# robot_PI4_F28379D.net
KiCad netlist of a schematic drawn in EAGLE
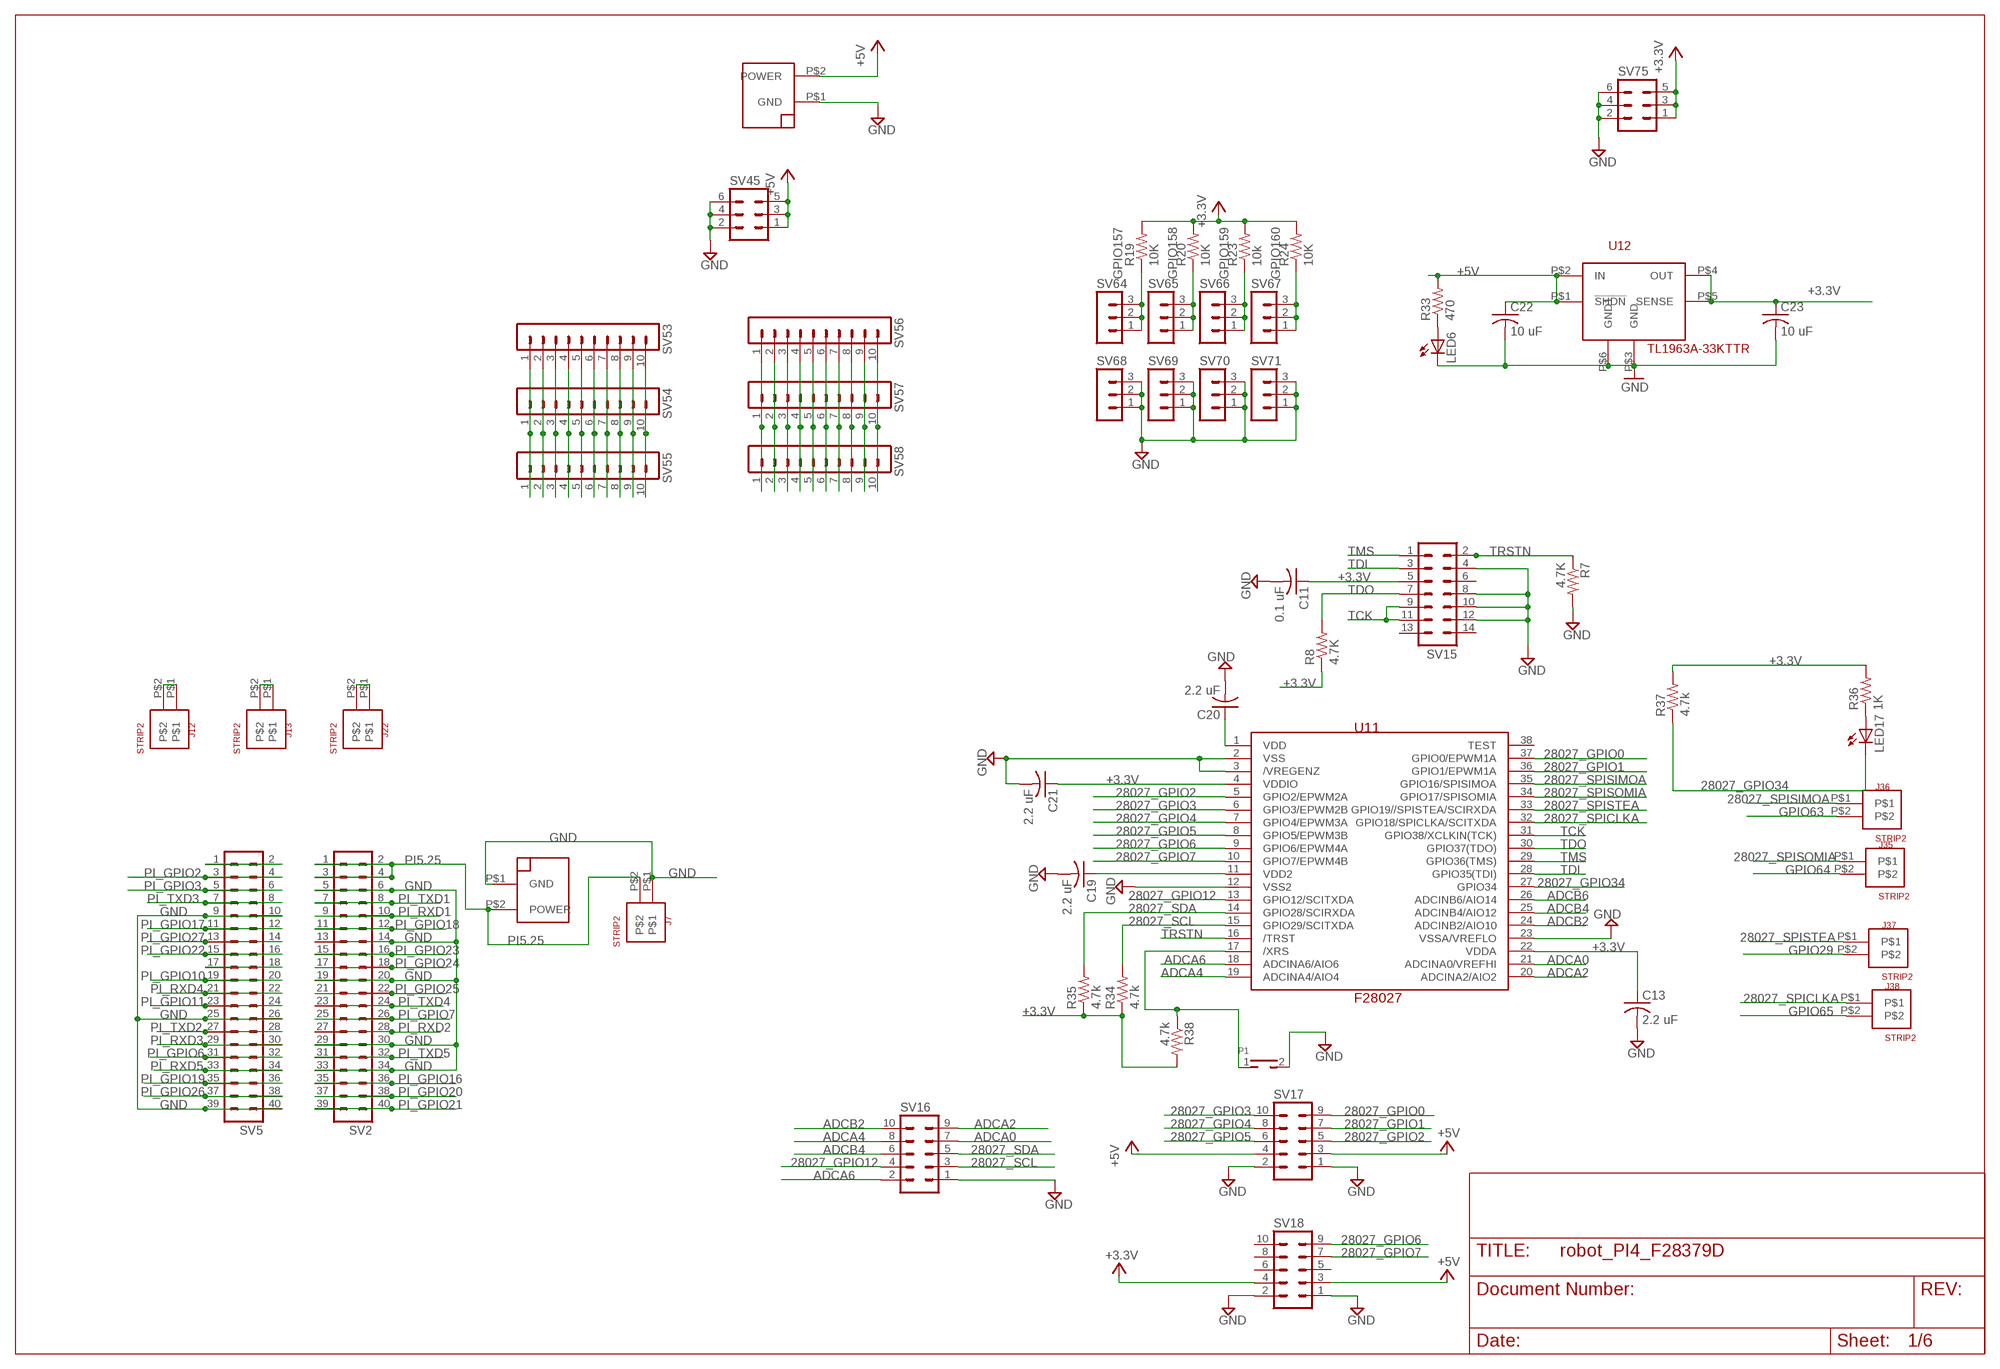
[diagram p0: schematic, sheet 1]
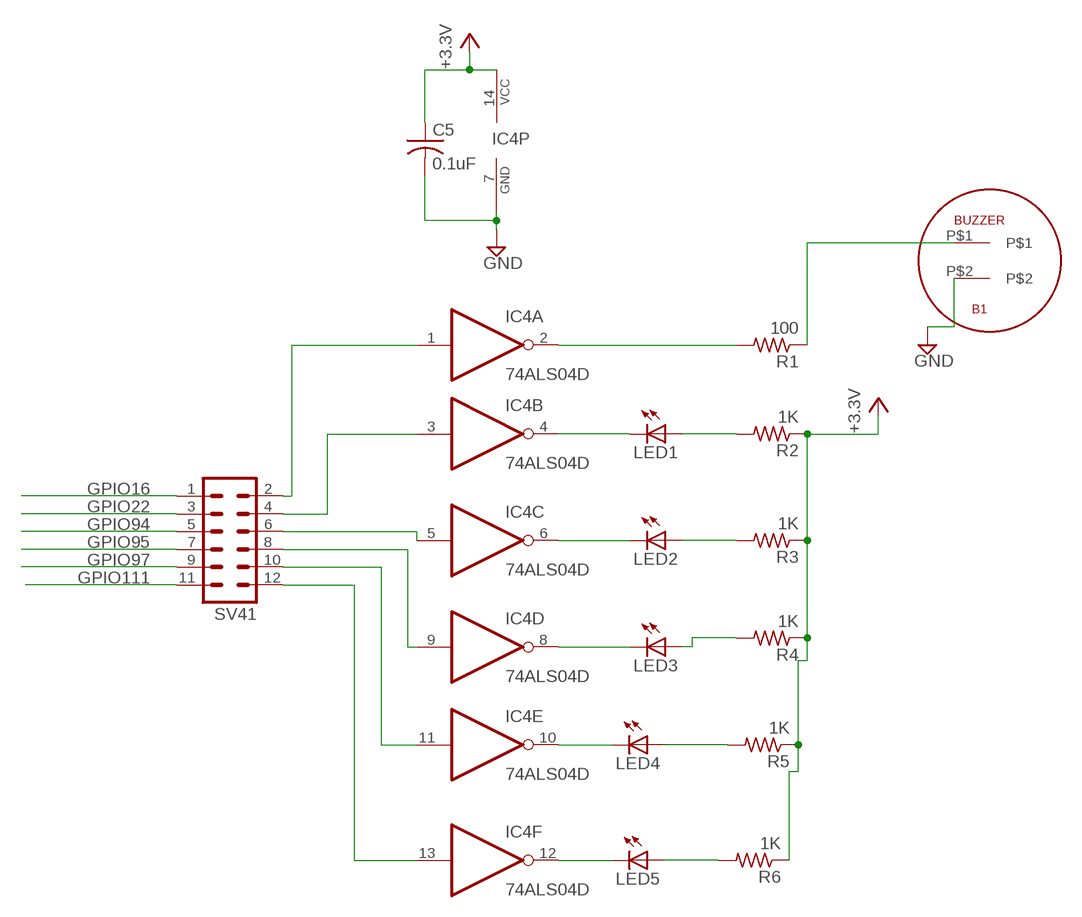
[diagram p1: schematic, sheet 2]
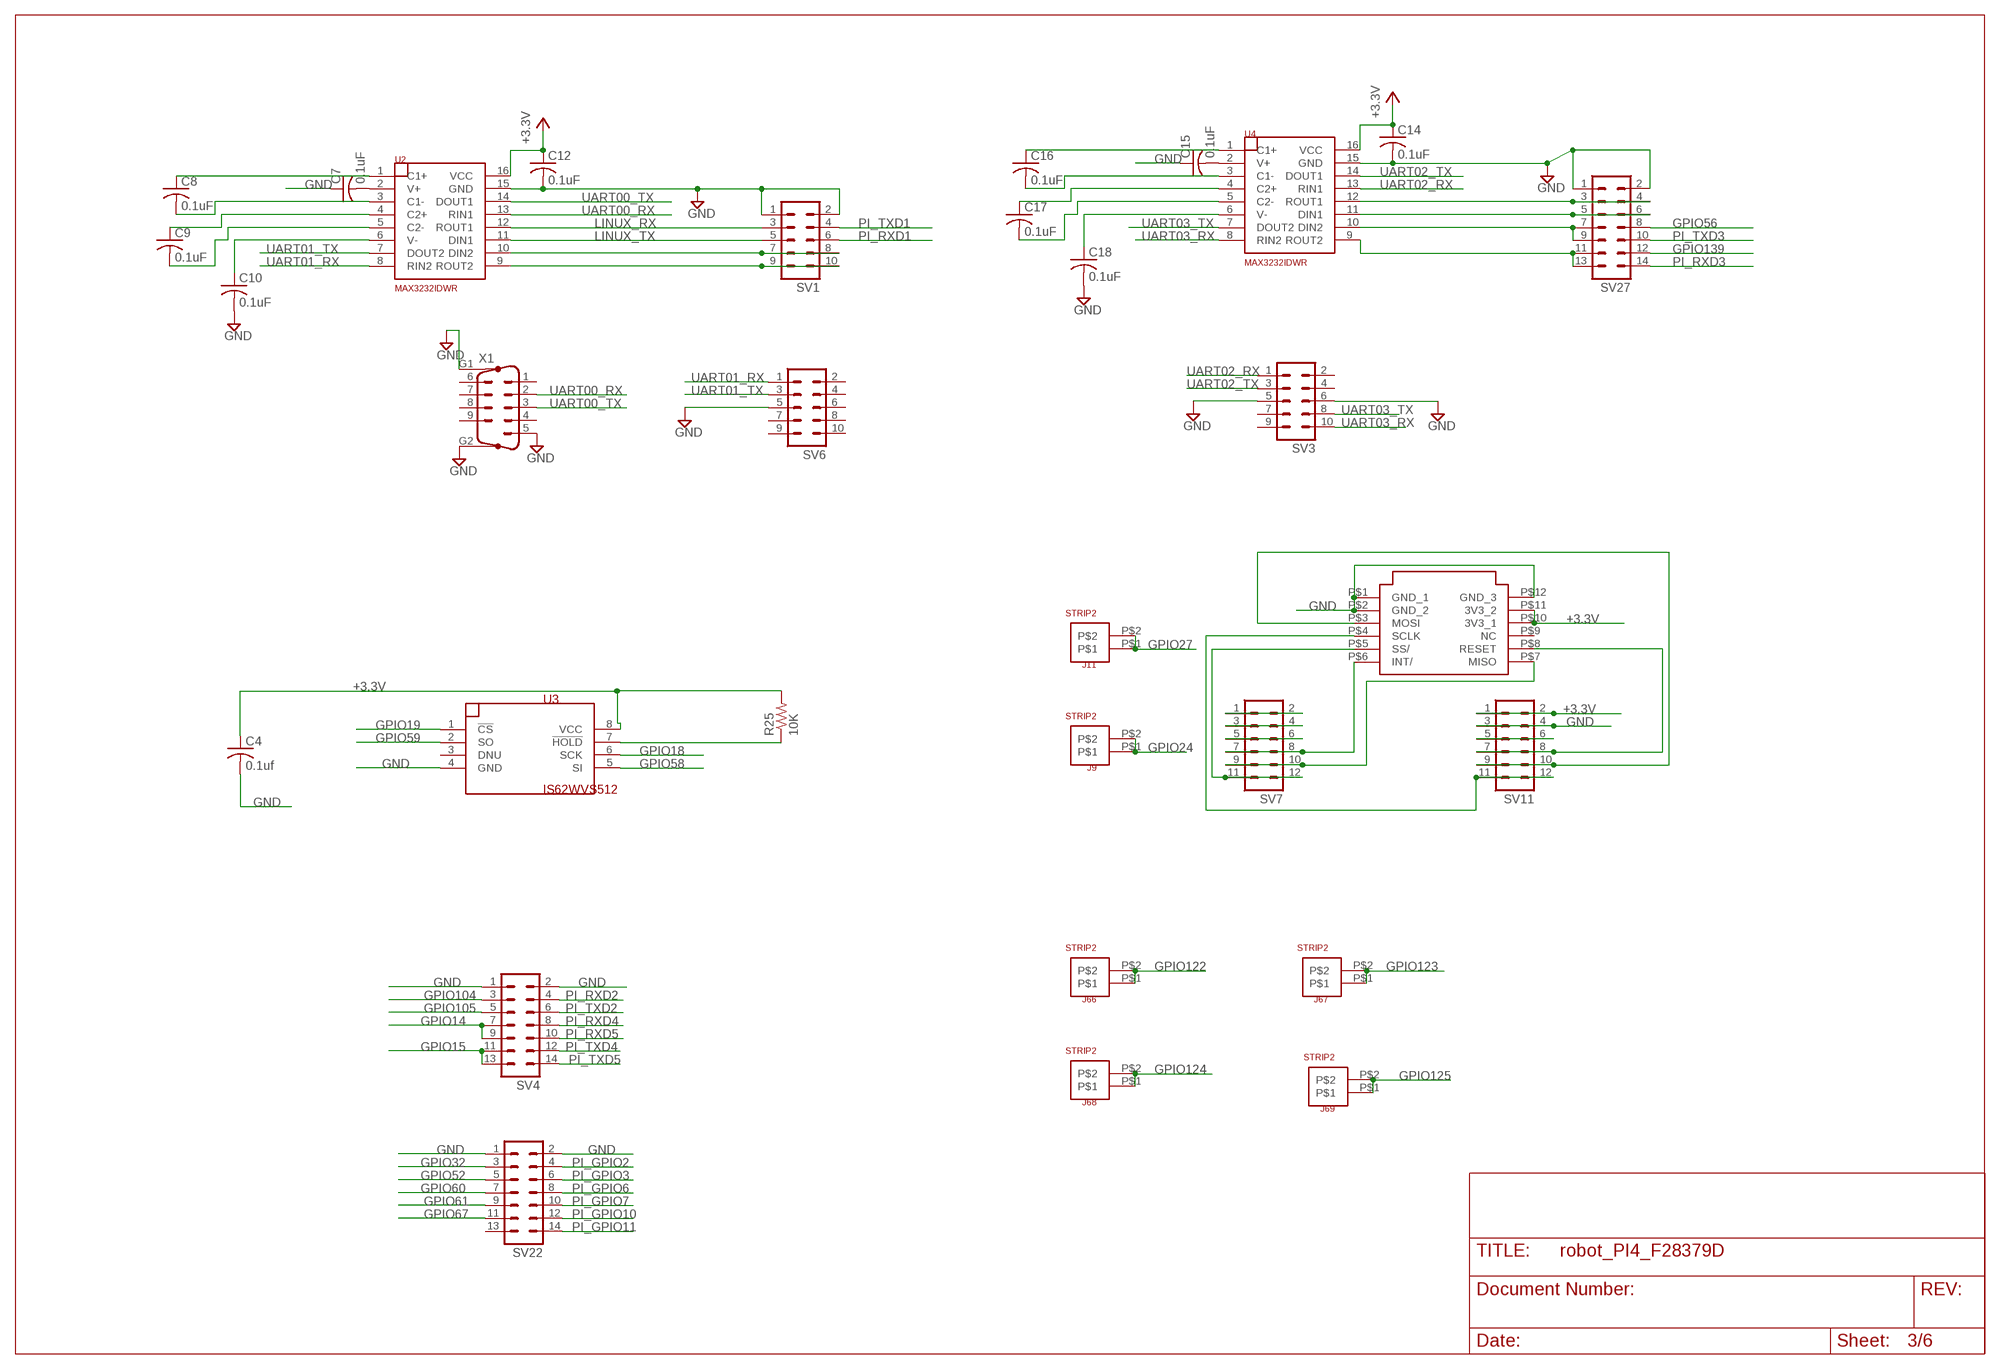
[diagram p2: schematic, sheet 3]
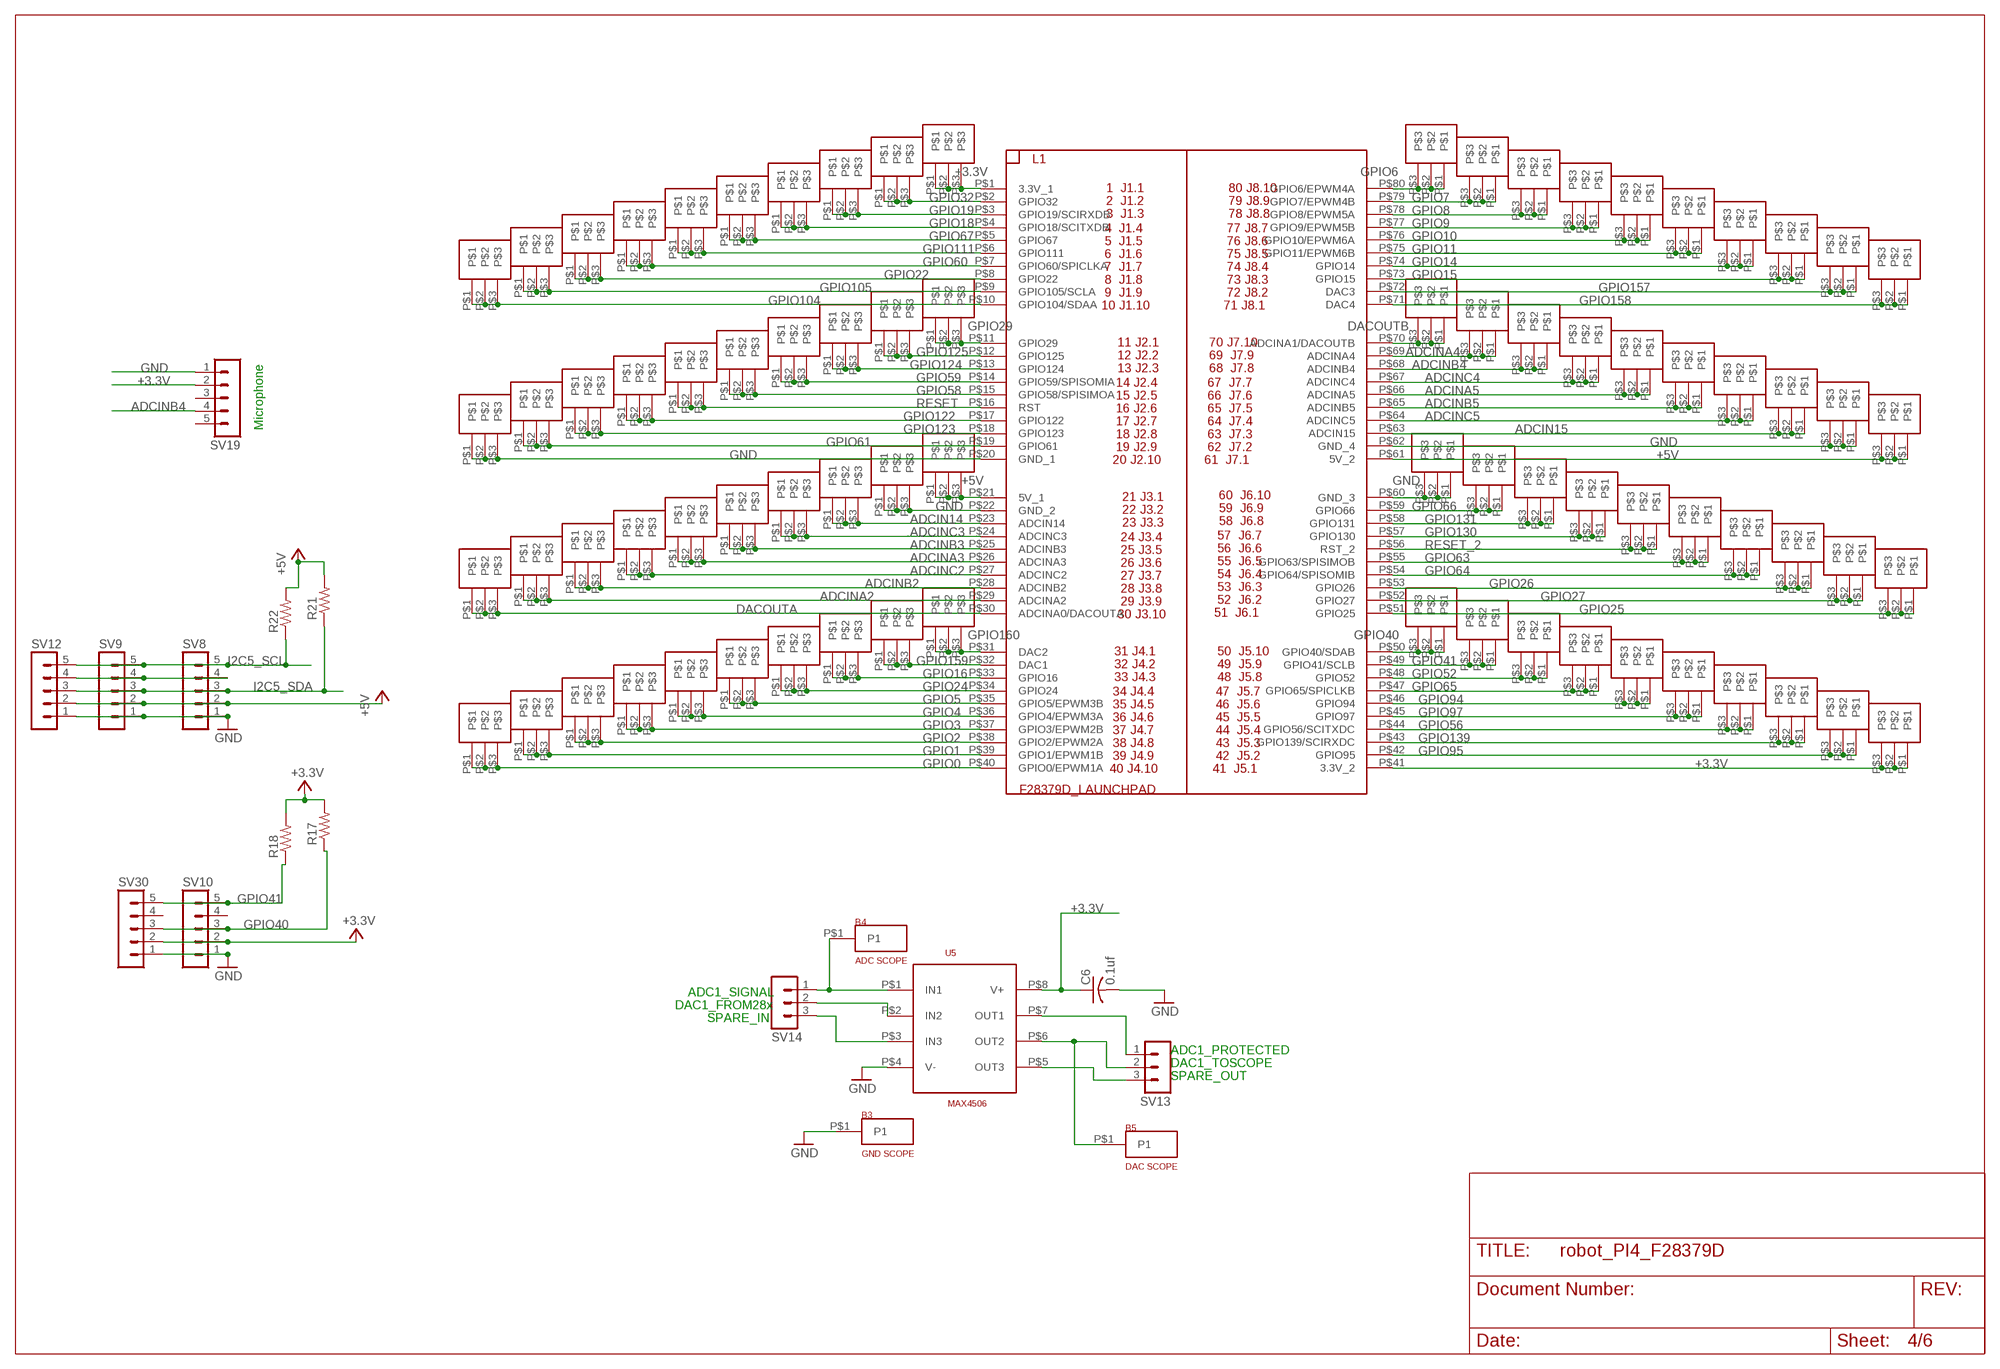
[diagram p3: schematic, sheet 4]
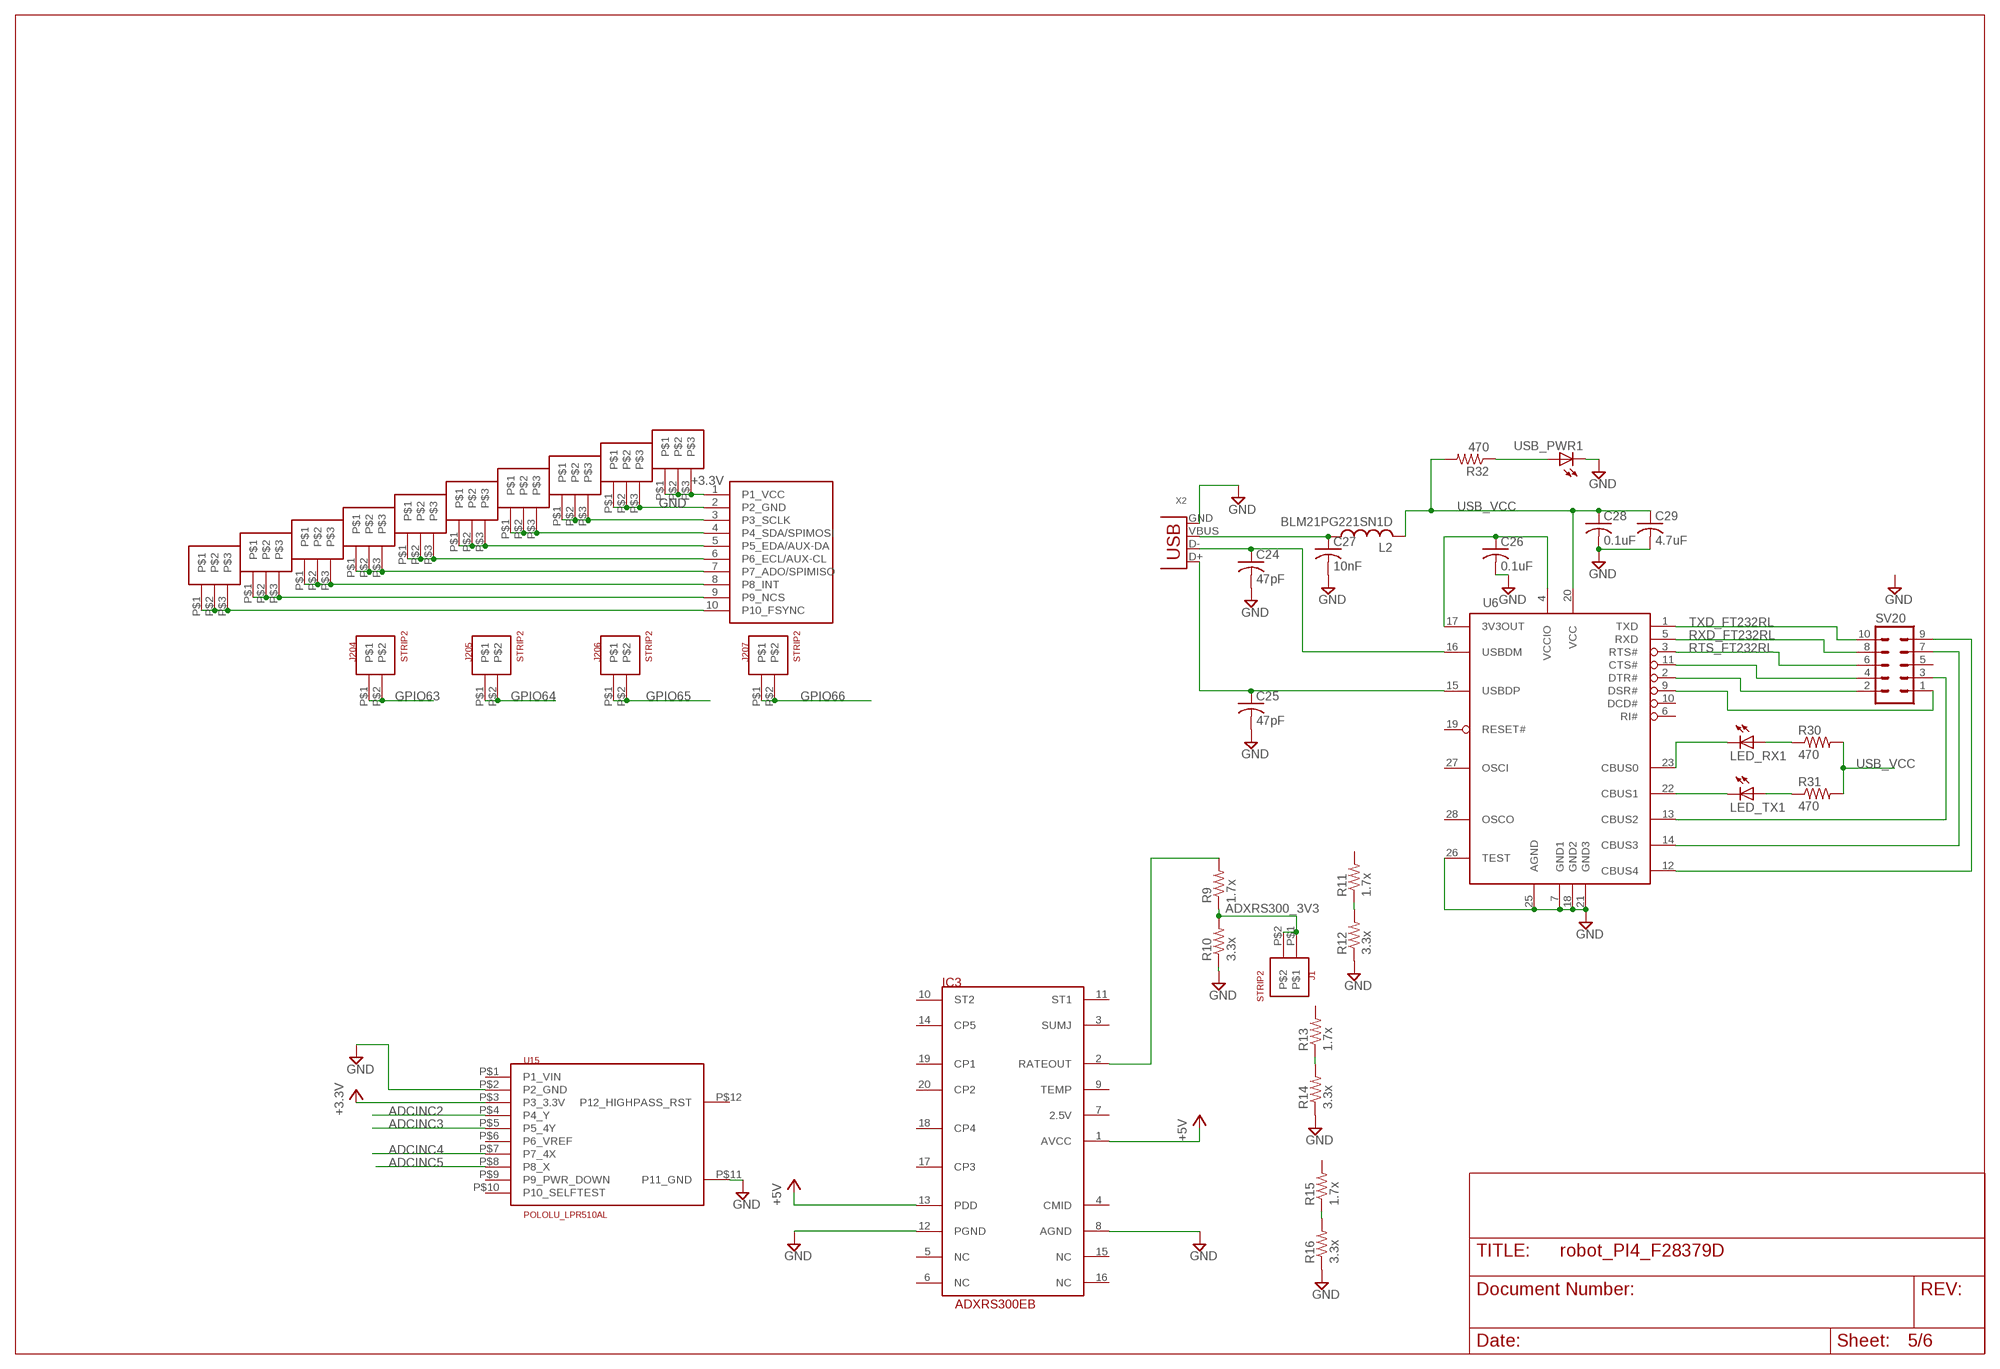
[diagram p4: schematic, sheet 5]
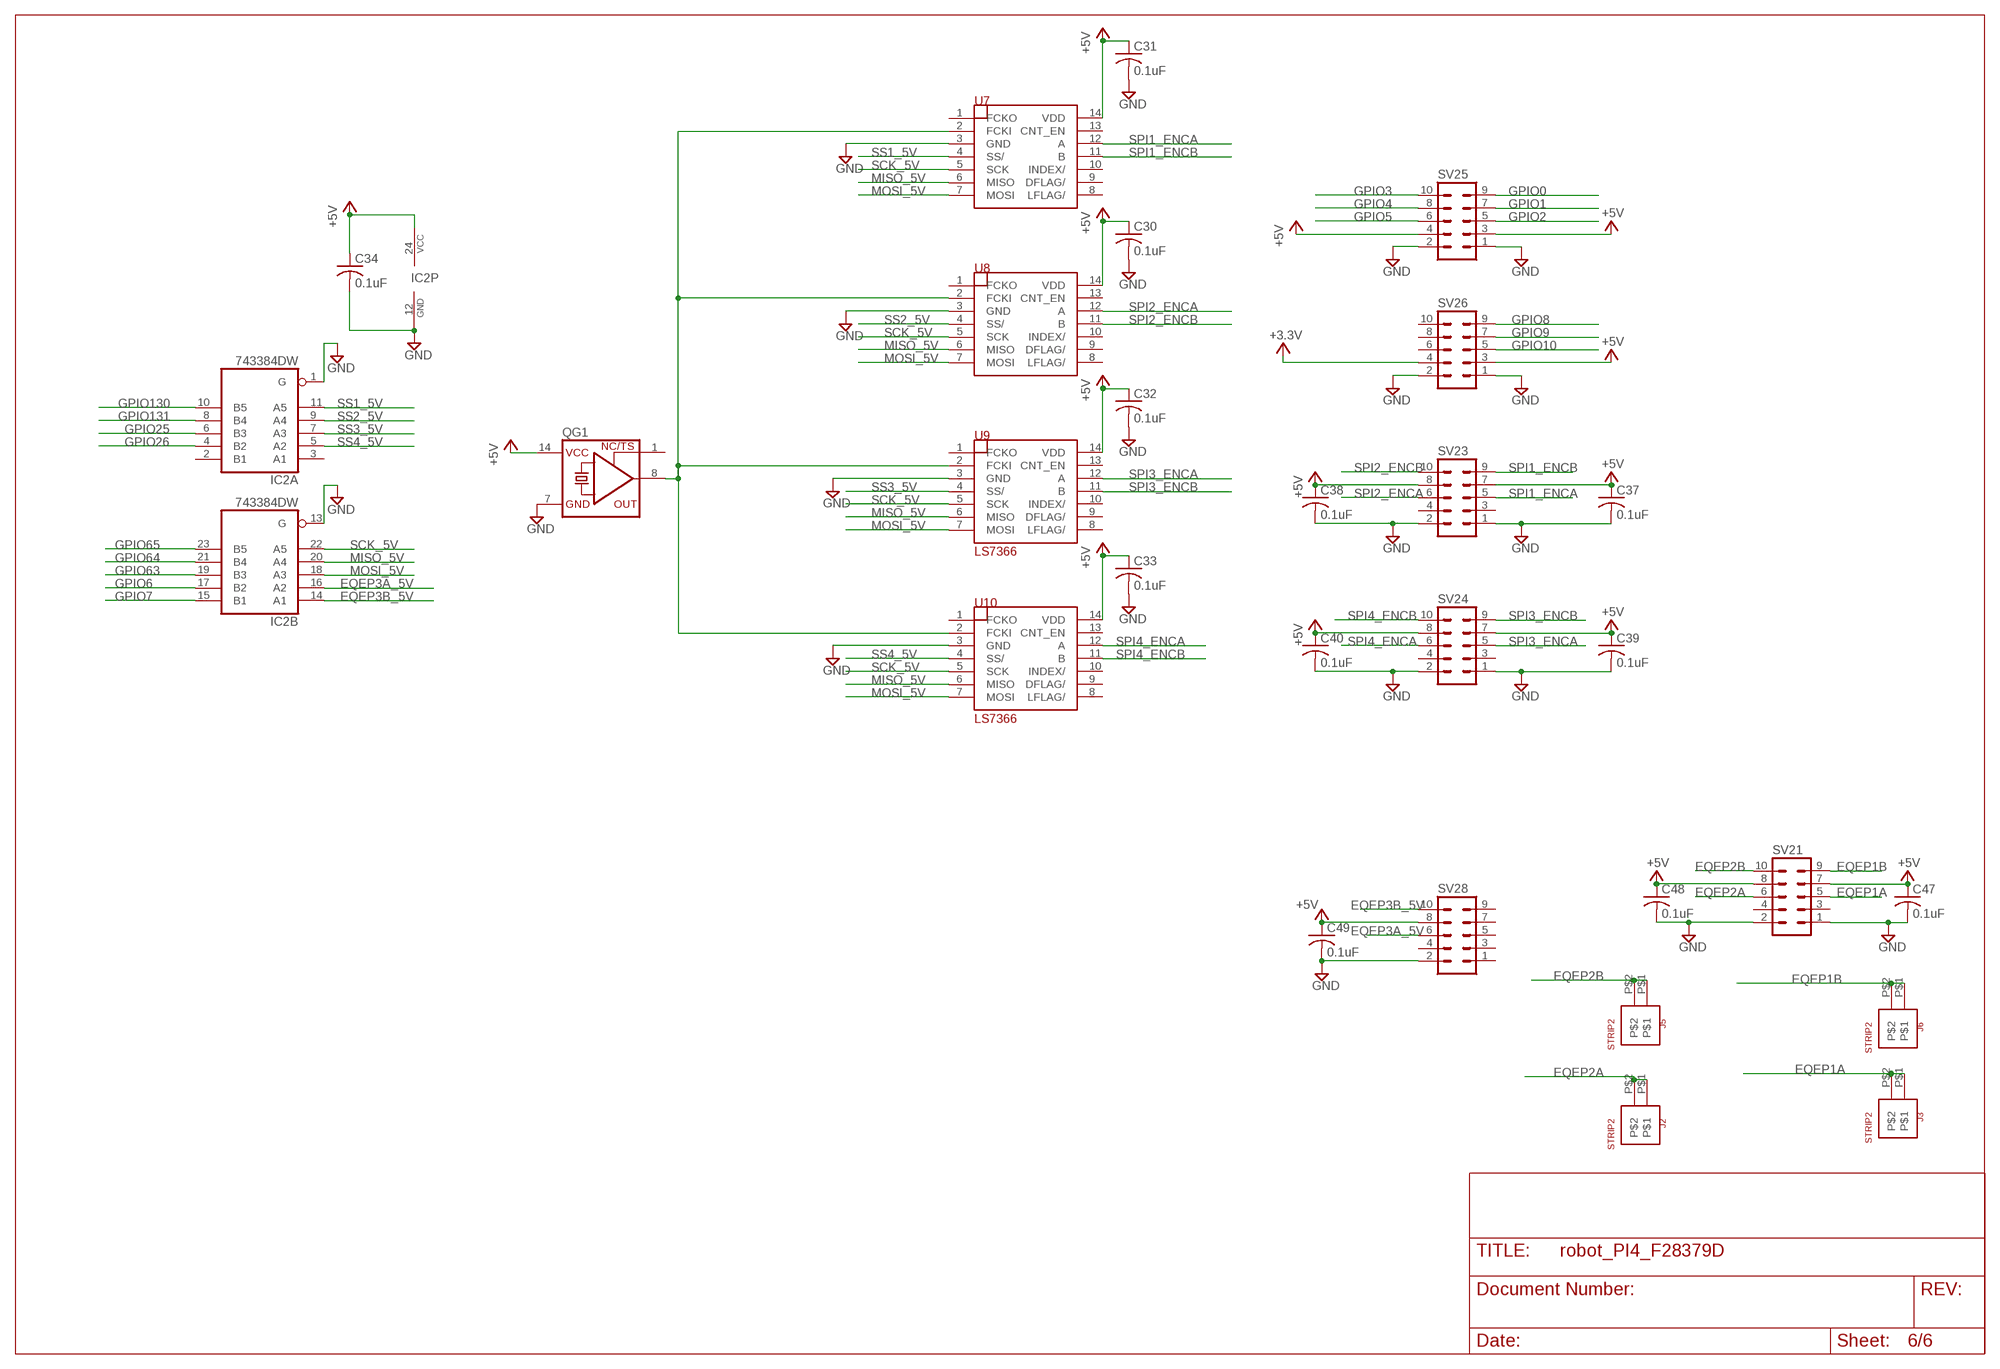
[diagram p5: schematic, sheet 6]

(export (version "E")
  (design (tool "Eeschema 10.0.6"))
  (components
    (comp (ref "C30")
      (value "0.1uF")
      (footprint "eagle-import:C1206")
      (libsource (lib "eagle-import") (part "C-USC1206"))
    )
    (comp (ref "C31")
      (value "0.1uF")
      (footprint "eagle-import:C1206")
      (libsource (lib "eagle-import") (part "C-USC1206"))
    )
    (comp (ref "C32")
      (value "0.1uF")
      (footprint "eagle-import:C1206")
      (libsource (lib "eagle-import") (part "C-USC1206"))
    )
    (comp (ref "C33")
      (value "0.1uF")
      (footprint "eagle-import:C1206")
      (libsource (lib "eagle-import") (part "C-USC1206"))
    )
    (comp (ref "C34")
      (value "0.1uF")
      (footprint "eagle-import:C1206")
      (libsource (lib "eagle-import") (part "C-USC1206"))
    )
    (comp (ref "C37")
      (value "0.1uF")
      (footprint "eagle-import:C1206")
      (libsource (lib "eagle-import") (part "C-USC1206"))
    )
    (comp (ref "C38")
      (value "0.1uF")
      (footprint "eagle-import:C1206")
      (libsource (lib "eagle-import") (part "C-USC1206"))
    )
    (comp (ref "C39")
      (value "0.1uF")
      (footprint "eagle-import:C1206")
      (libsource (lib "eagle-import") (part "C-USC1206"))
    )
    (comp (ref "C40")
      (value "0.1uF")
      (footprint "eagle-import:C1206")
      (libsource (lib "eagle-import") (part "C-USC1206"))
    )
    (comp (ref "C47")
      (value "0.1uF")
      (footprint "eagle-import:C1206")
      (libsource (lib "eagle-import") (part "C-USC1206"))
    )
    (comp (ref "C48")
      (value "0.1uF")
      (footprint "eagle-import:C1206")
      (libsource (lib "eagle-import") (part "C-USC1206"))
    )
    (comp (ref "C49")
      (value "0.1uF")
      (footprint "eagle-import:C1206")
      (libsource (lib "eagle-import") (part "C-USC1206"))
    )
    (comp (ref "IC2")
      (value "743384DW")
      (footprint "eagle-import:SO24W")
      (libsource (lib "eagle-import") (part "743384DW"))
    )
    (comp (ref "J2")
      (value "STRIP2")
      (footprint "eagle-import:STRIP2")
      (libsource (lib "eagle-import") (part "STRIP2"))
    )
    (comp (ref "J3")
      (value "STRIP2")
      (footprint "eagle-import:STRIP2")
      (libsource (lib "eagle-import") (part "STRIP2"))
    )
    (comp (ref "J5")
      (value "STRIP2")
      (footprint "eagle-import:STRIP2")
      (libsource (lib "eagle-import") (part "STRIP2"))
    )
    (comp (ref "J6")
      (value "STRIP2")
      (footprint "eagle-import:STRIP2")
      (libsource (lib "eagle-import") (part "STRIP2"))
    )
    (comp (ref "QG1")
      (value "XO-14")
      (footprint "eagle-import:DIL14S")
      (libsource (lib "eagle-import") (part "XO-14"))
    )
    (comp (ref "SV21")
      (value "MA05-2")
      (footprint "eagle-import:MA05-2")
      (libsource (lib "eagle-import") (part "MA05-2"))
    )
    (comp (ref "SV23")
      (value "MA05-2")
      (footprint "eagle-import:MA05-2")
      (libsource (lib "eagle-import") (part "MA05-2"))
    )
    (comp (ref "SV24")
      (value "MA05-2")
      (footprint "eagle-import:MA05-2")
      (libsource (lib "eagle-import") (part "MA05-2"))
    )
    (comp (ref "SV25")
      (value "MA05-2")
      (footprint "eagle-import:MA05-2")
      (libsource (lib "eagle-import") (part "MA05-2"))
    )
    (comp (ref "SV26")
      (value "MA05-2")
      (footprint "eagle-import:MA05-2")
      (libsource (lib "eagle-import") (part "MA05-2"))
    )
    (comp (ref "SV28")
      (value "MA05-2")
      (footprint "eagle-import:MA05-2")
      (libsource (lib "eagle-import") (part "MA05-2"))
    )
    (comp (ref "U7")
      (value "LS7366R")
      (footprint "eagle-import:SO14")
      (libsource (lib "eagle-import") (part "LS7366R"))
    )
    (comp (ref "U8")
      (value "LS7366R")
      (footprint "eagle-import:SO14")
      (libsource (lib "eagle-import") (part "LS7366R"))
    )
    (comp (ref "U9")
      (value "LS7366")
      (footprint "eagle-import:SO14")
      (libsource (lib "eagle-import") (part "LS7366R"))
    )
    (comp (ref "U10")
      (value "LS7366")
      (footprint "eagle-import:SO14")
      (libsource (lib "eagle-import") (part "LS7366R"))
    )
    (comp (ref "C24")
      (value "47pF")
      (footprint "eagle-import:C1206")
      (libsource (lib "eagle-import") (part "C-USC1206"))
    )
    (comp (ref "C25")
      (value "47pF")
      (footprint "eagle-import:C1206")
      (libsource (lib "eagle-import") (part "C-USC1206"))
    )
    (comp (ref "C26")
      (value "0.1uF")
      (footprint "eagle-import:C1206")
      (libsource (lib "eagle-import") (part "C-USC1206"))
    )
    (comp (ref "C27")
      (value "10nF")
      (footprint "eagle-import:C1206")
      (libsource (lib "eagle-import") (part "C-USC1206"))
    )
    (comp (ref "C28")
      (value "0.1uF")
      (footprint "eagle-import:C1206")
      (libsource (lib "eagle-import") (part "C-USC1206"))
    )
    (comp (ref "C29")
      (value "4.7uF")
      (footprint "eagle-import:C1206")
      (libsource (lib "eagle-import") (part "C-USC1206"))
    )
    (comp (ref "IC3")
      (value "ADXRS300EB")
      (footprint "eagle-import:DIL20")
      (libsource (lib "eagle-import") (part "ADXRS300EB"))
    )
    (comp (ref "J1")
      (value "STRIP2")
      (footprint "eagle-import:STRIP2")
      (libsource (lib "eagle-import") (part "STRIP2"))
    )
    (comp (ref "J123")
      (value "STRIP3")
      (footprint "eagle-import:STRIP3")
      (libsource (lib "eagle-import") (part "STRIP3"))
    )
    (comp (ref "J124")
      (value "STRIP3")
      (footprint "eagle-import:STRIP3")
      (libsource (lib "eagle-import") (part "STRIP3"))
    )
    (comp (ref "J125")
      (value "STRIP3")
      (footprint "eagle-import:STRIP3")
      (libsource (lib "eagle-import") (part "STRIP3"))
    )
    (comp (ref "J126")
      (value "STRIP3")
      (footprint "eagle-import:STRIP3")
      (libsource (lib "eagle-import") (part "STRIP3"))
    )
    (comp (ref "J127")
      (value "STRIP3")
      (footprint "eagle-import:STRIP3")
      (libsource (lib "eagle-import") (part "STRIP3"))
    )
    (comp (ref "J128")
      (value "STRIP3")
      (footprint "eagle-import:STRIP3")
      (libsource (lib "eagle-import") (part "STRIP3"))
    )
    (comp (ref "J129")
      (value "STRIP3")
      (footprint "eagle-import:STRIP3")
      (libsource (lib "eagle-import") (part "STRIP3"))
    )
    (comp (ref "J130")
      (value "STRIP3")
      (footprint "eagle-import:STRIP3")
      (libsource (lib "eagle-import") (part "STRIP3"))
    )
    (comp (ref "J131")
      (value "STRIP3")
      (footprint "eagle-import:STRIP3")
      (libsource (lib "eagle-import") (part "STRIP3"))
    )
    (comp (ref "J132")
      (value "STRIP3")
      (footprint "eagle-import:STRIP3")
      (libsource (lib "eagle-import") (part "STRIP3"))
    )
    (comp (ref "J204")
      (value "STRIP2")
      (footprint "eagle-import:STRIP2")
      (libsource (lib "eagle-import") (part "STRIP2"))
    )
    (comp (ref "J205")
      (value "STRIP2")
      (footprint "eagle-import:STRIP2")
      (libsource (lib "eagle-import") (part "STRIP2"))
    )
    (comp (ref "J206")
      (value "STRIP2")
      (footprint "eagle-import:STRIP2")
      (libsource (lib "eagle-import") (part "STRIP2"))
    )
    (comp (ref "J207")
      (value "STRIP2")
      (footprint "eagle-import:STRIP2")
      (libsource (lib "eagle-import") (part "STRIP2"))
    )
    (comp (ref "L2")
      (value "BLM21PG221SN1D")
      (footprint "eagle-import:L0805")
      (libsource (lib "eagle-import") (part "L-USL0805"))
    )
    (comp (ref "LED_RX1")
      (value "LED3MM")
      (footprint "eagle-import:LED3MM")
      (libsource (lib "eagle-import") (part "LED3MM"))
    )
    (comp (ref "LED_TX1")
      (value "LED3MM")
      (footprint "eagle-import:LED3MM")
      (libsource (lib "eagle-import") (part "LED3MM"))
    )
    (comp (ref "R9")
      (value "1.7x")
      (footprint "eagle-import:M1206")
      (libsource (lib "eagle-import") (part "R-US_M1206"))
    )
    (comp (ref "R10")
      (value "3.3x")
      (footprint "eagle-import:M1206")
      (libsource (lib "eagle-import") (part "R-US_M1206"))
    )
    (comp (ref "R11")
      (value "1.7x")
      (footprint "eagle-import:M1206")
      (libsource (lib "eagle-import") (part "R-US_M1206"))
    )
    (comp (ref "R12")
      (value "3.3x")
      (footprint "eagle-import:M1206")
      (libsource (lib "eagle-import") (part "R-US_M1206"))
    )
    (comp (ref "R13")
      (value "1.7x")
      (footprint "eagle-import:M1206")
      (libsource (lib "eagle-import") (part "R-US_M1206"))
    )
    (comp (ref "R14")
      (value "3.3x")
      (footprint "eagle-import:M1206")
      (libsource (lib "eagle-import") (part "R-US_M1206"))
    )
    (comp (ref "R15")
      (value "1.7x")
      (footprint "eagle-import:M1206")
      (libsource (lib "eagle-import") (part "R-US_M1206"))
    )
    (comp (ref "R16")
      (value "3.3x")
      (footprint "eagle-import:M1206")
      (libsource (lib "eagle-import") (part "R-US_M1206"))
    )
    (comp (ref "R30")
      (value "470")
      (footprint "eagle-import:M1206")
      (libsource (lib "eagle-import") (part "R-US_M1206"))
    )
    (comp (ref "R31")
      (value "470")
      (footprint "eagle-import:M1206")
      (libsource (lib "eagle-import") (part "R-US_M1206"))
    )
    (comp (ref "R32")
      (value "470")
      (footprint "eagle-import:M1206")
      (libsource (lib "eagle-import") (part "R-US_M1206"))
    )
    (comp (ref "SV20")
      (value "MA05-2")
      (footprint "eagle-import:MA05-2")
      (libsource (lib "eagle-import") (part "MA05-2"))
    )
    (comp (ref "U$1")
      (value "MPU-9250-BB")
      (footprint "eagle-import:MPU-9250-BB")
      (libsource (lib "eagle-import") (part "MPU-9250-BB"))
    )
    (comp (ref "U6")
      (value "FT232RL")
      (footprint "eagle-import:SSOP28DB")
      (libsource (lib "eagle-import") (part "FT232RL"))
    )
    (comp (ref "U15")
      (value "POLOLU_LPR510AL")
      (footprint "eagle-import:POLOLU_LPR510AL")
      (libsource (lib "eagle-import") (part "POLOLU_LPR510AL"))
    )
    (comp (ref "USB_PWR1")
      (value "LED3MM")
      (footprint "eagle-import:LED3MM")
      (libsource (lib "eagle-import") (part "LED3MM"))
    )
    (comp (ref "X2")
      (value "USB-B-H")
      (footprint "eagle-import:USB-B-H")
      (libsource (lib "eagle-import") (part "USB-B-H"))
    )
    (comp (ref "B1")
      (value "BUZZER")
      (footprint "eagle-import:BUZZER")
      (libsource (lib "eagle-import") (part "BUZZER"))
    )
    (comp (ref "C5")
      (value "0.1uF")
      (footprint "eagle-import:C0805")
      (libsource (lib "eagle-import") (part "C-USC0805"))
    )
    (comp (ref "IC4")
      (value "74ALS04D")
      (footprint "eagle-import:SO14")
      (libsource (lib "eagle-import") (part "7404DALS"))
    )
    (comp (ref "LED1")
      (value "LEDCHIPLED_1206")
      (footprint "eagle-import:CHIPLED_1206")
      (libsource (lib "eagle-import") (part "LEDCHIPLED_1206"))
    )
    (comp (ref "LED2")
      (value "LEDCHIPLED_1206")
      (footprint "eagle-import:CHIPLED_1206")
      (libsource (lib "eagle-import") (part "LEDCHIPLED_1206"))
    )
    (comp (ref "LED3")
      (value "LEDCHIPLED_1206")
      (footprint "eagle-import:CHIPLED_1206")
      (libsource (lib "eagle-import") (part "LEDCHIPLED_1206"))
    )
    (comp (ref "LED4")
      (value "LEDCHIPLED_1206")
      (footprint "eagle-import:CHIPLED_1206")
      (libsource (lib "eagle-import") (part "LEDCHIPLED_1206"))
    )
    (comp (ref "LED5")
      (value "LEDCHIPLED_1206")
      (footprint "eagle-import:CHIPLED_1206")
      (libsource (lib "eagle-import") (part "LEDCHIPLED_1206"))
    )
    (comp (ref "R1")
      (value "100")
      (footprint "eagle-import:R1206")
      (libsource (lib "eagle-import") (part "R-US_R1206"))
    )
    (comp (ref "R2")
      (value "1K")
      (footprint "eagle-import:R1206")
      (libsource (lib "eagle-import") (part "R-US_R1206"))
    )
    (comp (ref "R3")
      (value "1K")
      (footprint "eagle-import:R1206")
      (libsource (lib "eagle-import") (part "R-US_R1206"))
    )
    (comp (ref "R4")
      (value "1K")
      (footprint "eagle-import:R1206")
      (libsource (lib "eagle-import") (part "R-US_R1206"))
    )
    (comp (ref "R5")
      (value "1K")
      (footprint "eagle-import:R1206")
      (libsource (lib "eagle-import") (part "R-US_R1206"))
    )
    (comp (ref "R6")
      (value "1K")
      (footprint "eagle-import:R1206")
      (libsource (lib "eagle-import") (part "R-US_R1206"))
    )
    (comp (ref "SV41")
      (value "MA06-2")
      (footprint "eagle-import:MA06-2")
      (libsource (lib "eagle-import") (part "MA06-2"))
    )
    (comp (ref "C11")
      (value "0.1 uF")
      (footprint "eagle-import:C1206")
      (libsource (lib "eagle-import") (part "C-USC1206"))
    )
    (comp (ref "C13")
      (value "2.2 uF")
      (footprint "eagle-import:C1206")
      (libsource (lib "eagle-import") (part "C-USC1206"))
    )
    (comp (ref "C19")
      (value "2.2 uF")
      (footprint "eagle-import:C1206")
      (libsource (lib "eagle-import") (part "C-USC1206"))
    )
    (comp (ref "C20")
      (value "2.2 uF")
      (footprint "eagle-import:C1206")
      (libsource (lib "eagle-import") (part "C-USC1206"))
    )
    (comp (ref "C21")
      (value "2.2 uF")
      (footprint "eagle-import:C1206")
      (libsource (lib "eagle-import") (part "C-USC1206"))
    )
    (comp (ref "C22")
      (value "10 uF")
      (footprint "eagle-import:C1206")
      (libsource (lib "eagle-import") (part "C-USC1206"))
    )
    (comp (ref "C23")
      (value "10 uF")
      (footprint "eagle-import:C1206")
      (libsource (lib "eagle-import") (part "C-USC1206"))
    )
    (comp (ref "J7")
      (value "STRIP2")
      (footprint "eagle-import:STRIP2")
      (libsource (lib "eagle-import") (part "STRIP2"))
    )
    (comp (ref "J12")
      (value "STRIP2")
      (footprint "eagle-import:STRIP2")
      (libsource (lib "eagle-import") (part "STRIP2"))
    )
    (comp (ref "J13")
      (value "STRIP2")
      (footprint "eagle-import:STRIP2")
      (libsource (lib "eagle-import") (part "STRIP2"))
    )
    (comp (ref "J22")
      (value "STRIP2")
      (footprint "eagle-import:STRIP2")
      (libsource (lib "eagle-import") (part "STRIP2"))
    )
    (comp (ref "J35")
      (value "STRIP2")
      (footprint "eagle-import:STRIP2")
      (libsource (lib "eagle-import") (part "STRIP2"))
    )
    (comp (ref "J36")
      (value "STRIP2")
      (footprint "eagle-import:STRIP2")
      (libsource (lib "eagle-import") (part "STRIP2"))
    )
    (comp (ref "J37")
      (value "STRIP2")
      (footprint "eagle-import:STRIP2")
      (libsource (lib "eagle-import") (part "STRIP2"))
    )
    (comp (ref "J38")
      (value "STRIP2")
      (footprint "eagle-import:STRIP2")
      (libsource (lib "eagle-import") (part "STRIP2"))
    )
    (comp (ref "LED6")
      (value "LEDCHIPLED_1206")
      (footprint "eagle-import:CHIPLED_1206")
      (libsource (lib "eagle-import") (part "LEDCHIPLED_1206"))
    )
    (comp (ref "LED17")
      (value "LEDCHIPLED_1206")
      (footprint "eagle-import:CHIPLED_1206")
      (libsource (lib "eagle-import") (part "LEDCHIPLED_1206"))
    )
    (comp (ref "P1")
      (value "TH_PUSHBOTTON")
      (footprint "eagle-import:TH_PUSHBUTTON")
      (libsource (lib "eagle-import") (part "TH_PUSHBOTTON"))
    )
    (comp (ref "P2")
      (value "MOLEX_POWER")
      (footprint "eagle-import:MOLEX_POWER")
      (libsource (lib "eagle-import") (part "MOLEX_POWER"))
    )
    (comp (ref "P3")
      (value "MOLEX_POWER")
      (footprint "eagle-import:MOLEX_POWER")
      (libsource (lib "eagle-import") (part "MOLEX_POWER"))
    )
    (comp (ref "R7")
      (value "4.7K")
      (footprint "eagle-import:M1206")
      (libsource (lib "eagle-import") (part "R-US_M1206"))
    )
    (comp (ref "R8")
      (value "4.7K")
      (footprint "eagle-import:M1206")
      (libsource (lib "eagle-import") (part "R-US_M1206"))
    )
    (comp (ref "R19")
      (value "10K")
      (footprint "eagle-import:M1206")
      (libsource (lib "eagle-import") (part "R-US_M1206"))
    )
    (comp (ref "R20")
      (value "10K")
      (footprint "eagle-import:M1206")
      (libsource (lib "eagle-import") (part "R-US_M1206"))
    )
    (comp (ref "R23")
      (value "10k")
      (footprint "eagle-import:M1206")
      (libsource (lib "eagle-import") (part "R-US_M1206"))
    )
    (comp (ref "R24")
      (value "10K")
      (footprint "eagle-import:M1206")
      (libsource (lib "eagle-import") (part "R-US_M1206"))
    )
    (comp (ref "R33")
      (value "470")
      (footprint "eagle-import:M1206")
      (libsource (lib "eagle-import") (part "R-US_M1206"))
    )
    (comp (ref "R34")
      (value "4.7k")
      (footprint "eagle-import:M1206")
      (libsource (lib "eagle-import") (part "R-US_M1206"))
    )
    (comp (ref "R35")
      (value "4.7k")
      (footprint "eagle-import:M1206")
      (libsource (lib "eagle-import") (part "R-US_M1206"))
    )
    (comp (ref "R36")
      (value "1K")
      (footprint "eagle-import:M1206")
      (libsource (lib "eagle-import") (part "R-US_M1206"))
    )
    (comp (ref "R37")
      (value "4.7k")
      (footprint "eagle-import:M1206")
      (libsource (lib "eagle-import") (part "R-US_M1206"))
    )
    (comp (ref "R38")
      (value "4.7k")
      (footprint "eagle-import:M1206")
      (libsource (lib "eagle-import") (part "R-US_M1206"))
    )
    (comp (ref "SV2")
      (value "MA20-2")
      (footprint "eagle-import:MA20-2")
      (libsource (lib "eagle-import") (part "MA20-2"))
    )
    (comp (ref "SV5")
      (value "MA20-2")
      (footprint "eagle-import:MA20-2")
      (libsource (lib "eagle-import") (part "MA20-2"))
    )
    (comp (ref "SV15")
      (value "MA07-2")
      (footprint "eagle-import:MA07-2")
      (libsource (lib "eagle-import") (part "MA07-2"))
    )
    (comp (ref "SV16")
      (value "MA05-2")
      (footprint "eagle-import:MA05-2")
      (libsource (lib "eagle-import") (part "MA05-2"))
    )
    (comp (ref "SV17")
      (value "MA05-2")
      (footprint "eagle-import:MA05-2")
      (libsource (lib "eagle-import") (part "MA05-2"))
    )
    (comp (ref "SV18")
      (value "MA05-2")
      (footprint "eagle-import:MA05-2")
      (libsource (lib "eagle-import") (part "MA05-2"))
    )
    (comp (ref "SV45")
      (value "MA03-2")
      (footprint "eagle-import:MA03-2")
      (libsource (lib "eagle-import") (part "MA03-2"))
    )
    (comp (ref "SV53")
      (value "MA10-1")
      (footprint "eagle-import:MA10-1")
      (libsource (lib "eagle-import") (part "MA10-1"))
    )
    (comp (ref "SV54")
      (value "MA10-1")
      (footprint "eagle-import:MA10-1")
      (libsource (lib "eagle-import") (part "MA10-1"))
    )
    (comp (ref "SV55")
      (value "MA10-1")
      (footprint "eagle-import:MA10-1")
      (libsource (lib "eagle-import") (part "MA10-1"))
    )
    (comp (ref "SV56")
      (value "MA10-1")
      (footprint "eagle-import:MA10-1")
      (libsource (lib "eagle-import") (part "MA10-1"))
    )
    (comp (ref "SV57")
      (value "MA10-1")
      (footprint "eagle-import:MA10-1")
      (libsource (lib "eagle-import") (part "MA10-1"))
    )
    (comp (ref "SV58")
      (value "MA10-1")
      (footprint "eagle-import:MA10-1")
      (libsource (lib "eagle-import") (part "MA10-1"))
    )
    (comp (ref "SV64")
      (value "MA03-1")
      (footprint "eagle-import:MA03-1")
      (libsource (lib "eagle-import") (part "MA03-1"))
    )
    (comp (ref "SV65")
      (value "MA03-1")
      (footprint "eagle-import:MA03-1")
      (libsource (lib "eagle-import") (part "MA03-1"))
    )
    (comp (ref "SV66")
      (value "MA03-1")
      (footprint "eagle-import:MA03-1")
      (libsource (lib "eagle-import") (part "MA03-1"))
    )
    (comp (ref "SV67")
      (value "MA03-1")
      (footprint "eagle-import:MA03-1")
      (libsource (lib "eagle-import") (part "MA03-1"))
    )
    (comp (ref "SV68")
      (value "MA03-1")
      (footprint "eagle-import:MA03-1")
      (libsource (lib "eagle-import") (part "MA03-1"))
    )
    (comp (ref "SV69")
      (value "MA03-1")
      (footprint "eagle-import:MA03-1")
      (libsource (lib "eagle-import") (part "MA03-1"))
    )
    (comp (ref "SV70")
      (value "MA03-1")
      (footprint "eagle-import:MA03-1")
      (libsource (lib "eagle-import") (part "MA03-1"))
    )
    (comp (ref "SV71")
      (value "MA03-1")
      (footprint "eagle-import:MA03-1")
      (libsource (lib "eagle-import") (part "MA03-1"))
    )
    (comp (ref "SV75")
      (value "MA03-2")
      (footprint "eagle-import:MA03-2")
      (libsource (lib "eagle-import") (part "MA03-2"))
    )
    (comp (ref "U11")
      (value "F28027")
      (footprint "eagle-import:DA38")
      (libsource (lib "eagle-import") (part "TMS320F28027DAS"))
    )
    (comp (ref "U12")
      (value "TL1963A-33KTTR")
      (footprint "eagle-import:TL1963AKTTR")
      (libsource (lib "eagle-import") (part "TL1963A-33KTTR"))
    )
    (comp (ref "C4")
      (value "0.1uf")
      (footprint "eagle-import:C1206")
      (libsource (lib "eagle-import") (part "C-USC1206"))
    )
    (comp (ref "C7")
      (value "0.1uF")
      (footprint "eagle-import:C0805K")
      (libsource (lib "eagle-import") (part "C-USC0805K"))
    )
    (comp (ref "C8")
      (value "0.1uF")
      (footprint "eagle-import:C0805K")
      (libsource (lib "eagle-import") (part "C-USC0805K"))
    )
    (comp (ref "C9")
      (value "0.1uF")
      (footprint "eagle-import:C0805K")
      (libsource (lib "eagle-import") (part "C-USC0805K"))
    )
    (comp (ref "C10")
      (value "0.1uF")
      (footprint "eagle-import:C0805K")
      (libsource (lib "eagle-import") (part "C-USC0805K"))
    )
    (comp (ref "C12")
      (value "0.1uF")
      (footprint "eagle-import:C0805K")
      (libsource (lib "eagle-import") (part "C-USC0805K"))
    )
    (comp (ref "C14")
      (value "0.1uF")
      (footprint "eagle-import:C0805K")
      (libsource (lib "eagle-import") (part "C-USC0805K"))
    )
    (comp (ref "C15")
      (value "0.1uF")
      (footprint "eagle-import:C0805K")
      (libsource (lib "eagle-import") (part "C-USC0805K"))
    )
    (comp (ref "C16")
      (value "0.1uF")
      (footprint "eagle-import:C0805K")
      (libsource (lib "eagle-import") (part "C-USC0805K"))
    )
    (comp (ref "C17")
      (value "0.1uF")
      (footprint "eagle-import:C0805K")
      (libsource (lib "eagle-import") (part "C-USC0805K"))
    )
    (comp (ref "C18")
      (value "0.1uF")
      (footprint "eagle-import:C0805K")
      (libsource (lib "eagle-import") (part "C-USC0805K"))
    )
    (comp (ref "ETH1")
      (value "USR_ES1_W5500")
      (footprint "eagle-import:USR_ES1_W5500")
      (libsource (lib "eagle-import") (part "USR_ES1_W5500"))
    )
    (comp (ref "J9")
      (value "STRIP2")
      (footprint "eagle-import:STRIP2")
      (libsource (lib "eagle-import") (part "STRIP2"))
    )
    (comp (ref "J11")
      (value "STRIP2")
      (footprint "eagle-import:STRIP2")
      (libsource (lib "eagle-import") (part "STRIP2"))
    )
    (comp (ref "J66")
      (value "STRIP2")
      (footprint "eagle-import:STRIP2")
      (libsource (lib "eagle-import") (part "STRIP2"))
    )
    (comp (ref "J67")
      (value "STRIP2")
      (footprint "eagle-import:STRIP2")
      (libsource (lib "eagle-import") (part "STRIP2"))
    )
    (comp (ref "J68")
      (value "STRIP2")
      (footprint "eagle-import:STRIP2")
      (libsource (lib "eagle-import") (part "STRIP2"))
    )
    (comp (ref "J69")
      (value "STRIP2")
      (footprint "eagle-import:STRIP2")
      (libsource (lib "eagle-import") (part "STRIP2"))
    )
    (comp (ref "R25")
      (value "10K")
      (footprint "eagle-import:M1206")
      (libsource (lib "eagle-import") (part "R-US_M1206"))
    )
    (comp (ref "SV1")
      (value "MA05-2")
      (footprint "eagle-import:MA05-2")
      (libsource (lib "eagle-import") (part "MA05-2"))
    )
    (comp (ref "SV3")
      (value "MA05-2")
      (footprint "eagle-import:MA05-2")
      (libsource (lib "eagle-import") (part "MA05-2"))
    )
    (comp (ref "SV4")
      (value "MA07-2")
      (footprint "eagle-import:MA07-2")
      (libsource (lib "eagle-import") (part "MA07-2"))
    )
    (comp (ref "SV6")
      (value "MA05-2")
      (footprint "eagle-import:MA05-2")
      (libsource (lib "eagle-import") (part "MA05-2"))
    )
    (comp (ref "SV7")
      (value "MA06-2")
      (footprint "eagle-import:MA06-2")
      (libsource (lib "eagle-import") (part "MA06-2"))
    )
    (comp (ref "SV11")
      (value "MA06-2")
      (footprint "eagle-import:MA06-2")
      (libsource (lib "eagle-import") (part "MA06-2"))
    )
    (comp (ref "SV22")
      (value "MA07-2")
      (footprint "eagle-import:MA07-2")
      (libsource (lib "eagle-import") (part "MA07-2"))
    )
    (comp (ref "SV27")
      (value "MA07-2")
      (footprint "eagle-import:MA07-2")
      (libsource (lib "eagle-import") (part "MA07-2"))
    )
    (comp (ref "U2")
      (value "MAX3232IDWR")
      (footprint "eagle-import:SO16W")
      (libsource (lib "eagle-import") (part "MAX3232IDWR"))
    )
    (comp (ref "U3")
      (value "IS62WVS512")
      (footprint "eagle-import:SO08")
      (libsource (lib "eagle-import") (part "IS62WVS512"))
    )
    (comp (ref "U4")
      (value "MAX3232IDWR")
      (footprint "eagle-import:SO16W")
      (libsource (lib "eagle-import") (part "MAX3232IDWR"))
    )
    (comp (ref "X1")
      (value "M09HP")
      (footprint "eagle-import:M09HP")
      (libsource (lib "eagle-import") (part "M09HP"))
    )
    (comp (ref "B3")
      (value "GND SCOPE")
      (footprint "eagle-import:BANANA_MALE")
      (libsource (lib "eagle-import") (part "BANANA_MALE"))
    )
    (comp (ref "B4")
      (value "ADC SCOPE")
      (footprint "eagle-import:BANANA_MALE")
      (libsource (lib "eagle-import") (part "BANANA_MALE"))
    )
    (comp (ref "B5")
      (value "DAC SCOPE")
      (footprint "eagle-import:BANANA_MALE")
      (libsource (lib "eagle-import") (part "BANANA_MALE"))
    )
    (comp (ref "C6")
      (value "0.1uf")
      (footprint "eagle-import:C1206")
      (libsource (lib "eagle-import") (part "C-USC1206"))
    )
    (comp (ref "J10")
      (value "STRIP3")
      (footprint "eagle-import:STRIP3")
      (libsource (lib "eagle-import") (part "STRIP3"))
    )
    (comp (ref "J14")
      (value "STRIP3")
      (footprint "eagle-import:STRIP3")
      (libsource (lib "eagle-import") (part "STRIP3"))
    )
    (comp (ref "J15")
      (value "STRIP3")
      (footprint "eagle-import:STRIP3")
      (libsource (lib "eagle-import") (part "STRIP3"))
    )
    (comp (ref "J16")
      (value "STRIP3")
      (footprint "eagle-import:STRIP3")
      (libsource (lib "eagle-import") (part "STRIP3"))
    )
    (comp (ref "J17")
      (value "STRIP3")
      (footprint "eagle-import:STRIP3")
      (libsource (lib "eagle-import") (part "STRIP3"))
    )
    (comp (ref "J18")
      (value "STRIP3")
      (footprint "eagle-import:STRIP3")
      (libsource (lib "eagle-import") (part "STRIP3"))
    )
    (comp (ref "J19")
      (value "STRIP3")
      (footprint "eagle-import:STRIP3")
      (libsource (lib "eagle-import") (part "STRIP3"))
    )
    (comp (ref "J20")
      (value "STRIP3")
      (footprint "eagle-import:STRIP3")
      (libsource (lib "eagle-import") (part "STRIP3"))
    )
    (comp (ref "J21")
      (value "STRIP3")
      (footprint "eagle-import:STRIP3")
      (libsource (lib "eagle-import") (part "STRIP3"))
    )
    (comp (ref "J28")
      (value "STRIP3")
      (footprint "eagle-import:STRIP3")
      (libsource (lib "eagle-import") (part "STRIP3"))
    )
    (comp (ref "J29")
      (value "STRIP3")
      (footprint "eagle-import:STRIP3")
      (libsource (lib "eagle-import") (part "STRIP3"))
    )
    (comp (ref "J30")
      (value "STRIP3")
      (footprint "eagle-import:STRIP3")
      (libsource (lib "eagle-import") (part "STRIP3"))
    )
    (comp (ref "J31")
      (value "STRIP3")
      (footprint "eagle-import:STRIP3")
      (libsource (lib "eagle-import") (part "STRIP3"))
    )
    (comp (ref "J32")
      (value "STRIP3")
      (footprint "eagle-import:STRIP3")
      (libsource (lib "eagle-import") (part "STRIP3"))
    )
    (comp (ref "J33")
      (value "STRIP3")
      (footprint "eagle-import:STRIP3")
      (libsource (lib "eagle-import") (part "STRIP3"))
    )
    (comp (ref "J98")
      (value "STRIP3")
      (footprint "eagle-import:STRIP3")
      (libsource (lib "eagle-import") (part "STRIP3"))
    )
    (comp (ref "J99")
      (value "STRIP3")
      (footprint "eagle-import:STRIP3")
      (libsource (lib "eagle-import") (part "STRIP3"))
    )
    (comp (ref "J100")
      (value "STRIP3")
      (footprint "eagle-import:STRIP3")
      (libsource (lib "eagle-import") (part "STRIP3"))
    )
    (comp (ref "J101")
      (value "STRIP3")
      (footprint "eagle-import:STRIP3")
      (libsource (lib "eagle-import") (part "STRIP3"))
    )
    (comp (ref "J102")
      (value "STRIP3")
      (footprint "eagle-import:STRIP3")
      (libsource (lib "eagle-import") (part "STRIP3"))
    )
    (comp (ref "J103")
      (value "STRIP3")
      (footprint "eagle-import:STRIP3")
      (libsource (lib "eagle-import") (part "STRIP3"))
    )
    (comp (ref "J104")
      (value "STRIP3")
      (footprint "eagle-import:STRIP3")
      (libsource (lib "eagle-import") (part "STRIP3"))
    )
    (comp (ref "J105")
      (value "STRIP3")
      (footprint "eagle-import:STRIP3")
      (libsource (lib "eagle-import") (part "STRIP3"))
    )
    (comp (ref "J106")
      (value "STRIP3")
      (footprint "eagle-import:STRIP3")
      (libsource (lib "eagle-import") (part "STRIP3"))
    )
    (comp (ref "J107")
      (value "STRIP3")
      (footprint "eagle-import:STRIP3")
      (libsource (lib "eagle-import") (part "STRIP3"))
    )
    (comp (ref "J108")
      (value "STRIP3")
      (footprint "eagle-import:STRIP3")
      (libsource (lib "eagle-import") (part "STRIP3"))
    )
    (comp (ref "J109")
      (value "STRIP3")
      (footprint "eagle-import:STRIP3")
      (libsource (lib "eagle-import") (part "STRIP3"))
    )
    (comp (ref "J110")
      (value "STRIP3")
      (footprint "eagle-import:STRIP3")
      (libsource (lib "eagle-import") (part "STRIP3"))
    )
    (comp (ref "J111")
      (value "STRIP3")
      (footprint "eagle-import:STRIP3")
      (libsource (lib "eagle-import") (part "STRIP3"))
    )
    (comp (ref "J112")
      (value "STRIP3")
      (footprint "eagle-import:STRIP3")
      (libsource (lib "eagle-import") (part "STRIP3"))
    )
    (comp (ref "J113")
      (value "STRIP3")
      (footprint "eagle-import:STRIP3")
      (libsource (lib "eagle-import") (part "STRIP3"))
    )
    (comp (ref "J114")
      (value "STRIP3")
      (footprint "eagle-import:STRIP3")
      (libsource (lib "eagle-import") (part "STRIP3"))
    )
    (comp (ref "J115")
      (value "STRIP3")
      (footprint "eagle-import:STRIP3")
      (libsource (lib "eagle-import") (part "STRIP3"))
    )
    (comp (ref "J116")
      (value "STRIP3")
      (footprint "eagle-import:STRIP3")
      (libsource (lib "eagle-import") (part "STRIP3"))
    )
    (comp (ref "J117")
      (value "STRIP3")
      (footprint "eagle-import:STRIP3")
      (libsource (lib "eagle-import") (part "STRIP3"))
    )
    (comp (ref "J118")
      (value "STRIP3")
      (footprint "eagle-import:STRIP3")
      (libsource (lib "eagle-import") (part "STRIP3"))
    )
    (comp (ref "J119")
      (value "STRIP3")
      (footprint "eagle-import:STRIP3")
      (libsource (lib "eagle-import") (part "STRIP3"))
    )
    (comp (ref "J120")
      (value "STRIP3")
      (footprint "eagle-import:STRIP3")
      (libsource (lib "eagle-import") (part "STRIP3"))
    )
    (comp (ref "J121")
      (value "STRIP3")
      (footprint "eagle-import:STRIP3")
      (libsource (lib "eagle-import") (part "STRIP3"))
    )
    (comp (ref "J122")
      (value "STRIP3")
      (footprint "eagle-import:STRIP3")
      (libsource (lib "eagle-import") (part "STRIP3"))
    )
    (comp (ref "J133")
      (value "STRIP3")
      (footprint "eagle-import:STRIP3")
      (libsource (lib "eagle-import") (part "STRIP3"))
    )
    (comp (ref "J134")
      (value "STRIP3")
      (footprint "eagle-import:STRIP3")
      (libsource (lib "eagle-import") (part "STRIP3"))
    )
    (comp (ref "J135")
      (value "STRIP3")
      (footprint "eagle-import:STRIP3")
      (libsource (lib "eagle-import") (part "STRIP3"))
    )
    (comp (ref "J136")
      (value "STRIP3")
      (footprint "eagle-import:STRIP3")
      (libsource (lib "eagle-import") (part "STRIP3"))
    )
    (comp (ref "J137")
      (value "STRIP3")
      (footprint "eagle-import:STRIP3")
      (libsource (lib "eagle-import") (part "STRIP3"))
    )
    (comp (ref "J138")
      (value "STRIP3")
      (footprint "eagle-import:STRIP3")
      (libsource (lib "eagle-import") (part "STRIP3"))
    )
    (comp (ref "J139")
      (value "STRIP3")
      (footprint "eagle-import:STRIP3")
      (libsource (lib "eagle-import") (part "STRIP3"))
    )
    (comp (ref "J140")
      (value "STRIP3")
      (footprint "eagle-import:STRIP3")
      (libsource (lib "eagle-import") (part "STRIP3"))
    )
    (comp (ref "J141")
      (value "STRIP3")
      (footprint "eagle-import:STRIP3")
      (libsource (lib "eagle-import") (part "STRIP3"))
    )
    (comp (ref "J142")
      (value "STRIP3")
      (footprint "eagle-import:STRIP3")
      (libsource (lib "eagle-import") (part "STRIP3"))
    )
    (comp (ref "J143")
      (value "STRIP3")
      (footprint "eagle-import:STRIP3")
      (libsource (lib "eagle-import") (part "STRIP3"))
    )
    (comp (ref "J144")
      (value "STRIP3")
      (footprint "eagle-import:STRIP3")
      (libsource (lib "eagle-import") (part "STRIP3"))
    )
    (comp (ref "J145")
      (value "STRIP3")
      (footprint "eagle-import:STRIP3")
      (libsource (lib "eagle-import") (part "STRIP3"))
    )
    (comp (ref "J146")
      (value "STRIP3")
      (footprint "eagle-import:STRIP3")
      (libsource (lib "eagle-import") (part "STRIP3"))
    )
    (comp (ref "J147")
      (value "STRIP3")
      (footprint "eagle-import:STRIP3")
      (libsource (lib "eagle-import") (part "STRIP3"))
    )
    (comp (ref "J148")
      (value "STRIP3")
      (footprint "eagle-import:STRIP3")
      (libsource (lib "eagle-import") (part "STRIP3"))
    )
    (comp (ref "J149")
      (value "STRIP3")
      (footprint "eagle-import:STRIP3")
      (libsource (lib "eagle-import") (part "STRIP3"))
    )
    (comp (ref "J150")
      (value "STRIP3")
      (footprint "eagle-import:STRIP3")
      (libsource (lib "eagle-import") (part "STRIP3"))
    )
    (comp (ref "J151")
      (value "STRIP3")
      (footprint "eagle-import:STRIP3")
      (libsource (lib "eagle-import") (part "STRIP3"))
    )
    (comp (ref "J152")
      (value "STRIP3")
      (footprint "eagle-import:STRIP3")
      (libsource (lib "eagle-import") (part "STRIP3"))
    )
    (comp (ref "J153")
      (value "STRIP3")
      (footprint "eagle-import:STRIP3")
      (libsource (lib "eagle-import") (part "STRIP3"))
    )
    (comp (ref "J154")
      (value "STRIP3")
      (footprint "eagle-import:STRIP3")
      (libsource (lib "eagle-import") (part "STRIP3"))
    )
    (comp (ref "J155")
      (value "STRIP3")
      (footprint "eagle-import:STRIP3")
      (libsource (lib "eagle-import") (part "STRIP3"))
    )
    (comp (ref "J156")
      (value "STRIP3")
      (footprint "eagle-import:STRIP3")
      (libsource (lib "eagle-import") (part "STRIP3"))
    )
    (comp (ref "J157")
      (value "STRIP3")
      (footprint "eagle-import:STRIP3")
      (libsource (lib "eagle-import") (part "STRIP3"))
    )
    (comp (ref "J158")
      (value "STRIP3")
      (footprint "eagle-import:STRIP3")
      (libsource (lib "eagle-import") (part "STRIP3"))
    )
    (comp (ref "J159")
      (value "STRIP3")
      (footprint "eagle-import:STRIP3")
      (libsource (lib "eagle-import") (part "STRIP3"))
    )
    (comp (ref "J160")
      (value "STRIP3")
      (footprint "eagle-import:STRIP3")
      (libsource (lib "eagle-import") (part "STRIP3"))
    )
    (comp (ref "J161")
      (value "STRIP3")
      (footprint "eagle-import:STRIP3")
      (libsource (lib "eagle-import") (part "STRIP3"))
    )
    (comp (ref "J162")
      (value "STRIP3")
      (footprint "eagle-import:STRIP3")
      (libsource (lib "eagle-import") (part "STRIP3"))
    )
    (comp (ref "J163")
      (value "STRIP3")
      (footprint "eagle-import:STRIP3")
      (libsource (lib "eagle-import") (part "STRIP3"))
    )
    (comp (ref "J164")
      (value "STRIP3")
      (footprint "eagle-import:STRIP3")
      (libsource (lib "eagle-import") (part "STRIP3"))
    )
    (comp (ref "J165")
      (value "STRIP3")
      (footprint "eagle-import:STRIP3")
      (libsource (lib "eagle-import") (part "STRIP3"))
    )
    (comp (ref "J166")
      (value "STRIP3")
      (footprint "eagle-import:STRIP3")
      (libsource (lib "eagle-import") (part "STRIP3"))
    )
    (comp (ref "J167")
      (value "STRIP3")
      (footprint "eagle-import:STRIP3")
      (libsource (lib "eagle-import") (part "STRIP3"))
    )
    (comp (ref "J168")
      (value "STRIP3")
      (footprint "eagle-import:STRIP3")
      (libsource (lib "eagle-import") (part "STRIP3"))
    )
    (comp (ref "J169")
      (value "STRIP3")
      (footprint "eagle-import:STRIP3")
      (libsource (lib "eagle-import") (part "STRIP3"))
    )
    (comp (ref "J170")
      (value "STRIP3")
      (footprint "eagle-import:STRIP3")
      (libsource (lib "eagle-import") (part "STRIP3"))
    )
    (comp (ref "J176")
      (value "STRIP3")
      (footprint "eagle-import:STRIP3")
      (libsource (lib "eagle-import") (part "STRIP3"))
    )
    (comp (ref "J177")
      (value "STRIP3")
      (footprint "eagle-import:STRIP3")
      (libsource (lib "eagle-import") (part "STRIP3"))
    )
    (comp (ref "L1")
      (value "F28379D_LAUNCHPAD")
      (footprint "eagle-import:F28379D_LAUNCHPAD")
      (libsource (lib "eagle-import") (part "F28379D_LAUNCHPAD"))
    )
    (comp (ref "R17")
      (value "R-US_R1206")
      (footprint "eagle-import:R1206")
      (libsource (lib "eagle-import") (part "R-US_R1206"))
    )
    (comp (ref "R18")
      (value "R-US_R1206")
      (footprint "eagle-import:R1206")
      (libsource (lib "eagle-import") (part "R-US_R1206"))
    )
    (comp (ref "R21")
      (value "R-US_R1206")
      (footprint "eagle-import:R1206")
      (libsource (lib "eagle-import") (part "R-US_R1206"))
    )
    (comp (ref "R22")
      (value "R-US_R1206")
      (footprint "eagle-import:R1206")
      (libsource (lib "eagle-import") (part "R-US_R1206"))
    )
    (comp (ref "SV8")
      (value "MA05-1")
      (footprint "eagle-import:MA05-1")
      (libsource (lib "eagle-import") (part "MA05-1"))
    )
    (comp (ref "SV9")
      (value "MA05-1")
      (footprint "eagle-import:MA05-1")
      (libsource (lib "eagle-import") (part "MA05-1"))
    )
    (comp (ref "SV10")
      (value "MA05-1")
      (footprint "eagle-import:MA05-1")
      (libsource (lib "eagle-import") (part "MA05-1"))
    )
    (comp (ref "SV12")
      (value "MA05-1")
      (footprint "eagle-import:MA05-1")
      (libsource (lib "eagle-import") (part "MA05-1"))
    )
    (comp (ref "SV13")
      (value "MA03-1")
      (footprint "eagle-import:MA03-1")
      (libsource (lib "eagle-import") (part "MA03-1"))
    )
    (comp (ref "SV14")
      (value "MA03-1")
      (footprint "eagle-import:MA03-1")
      (libsource (lib "eagle-import") (part "MA03-1"))
    )
    (comp (ref "SV19")
      (value "MA05-1")
      (footprint "eagle-import:MA05-1")
      (libsource (lib "eagle-import") (part "MA05-1"))
    )
    (comp (ref "SV30")
      (value "MA05-1")
      (footprint "eagle-import:MA05-1")
      (libsource (lib "eagle-import") (part "MA05-1"))
    )
    (comp (ref "U5")
      (value "MAX4506")
      (footprint "eagle-import:SOIC-8")
      (libsource (lib "eagle-import") (part "MAX4506-SOIC8"))
    )
  )
  (nets
    (net (code "1") (name "+3.3V") (class "Default")
      (node (ref "C11") (pin "1") (pinfunction "1_1") (pintype "passive"))
      (node (ref "C12") (pin "1") (pinfunction "1_1") (pintype "passive"))
      (node (ref "C13") (pin "1") (pinfunction "1_1") (pintype "passive"))
      (node (ref "C14") (pin "1") (pinfunction "1_1") (pintype "passive"))
      (node (ref "C21") (pin "1") (pinfunction "1_1") (pintype "passive"))
      (node (ref "C23") (pin "1") (pinfunction "1_1") (pintype "passive"))
      (node (ref "C4") (pin "1") (pinfunction "1_1") (pintype "passive"))
      (node (ref "C5") (pin "1") (pinfunction "1_1") (pintype "passive"))
      (node (ref "C6") (pin "1") (pinfunction "1_1") (pintype "passive"))
      (node (ref "ETH1") (pin "P$10") (pinfunction "3V3_1_P$10") (pintype "bidirectional"))
      (node (ref "ETH1") (pin "P$11") (pinfunction "3V3_2_P$11") (pintype "bidirectional"))
      (node (ref "IC4") (pin "14") (pinfunction "VCC_14") (pintype "power_in"))
      (node (ref "J10") (pin "P$1") (pinfunction "P$1_P$1") (pintype "bidirectional"))
      (node (ref "J10") (pin "P$2") (pinfunction "P$2_P$2") (pintype "bidirectional"))
      (node (ref "J10") (pin "P$3") (pinfunction "P$3_P$3") (pintype "bidirectional"))
      (node (ref "J123") (pin "P$1") (pinfunction "P$1_P$1") (pintype "bidirectional"))
      (node (ref "J123") (pin "P$2") (pinfunction "P$2_P$2") (pintype "bidirectional"))
      (node (ref "J123") (pin "P$3") (pinfunction "P$3_P$3") (pintype "bidirectional"))
      (node (ref "J177") (pin "P$1") (pinfunction "P$1_P$1") (pintype "bidirectional"))
      (node (ref "J177") (pin "P$2") (pinfunction "P$2_P$2") (pintype "bidirectional"))
      (node (ref "J177") (pin "P$3") (pinfunction "P$3_P$3") (pintype "bidirectional"))
      (node (ref "L1") (pin "P$1") (pinfunction "3.3V_1_P$1") (pintype "bidirectional"))
      (node (ref "L1") (pin "P$41") (pinfunction "3.3V_2_P$41") (pintype "bidirectional"))
      (node (ref "R17") (pin "2") (pinfunction "2_2") (pintype "passive"))
      (node (ref "R18") (pin "2") (pinfunction "2_2") (pintype "passive"))
      (node (ref "R19") (pin "2") (pinfunction "2_2") (pintype "passive"))
      (node (ref "R2") (pin "1") (pinfunction "1_1") (pintype "passive"))
      (node (ref "R20") (pin "2") (pinfunction "2_2") (pintype "passive"))
      (node (ref "R23") (pin "2") (pinfunction "2_2") (pintype "passive"))
      (node (ref "R24") (pin "2") (pinfunction "2_2") (pintype "passive"))
      (node (ref "R25") (pin "2") (pinfunction "2_2") (pintype "passive"))
      (node (ref "R3") (pin "1") (pinfunction "1_1") (pintype "passive"))
      (node (ref "R34") (pin "1") (pinfunction "1_1") (pintype "passive"))
      (node (ref "R35") (pin "1") (pinfunction "1_1") (pintype "passive"))
      (node (ref "R36") (pin "2") (pinfunction "2_2") (pintype "passive"))
      (node (ref "R37") (pin "2") (pinfunction "2_2") (pintype "passive"))
      (node (ref "R38") (pin "2") (pinfunction "2_2") (pintype "passive"))
      (node (ref "R4") (pin "1") (pinfunction "1_1") (pintype "passive"))
      (node (ref "R5") (pin "1") (pinfunction "1_1") (pintype "passive"))
      (node (ref "R6") (pin "1") (pinfunction "1_1") (pintype "passive"))
      (node (ref "R8") (pin "1") (pinfunction "1_1") (pintype "passive"))
      (node (ref "SV10") (pin "2") (pinfunction "2_2") (pintype "passive"))
      (node (ref "SV11") (pin "1") (pinfunction "1_1") (pintype "passive"))
      (node (ref "SV11") (pin "2") (pinfunction "2_2") (pintype "passive"))
      (node (ref "SV15") (pin "5") (pinfunction "5_5") (pintype "passive"))
      (node (ref "SV18") (pin "4") (pinfunction "4_4") (pintype "passive"))
      (node (ref "SV19") (pin "2") (pinfunction "2_2") (pintype "passive"))
      (node (ref "SV26") (pin "4") (pinfunction "4_4") (pintype "passive"))
      (node (ref "SV30") (pin "2") (pinfunction "2_2") (pintype "passive"))
      (node (ref "SV75") (pin "1") (pinfunction "1_1") (pintype "passive"))
      (node (ref "SV75") (pin "3") (pinfunction "3_3") (pintype "passive"))
      (node (ref "SV75") (pin "5") (pinfunction "5_5") (pintype "passive"))
      (node (ref "U$1") (pin "1") (pinfunction "P1_VCC_1") (pintype "bidirectional"))
      (node (ref "U11") (pin "22") (pinfunction "VDDA_22") (pintype "bidirectional"))
      (node (ref "U11") (pin "4") (pinfunction "VDDIO_4") (pintype "bidirectional"))
      (node (ref "U12") (pin "P$4") (pinfunction "OUT_P$4") (pintype "bidirectional"))
      (node (ref "U12") (pin "P$5") (pinfunction "SENSE_P$5") (pintype "bidirectional"))
      (node (ref "U15") (pin "P$3") (pinfunction "P3_3.3V_P$3") (pintype "bidirectional"))
      (node (ref "U2") (pin "16") (pinfunction "VCC_16") (pintype "bidirectional"))
      (node (ref "U3") (pin "8") (pinfunction "VCC_8") (pintype "bidirectional"))
      (node (ref "U4") (pin "16") (pinfunction "VCC_16") (pintype "bidirectional"))
      (node (ref "U5") (pin "P$8") (pinfunction "V+_P$8") (pintype "bidirectional"))
    )
    (net (code "2") (name "+5V") (class "Default")
      (node (ref "C22") (pin "1") (pinfunction "1_1") (pintype "passive"))
      (node (ref "C30") (pin "1") (pinfunction "1_1") (pintype "passive"))
      (node (ref "C31") (pin "1") (pinfunction "1_1") (pintype "passive"))
      (node (ref "C32") (pin "1") (pinfunction "1_1") (pintype "passive"))
      (node (ref "C33") (pin "1") (pinfunction "1_1") (pintype "passive"))
      (node (ref "C34") (pin "1") (pinfunction "1_1") (pintype "passive"))
      (node (ref "C37") (pin "1") (pinfunction "1_1") (pintype "passive"))
      (node (ref "C38") (pin "1") (pinfunction "1_1") (pintype "passive"))
      (node (ref "C39") (pin "1") (pinfunction "1_1") (pintype "passive"))
      (node (ref "C40") (pin "1") (pinfunction "1_1") (pintype "passive"))
      (node (ref "C47") (pin "1") (pinfunction "1_1") (pintype "passive"))
      (node (ref "C48") (pin "1") (pinfunction "1_1") (pintype "passive"))
      (node (ref "C49") (pin "1") (pinfunction "1_1") (pintype "passive"))
      (node (ref "IC2") (pin "24") (pinfunction "VCC_24") (pintype "power_in"))
      (node (ref "IC3") (pin "1") (pinfunction "AVCC_1") (pintype "bidirectional"))
      (node (ref "IC3") (pin "13") (pinfunction "PDD_13") (pintype "bidirectional"))
      (node (ref "J103") (pin "P$1") (pinfunction "P$1_P$1") (pintype "bidirectional"))
      (node (ref "J103") (pin "P$2") (pinfunction "P$2_P$2") (pintype "bidirectional"))
      (node (ref "J103") (pin "P$3") (pinfunction "P$3_P$3") (pintype "bidirectional"))
      (node (ref "J152") (pin "P$1") (pinfunction "P$1_P$1") (pintype "bidirectional"))
      (node (ref "J152") (pin "P$2") (pinfunction "P$2_P$2") (pintype "bidirectional"))
      (node (ref "J152") (pin "P$3") (pinfunction "P$3_P$3") (pintype "bidirectional"))
      (node (ref "L1") (pin "P$21") (pinfunction "5V_1_P$21") (pintype "bidirectional"))
      (node (ref "L1") (pin "P$61") (pinfunction "5V_2_P$61") (pintype "bidirectional"))
      (node (ref "P3") (pin "P$2") (pinfunction "POWER_P$2") (pintype "bidirectional"))
      (node (ref "QG1") (pin "14") (pinfunction "VCC_14") (pintype "power_in"))
      (node (ref "R21") (pin "2") (pinfunction "2_2") (pintype "passive"))
      (node (ref "R22") (pin "2") (pinfunction "2_2") (pintype "passive"))
      (node (ref "R33") (pin "2") (pinfunction "2_2") (pintype "passive"))
      (node (ref "SV12") (pin "2") (pinfunction "2_2") (pintype "passive"))
      (node (ref "SV17") (pin "3") (pinfunction "3_3") (pintype "passive"))
      (node (ref "SV17") (pin "4") (pinfunction "4_4") (pintype "passive"))
      (node (ref "SV18") (pin "3") (pinfunction "3_3") (pintype "passive"))
      (node (ref "SV21") (pin "7") (pinfunction "7_7") (pintype "passive"))
      (node (ref "SV21") (pin "8") (pinfunction "8_8") (pintype "passive"))
      (node (ref "SV23") (pin "7") (pinfunction "7_7") (pintype "passive"))
      (node (ref "SV23") (pin "8") (pinfunction "8_8") (pintype "passive"))
      (node (ref "SV24") (pin "7") (pinfunction "7_7") (pintype "passive"))
      (node (ref "SV24") (pin "8") (pinfunction "8_8") (pintype "passive"))
      (node (ref "SV25") (pin "3") (pinfunction "3_3") (pintype "passive"))
      (node (ref "SV25") (pin "4") (pinfunction "4_4") (pintype "passive"))
      (node (ref "SV26") (pin "3") (pinfunction "3_3") (pintype "passive"))
      (node (ref "SV28") (pin "8") (pinfunction "8_8") (pintype "passive"))
      (node (ref "SV45") (pin "1") (pinfunction "1_1") (pintype "passive"))
      (node (ref "SV45") (pin "3") (pinfunction "3_3") (pintype "passive"))
      (node (ref "SV45") (pin "5") (pinfunction "5_5") (pintype "passive"))
      (node (ref "SV8") (pin "2") (pinfunction "2_2") (pintype "passive"))
      (node (ref "SV9") (pin "2") (pinfunction "2_2") (pintype "passive"))
      (node (ref "U10") (pin "14") (pinfunction "VDD_14") (pintype "bidirectional"))
      (node (ref "U12") (pin "P$1") (pinfunction "~{SHDN}_P$1") (pintype "bidirectional"))
      (node (ref "U12") (pin "P$2") (pinfunction "IN_P$2") (pintype "bidirectional"))
      (node (ref "U7") (pin "14") (pinfunction "VDD_14") (pintype "bidirectional"))
      (node (ref "U8") (pin "14") (pinfunction "VDD_14") (pintype "bidirectional"))
      (node (ref "U9") (pin "14") (pinfunction "VDD_14") (pintype "bidirectional"))
    )
    (net (code "3") (name "28027_GPIO0") (class "Default")
      (node (ref "SV17") (pin "9") (pinfunction "9_9") (pintype "passive"))
      (node (ref "U11") (pin "37") (pinfunction "GPIO0/EPWM1A_37") (pintype "bidirectional"))
    )
    (net (code "4") (name "28027_GPIO1") (class "Default")
      (node (ref "SV17") (pin "7") (pinfunction "7_7") (pintype "passive"))
      (node (ref "U11") (pin "36") (pinfunction "GPIO1/EPWM1A_36") (pintype "bidirectional"))
    )
    (net (code "5") (name "28027_GPIO2") (class "Default")
      (node (ref "SV17") (pin "5") (pinfunction "5_5") (pintype "passive"))
      (node (ref "U11") (pin "5") (pinfunction "GPIO2/EPWM2A_5") (pintype "bidirectional"))
    )
    (net (code "6") (name "28027_GPIO3") (class "Default")
      (node (ref "SV17") (pin "10") (pinfunction "10_10") (pintype "passive"))
      (node (ref "U11") (pin "6") (pinfunction "GPIO3/EPWM2B_6") (pintype "bidirectional"))
    )
    (net (code "7") (name "28027_GPIO4") (class "Default")
      (node (ref "SV17") (pin "8") (pinfunction "8_8") (pintype "passive"))
      (node (ref "U11") (pin "7") (pinfunction "GPIO4/EPWM3A_7") (pintype "bidirectional"))
    )
    (net (code "8") (name "28027_GPIO5") (class "Default")
      (node (ref "SV17") (pin "6") (pinfunction "6_6") (pintype "passive"))
      (node (ref "U11") (pin "8") (pinfunction "GPIO5/EPWM3B_8") (pintype "bidirectional"))
    )
    (net (code "9") (name "28027_GPIO6") (class "Default")
      (node (ref "SV18") (pin "9") (pinfunction "9_9") (pintype "passive"))
      (node (ref "U11") (pin "9") (pinfunction "GPIO6/EPWM4A_9") (pintype "bidirectional"))
    )
    (net (code "10") (name "28027_GPIO7") (class "Default")
      (node (ref "SV18") (pin "7") (pinfunction "7_7") (pintype "passive"))
      (node (ref "U11") (pin "10") (pinfunction "GPIO7/EPWM4B_10") (pintype "bidirectional"))
    )
    (net (code "11") (name "28027_GPIO12") (class "Default")
      (node (ref "SV16") (pin "4") (pinfunction "4_4") (pintype "passive"))
      (node (ref "U11") (pin "13") (pinfunction "GPIO12/SCITXDA_13") (pintype "bidirectional"))
    )
    (net (code "12") (name "28027_GPIO34") (class "Default")
      (node (ref "LED17") (pin "C") (pinfunction "C_C") (pintype "passive"))
      (node (ref "R37") (pin "1") (pinfunction "1_1") (pintype "passive"))
      (node (ref "U11") (pin "27") (pinfunction "GPIO34_27") (pintype "bidirectional"))
    )
    (net (code "13") (name "28027_SCL") (class "Default")
      (node (ref "R34") (pin "2") (pinfunction "2_2") (pintype "passive"))
      (node (ref "SV16") (pin "3") (pinfunction "3_3") (pintype "passive"))
      (node (ref "U11") (pin "15") (pinfunction "GPIO29/SCITXDA_15") (pintype "bidirectional"))
    )
    (net (code "14") (name "28027_SDA") (class "Default")
      (node (ref "R35") (pin "2") (pinfunction "2_2") (pintype "passive"))
      (node (ref "SV16") (pin "5") (pinfunction "5_5") (pintype "passive"))
      (node (ref "U11") (pin "14") (pinfunction "GPIO28/SCIRXDA_14") (pintype "bidirectional"))
    )
    (net (code "15") (name "28027_SPICLKA") (class "Default")
      (node (ref "J38") (pin "P$1") (pinfunction "P$1_P$1") (pintype "bidirectional"))
      (node (ref "U11") (pin "32") (pinfunction "GPIO18/SPICLKA/SCITXDA_32") (pintype "bidirectional"))
    )
    (net (code "16") (name "28027_SPISIMOA") (class "Default")
      (node (ref "J36") (pin "P$1") (pinfunction "P$1_P$1") (pintype "bidirectional"))
      (node (ref "U11") (pin "35") (pinfunction "GPIO16/SPISIMOA_35") (pintype "bidirectional"))
    )
    (net (code "17") (name "28027_SPISOMIA") (class "Default")
      (node (ref "J35") (pin "P$1") (pinfunction "P$1_P$1") (pintype "bidirectional"))
      (node (ref "U11") (pin "34") (pinfunction "GPIO17/SPISOMIA_34") (pintype "bidirectional"))
    )
    (net (code "18") (name "28027_SPISTEA") (class "Default")
      (node (ref "J37") (pin "P$1") (pinfunction "P$1_P$1") (pintype "bidirectional"))
      (node (ref "U11") (pin "33") (pinfunction "GPIO19//SPISTEA/SCIRXDA_33") (pintype "bidirectional"))
    )
    (net (code "19") (name "ADCA0") (class "Default")
      (node (ref "SV16") (pin "7") (pinfunction "7_7") (pintype "passive"))
      (node (ref "U11") (pin "21") (pinfunction "ADCINA0/VREFHI_21") (pintype "bidirectional"))
    )
    (net (code "20") (name "ADCA2") (class "Default")
      (node (ref "SV16") (pin "9") (pinfunction "9_9") (pintype "passive"))
      (node (ref "U11") (pin "20") (pinfunction "ADCINA2/AIO2_20") (pintype "bidirectional"))
    )
    (net (code "21") (name "ADCA4") (class "Default")
      (node (ref "SV16") (pin "8") (pinfunction "8_8") (pintype "passive"))
      (node (ref "U11") (pin "19") (pinfunction "ADCINA4/AIO4_19") (pintype "bidirectional"))
    )
    (net (code "22") (name "ADCA6") (class "Default")
      (node (ref "SV16") (pin "2") (pinfunction "2_2") (pintype "passive"))
      (node (ref "U11") (pin "18") (pinfunction "ADCINA6/AIO6_18") (pintype "bidirectional"))
    )
    (net (code "23") (name "ADCB2") (class "Default")
      (node (ref "SV16") (pin "10") (pinfunction "10_10") (pintype "passive"))
      (node (ref "U11") (pin "24") (pinfunction "ADCINB2/AIO10_24") (pintype "bidirectional"))
    )
    (net (code "24") (name "ADCB4") (class "Default")
      (node (ref "SV16") (pin "6") (pinfunction "6_6") (pintype "passive"))
      (node (ref "U11") (pin "25") (pinfunction "ADCINB4/AIO12_25") (pintype "bidirectional"))
    )
    (net (code "25") (name "ADCB6") (class "Default")
      (node (ref "U11") (pin "26") (pinfunction "ADCINB6/AIO14_26") (pintype "bidirectional"))
    )
    (net (code "26") (name "ADCIN14") (class "Default")
      (node (ref "J105") (pin "P$1") (pinfunction "P$1_P$1") (pintype "bidirectional"))
      (node (ref "J105") (pin "P$2") (pinfunction "P$2_P$2") (pintype "bidirectional"))
      (node (ref "J105") (pin "P$3") (pinfunction "P$3_P$3") (pintype "bidirectional"))
      (node (ref "L1") (pin "P$23") (pinfunction "ADCIN14_P$23") (pintype "bidirectional"))
    )
    (net (code "27") (name "ADCIN15") (class "Default")
      (node (ref "J150") (pin "P$1") (pinfunction "P$1_P$1") (pintype "bidirectional"))
      (node (ref "J150") (pin "P$2") (pinfunction "P$2_P$2") (pintype "bidirectional"))
      (node (ref "J150") (pin "P$3") (pinfunction "P$3_P$3") (pintype "bidirectional"))
      (node (ref "L1") (pin "P$63") (pinfunction "ADCIN15_P$63") (pintype "bidirectional"))
    )
    (net (code "28") (name "ADCINA2") (class "Default")
      (node (ref "J111") (pin "P$1") (pinfunction "P$1_P$1") (pintype "bidirectional"))
      (node (ref "J111") (pin "P$2") (pinfunction "P$2_P$2") (pintype "bidirectional"))
      (node (ref "J111") (pin "P$3") (pinfunction "P$3_P$3") (pintype "bidirectional"))
      (node (ref "L1") (pin "P$29") (pinfunction "ADCINA2_P$29") (pintype "bidirectional"))
    )
    (net (code "29") (name "ADCINA3") (class "Default")
      (node (ref "J108") (pin "P$1") (pinfunction "P$1_P$1") (pintype "bidirectional"))
      (node (ref "J108") (pin "P$2") (pinfunction "P$2_P$2") (pintype "bidirectional"))
      (node (ref "J108") (pin "P$3") (pinfunction "P$3_P$3") (pintype "bidirectional"))
      (node (ref "L1") (pin "P$26") (pinfunction "ADCINA3_P$26") (pintype "bidirectional"))
    )
    (net (code "30") (name "ADCINA4") (class "Default")
      (node (ref "J144") (pin "P$1") (pinfunction "P$1_P$1") (pintype "bidirectional"))
      (node (ref "J144") (pin "P$2") (pinfunction "P$2_P$2") (pintype "bidirectional"))
      (node (ref "J144") (pin "P$3") (pinfunction "P$3_P$3") (pintype "bidirectional"))
      (node (ref "L1") (pin "P$69") (pinfunction "ADCINA4_P$69") (pintype "bidirectional"))
    )
    (net (code "31") (name "ADCINA5") (class "Default")
      (node (ref "J147") (pin "P$1") (pinfunction "P$1_P$1") (pintype "bidirectional"))
      (node (ref "J147") (pin "P$2") (pinfunction "P$2_P$2") (pintype "bidirectional"))
      (node (ref "J147") (pin "P$3") (pinfunction "P$3_P$3") (pintype "bidirectional"))
      (node (ref "L1") (pin "P$66") (pinfunction "ADCINA5_P$66") (pintype "bidirectional"))
    )
    (net (code "32") (name "ADCINB2") (class "Default")
      (node (ref "J110") (pin "P$1") (pinfunction "P$1_P$1") (pintype "bidirectional"))
      (node (ref "J110") (pin "P$2") (pinfunction "P$2_P$2") (pintype "bidirectional"))
      (node (ref "J110") (pin "P$3") (pinfunction "P$3_P$3") (pintype "bidirectional"))
      (node (ref "L1") (pin "P$28") (pinfunction "ADCINB2_P$28") (pintype "bidirectional"))
    )
    (net (code "33") (name "ADCINB3") (class "Default")
      (node (ref "J107") (pin "P$1") (pinfunction "P$1_P$1") (pintype "bidirectional"))
      (node (ref "J107") (pin "P$2") (pinfunction "P$2_P$2") (pintype "bidirectional"))
      (node (ref "J107") (pin "P$3") (pinfunction "P$3_P$3") (pintype "bidirectional"))
      (node (ref "L1") (pin "P$25") (pinfunction "ADCINB3_P$25") (pintype "bidirectional"))
    )
    (net (code "34") (name "ADCINB4") (class "Default")
      (node (ref "J145") (pin "P$1") (pinfunction "P$1_P$1") (pintype "bidirectional"))
      (node (ref "J145") (pin "P$2") (pinfunction "P$2_P$2") (pintype "bidirectional"))
      (node (ref "J145") (pin "P$3") (pinfunction "P$3_P$3") (pintype "bidirectional"))
      (node (ref "L1") (pin "P$68") (pinfunction "ADCINB4_P$68") (pintype "bidirectional"))
      (node (ref "SV19") (pin "4") (pinfunction "4_4") (pintype "passive"))
    )
    (net (code "35") (name "ADCINB5") (class "Default")
      (node (ref "J148") (pin "P$1") (pinfunction "P$1_P$1") (pintype "bidirectional"))
      (node (ref "J148") (pin "P$2") (pinfunction "P$2_P$2") (pintype "bidirectional"))
      (node (ref "J148") (pin "P$3") (pinfunction "P$3_P$3") (pintype "bidirectional"))
      (node (ref "L1") (pin "P$65") (pinfunction "ADCINB5_P$65") (pintype "bidirectional"))
    )
    (net (code "36") (name "ADCINC2") (class "Default")
      (node (ref "J109") (pin "P$1") (pinfunction "P$1_P$1") (pintype "bidirectional"))
      (node (ref "J109") (pin "P$2") (pinfunction "P$2_P$2") (pintype "bidirectional"))
      (node (ref "J109") (pin "P$3") (pinfunction "P$3_P$3") (pintype "bidirectional"))
      (node (ref "L1") (pin "P$27") (pinfunction "ADCINC2_P$27") (pintype "bidirectional"))
      (node (ref "U15") (pin "P$4") (pinfunction "P4_Y_P$4") (pintype "bidirectional"))
    )
    (net (code "37") (name "ADCINC3") (class "Default")
      (node (ref "J106") (pin "P$1") (pinfunction "P$1_P$1") (pintype "bidirectional"))
      (node (ref "J106") (pin "P$2") (pinfunction "P$2_P$2") (pintype "bidirectional"))
      (node (ref "J106") (pin "P$3") (pinfunction "P$3_P$3") (pintype "bidirectional"))
      (node (ref "L1") (pin "P$24") (pinfunction "ADCINC3_P$24") (pintype "bidirectional"))
      (node (ref "U15") (pin "P$5") (pinfunction "P5_4Y_P$5") (pintype "bidirectional"))
    )
    (net (code "38") (name "ADCINC4") (class "Default")
      (node (ref "J146") (pin "P$1") (pinfunction "P$1_P$1") (pintype "bidirectional"))
      (node (ref "J146") (pin "P$2") (pinfunction "P$2_P$2") (pintype "bidirectional"))
      (node (ref "J146") (pin "P$3") (pinfunction "P$3_P$3") (pintype "bidirectional"))
      (node (ref "L1") (pin "P$67") (pinfunction "ADCINC4_P$67") (pintype "bidirectional"))
      (node (ref "U15") (pin "P$7") (pinfunction "P7_4X_P$7") (pintype "bidirectional"))
    )
    (net (code "39") (name "ADCINC5") (class "Default")
      (node (ref "J149") (pin "P$1") (pinfunction "P$1_P$1") (pintype "bidirectional"))
      (node (ref "J149") (pin "P$2") (pinfunction "P$2_P$2") (pintype "bidirectional"))
      (node (ref "J149") (pin "P$3") (pinfunction "P$3_P$3") (pintype "bidirectional"))
      (node (ref "L1") (pin "P$64") (pinfunction "ADCINC5_P$64") (pintype "bidirectional"))
      (node (ref "U15") (pin "P$8") (pinfunction "P8_X_P$8") (pintype "bidirectional"))
    )
    (net (code "40") (name "ADXRS300_3V3") (class "Default")
      (node (ref "J1") (pin "P$1") (pinfunction "P$1_P$1") (pintype "bidirectional"))
      (node (ref "J1") (pin "P$2") (pinfunction "P$2_P$2") (pintype "bidirectional"))
      (node (ref "R10") (pin "2") (pinfunction "2_2") (pintype "passive"))
      (node (ref "R9") (pin "1") (pinfunction "1_1") (pintype "passive"))
    )
    (net (code "41") (name "DACOUTA") (class "Default")
      (node (ref "J112") (pin "P$1") (pinfunction "P$1_P$1") (pintype "bidirectional"))
      (node (ref "J112") (pin "P$2") (pinfunction "P$2_P$2") (pintype "bidirectional"))
      (node (ref "J112") (pin "P$3") (pinfunction "P$3_P$3") (pintype "bidirectional"))
      (node (ref "L1") (pin "P$30") (pinfunction "ADCINA0/DACOUTA_P$30") (pintype "bidirectional"))
    )
    (net (code "42") (name "DACOUTB") (class "Default")
      (node (ref "J143") (pin "P$1") (pinfunction "P$1_P$1") (pintype "bidirectional"))
      (node (ref "J143") (pin "P$2") (pinfunction "P$2_P$2") (pintype "bidirectional"))
      (node (ref "J143") (pin "P$3") (pinfunction "P$3_P$3") (pintype "bidirectional"))
      (node (ref "L1") (pin "P$70") (pinfunction "ADCINA1/DACOUTB_P$70") (pintype "bidirectional"))
    )
    (net (code "43") (name "EQEP1A") (class "Default")
      (node (ref "J3") (pin "P$1") (pinfunction "P$1_P$1") (pintype "bidirectional"))
      (node (ref "J3") (pin "P$2") (pinfunction "P$2_P$2") (pintype "bidirectional"))
      (node (ref "SV21") (pin "5") (pinfunction "5_5") (pintype "passive"))
    )
    (net (code "44") (name "EQEP1B") (class "Default")
      (node (ref "J6") (pin "P$1") (pinfunction "P$1_P$1") (pintype "bidirectional"))
      (node (ref "J6") (pin "P$2") (pinfunction "P$2_P$2") (pintype "bidirectional"))
      (node (ref "SV21") (pin "9") (pinfunction "9_9") (pintype "passive"))
    )
    (net (code "45") (name "EQEP2A") (class "Default")
      (node (ref "J2") (pin "P$1") (pinfunction "P$1_P$1") (pintype "bidirectional"))
      (node (ref "J2") (pin "P$2") (pinfunction "P$2_P$2") (pintype "bidirectional"))
      (node (ref "SV21") (pin "6") (pinfunction "6_6") (pintype "passive"))
    )
    (net (code "46") (name "EQEP2B") (class "Default")
      (node (ref "J5") (pin "P$1") (pinfunction "P$1_P$1") (pintype "bidirectional"))
      (node (ref "J5") (pin "P$2") (pinfunction "P$2_P$2") (pintype "bidirectional"))
      (node (ref "SV21") (pin "10") (pinfunction "10_10") (pintype "passive"))
    )
    (net (code "47") (name "EQEP3A_5V") (class "Default")
      (node (ref "IC2") (pin "16") (pinfunction "A2_16") (pintype "bidirectional"))
      (node (ref "SV28") (pin "6") (pinfunction "6_6") (pintype "passive"))
    )
    (net (code "48") (name "EQEP3B_5V") (class "Default")
      (node (ref "IC2") (pin "14") (pinfunction "A1_14") (pintype "bidirectional"))
      (node (ref "SV28") (pin "10") (pinfunction "10_10") (pintype "passive"))
    )
    (net (code "49") (name "GND") (class "Default")
      (node (ref "B1") (pin "P$2") (pinfunction "P$2_P$2") (pintype "bidirectional"))
      (node (ref "B3") (pin "P$1") (pinfunction "P1_P$1") (pintype "bidirectional"))
      (node (ref "C10") (pin "2") (pinfunction "2_2") (pintype "passive"))
      (node (ref "C11") (pin "2") (pinfunction "2_2") (pintype "passive"))
      (node (ref "C12") (pin "2") (pinfunction "2_2") (pintype "passive"))
      (node (ref "C13") (pin "2") (pinfunction "2_2") (pintype "passive"))
      (node (ref "C14") (pin "2") (pinfunction "2_2") (pintype "passive"))
      (node (ref "C15") (pin "1") (pinfunction "1_1") (pintype "passive"))
      (node (ref "C18") (pin "2") (pinfunction "2_2") (pintype "passive"))
      (node (ref "C19") (pin "2") (pinfunction "2_2") (pintype "passive"))
      (node (ref "C20") (pin "2") (pinfunction "2_2") (pintype "passive"))
      (node (ref "C21") (pin "2") (pinfunction "2_2") (pintype "passive"))
      (node (ref "C22") (pin "2") (pinfunction "2_2") (pintype "passive"))
      (node (ref "C23") (pin "2") (pinfunction "2_2") (pintype "passive"))
      (node (ref "C24") (pin "2") (pinfunction "2_2") (pintype "passive"))
      (node (ref "C25") (pin "2") (pinfunction "2_2") (pintype "passive"))
      (node (ref "C26") (pin "2") (pinfunction "2_2") (pintype "passive"))
      (node (ref "C27") (pin "2") (pinfunction "2_2") (pintype "passive"))
      (node (ref "C28") (pin "2") (pinfunction "2_2") (pintype "passive"))
      (node (ref "C29") (pin "2") (pinfunction "2_2") (pintype "passive"))
      (node (ref "C30") (pin "2") (pinfunction "2_2") (pintype "passive"))
      (node (ref "C31") (pin "2") (pinfunction "2_2") (pintype "passive"))
      (node (ref "C32") (pin "2") (pinfunction "2_2") (pintype "passive"))
      (node (ref "C33") (pin "2") (pinfunction "2_2") (pintype "passive"))
      (node (ref "C34") (pin "2") (pinfunction "2_2") (pintype "passive"))
      (node (ref "C37") (pin "2") (pinfunction "2_2") (pintype "passive"))
      (node (ref "C38") (pin "2") (pinfunction "2_2") (pintype "passive"))
      (node (ref "C39") (pin "2") (pinfunction "2_2") (pintype "passive"))
      (node (ref "C4") (pin "2") (pinfunction "2_2") (pintype "passive"))
      (node (ref "C40") (pin "2") (pinfunction "2_2") (pintype "passive"))
      (node (ref "C47") (pin "2") (pinfunction "2_2") (pintype "passive"))
      (node (ref "C48") (pin "2") (pinfunction "2_2") (pintype "passive"))
      (node (ref "C49") (pin "2") (pinfunction "2_2") (pintype "passive"))
      (node (ref "C5") (pin "2") (pinfunction "2_2") (pintype "passive"))
      (node (ref "C6") (pin "2") (pinfunction "2_2") (pintype "passive"))
      (node (ref "C7") (pin "1") (pinfunction "1_1") (pintype "passive"))
      (node (ref "ETH1") (pin "P$1") (pinfunction "GND_1_P$1") (pintype "bidirectional"))
      (node (ref "ETH1") (pin "P$12") (pinfunction "GND_3_P$12") (pintype "bidirectional"))
      (node (ref "ETH1") (pin "P$2") (pinfunction "GND_2_P$2") (pintype "bidirectional"))
      (node (ref "IC2") (pin "1") (pinfunction "G_1") (pintype "input"))
      (node (ref "IC2") (pin "12") (pinfunction "GND_12") (pintype "power_in"))
      (node (ref "IC2") (pin "13") (pinfunction "G_13") (pintype "input"))
      (node (ref "IC3") (pin "12") (pinfunction "PGND_12") (pintype "bidirectional"))
      (node (ref "IC3") (pin "8") (pinfunction "AGND_8") (pintype "bidirectional"))
      (node (ref "IC4") (pin "7") (pinfunction "GND_7") (pintype "power_in"))
      (node (ref "J102") (pin "P$1") (pinfunction "P$1_P$1") (pintype "bidirectional"))
      (node (ref "J102") (pin "P$2") (pinfunction "P$2_P$2") (pintype "bidirectional"))
      (node (ref "J102") (pin "P$3") (pinfunction "P$3_P$3") (pintype "bidirectional"))
      (node (ref "J104") (pin "P$1") (pinfunction "P$1_P$1") (pintype "bidirectional"))
      (node (ref "J104") (pin "P$2") (pinfunction "P$2_P$2") (pintype "bidirectional"))
      (node (ref "J104") (pin "P$3") (pinfunction "P$3_P$3") (pintype "bidirectional"))
      (node (ref "J124") (pin "P$1") (pinfunction "P$1_P$1") (pintype "bidirectional"))
      (node (ref "J124") (pin "P$2") (pinfunction "P$2_P$2") (pintype "bidirectional"))
      (node (ref "J124") (pin "P$3") (pinfunction "P$3_P$3") (pintype "bidirectional"))
      (node (ref "J151") (pin "P$1") (pinfunction "P$1_P$1") (pintype "bidirectional"))
      (node (ref "J151") (pin "P$2") (pinfunction "P$2_P$2") (pintype "bidirectional"))
      (node (ref "J151") (pin "P$3") (pinfunction "P$3_P$3") (pintype "bidirectional"))
      (node (ref "J153") (pin "P$1") (pinfunction "P$1_P$1") (pintype "bidirectional"))
      (node (ref "J153") (pin "P$2") (pinfunction "P$2_P$2") (pintype "bidirectional"))
      (node (ref "J153") (pin "P$3") (pinfunction "P$3_P$3") (pintype "bidirectional"))
      (node (ref "J7") (pin "P$1") (pinfunction "P$1_P$1") (pintype "bidirectional"))
      (node (ref "L1") (pin "P$20") (pinfunction "GND_1_P$20") (pintype "bidirectional"))
      (node (ref "L1") (pin "P$22") (pinfunction "GND_2_P$22") (pintype "bidirectional"))
      (node (ref "L1") (pin "P$60") (pinfunction "GND_3_P$60") (pintype "bidirectional"))
      (node (ref "L1") (pin "P$62") (pinfunction "GND_4_P$62") (pintype "bidirectional"))
      (node (ref "LED6") (pin "C") (pinfunction "C_C") (pintype "passive"))
      (node (ref "P1") (pin "2") (pinfunction "2_2") (pintype "bidirectional"))
      (node (ref "P2") (pin "P$1") (pinfunction "GND_P$1") (pintype "bidirectional"))
      (node (ref "P3") (pin "P$1") (pinfunction "GND_P$1") (pintype "bidirectional"))
      (node (ref "QG1") (pin "7") (pinfunction "GND_7") (pintype "power_in"))
      (node (ref "R10") (pin "1") (pinfunction "1_1") (pintype "passive"))
      (node (ref "R12") (pin "1") (pinfunction "1_1") (pintype "passive"))
      (node (ref "R14") (pin "1") (pinfunction "1_1") (pintype "passive"))
      (node (ref "R16") (pin "1") (pinfunction "1_1") (pintype "passive"))
      (node (ref "R7") (pin "2") (pinfunction "2_2") (pintype "passive"))
      (node (ref "SV1") (pin "1") (pinfunction "1_1") (pintype "passive"))
      (node (ref "SV1") (pin "2") (pinfunction "2_2") (pintype "passive"))
      (node (ref "SV10") (pin "1") (pinfunction "1_1") (pintype "passive"))
      (node (ref "SV11") (pin "3") (pinfunction "3_3") (pintype "passive"))
      (node (ref "SV11") (pin "4") (pinfunction "4_4") (pintype "passive"))
      (node (ref "SV12") (pin "1") (pinfunction "1_1") (pintype "passive"))
      (node (ref "SV15") (pin "10") (pinfunction "10_10") (pintype "passive"))
      (node (ref "SV15") (pin "12") (pinfunction "12_12") (pintype "passive"))
      (node (ref "SV15") (pin "4") (pinfunction "4_4") (pintype "passive"))
      (node (ref "SV15") (pin "8") (pinfunction "8_8") (pintype "passive"))
      (node (ref "SV16") (pin "1") (pinfunction "1_1") (pintype "passive"))
      (node (ref "SV17") (pin "1") (pinfunction "1_1") (pintype "passive"))
      (node (ref "SV17") (pin "2") (pinfunction "2_2") (pintype "passive"))
      (node (ref "SV18") (pin "1") (pinfunction "1_1") (pintype "passive"))
      (node (ref "SV18") (pin "2") (pinfunction "2_2") (pintype "passive"))
      (node (ref "SV19") (pin "1") (pinfunction "1_1") (pintype "passive"))
      (node (ref "SV2") (pin "13") (pinfunction "13_13") (pintype "passive"))
      (node (ref "SV2") (pin "14") (pinfunction "14_14") (pintype "passive"))
      (node (ref "SV2") (pin "19") (pinfunction "19_19") (pintype "passive"))
      (node (ref "SV2") (pin "20") (pinfunction "20_20") (pintype "passive"))
      (node (ref "SV2") (pin "29") (pinfunction "29_29") (pintype "passive"))
      (node (ref "SV2") (pin "30") (pinfunction "30_30") (pintype "passive"))
      (node (ref "SV2") (pin "33") (pinfunction "33_33") (pintype "passive"))
      (node (ref "SV2") (pin "34") (pinfunction "34_34") (pintype "passive"))
      (node (ref "SV2") (pin "5") (pinfunction "5_5") (pintype "passive"))
      (node (ref "SV2") (pin "6") (pinfunction "6_6") (pintype "passive"))
      (node (ref "SV21") (pin "1") (pinfunction "1_1") (pintype "passive"))
      (node (ref "SV21") (pin "2") (pinfunction "2_2") (pintype "passive"))
      (node (ref "SV22") (pin "1") (pinfunction "1_1") (pintype "passive"))
      (node (ref "SV22") (pin "2") (pinfunction "2_2") (pintype "passive"))
      (node (ref "SV23") (pin "1") (pinfunction "1_1") (pintype "passive"))
      (node (ref "SV23") (pin "2") (pinfunction "2_2") (pintype "passive"))
      (node (ref "SV24") (pin "1") (pinfunction "1_1") (pintype "passive"))
      (node (ref "SV24") (pin "2") (pinfunction "2_2") (pintype "passive"))
      (node (ref "SV25") (pin "1") (pinfunction "1_1") (pintype "passive"))
      (node (ref "SV25") (pin "2") (pinfunction "2_2") (pintype "passive"))
      (node (ref "SV26") (pin "1") (pinfunction "1_1") (pintype "passive"))
      (node (ref "SV26") (pin "2") (pinfunction "2_2") (pintype "passive"))
      (node (ref "SV27") (pin "1") (pinfunction "1_1") (pintype "passive"))
      (node (ref "SV27") (pin "2") (pinfunction "2_2") (pintype "passive"))
      (node (ref "SV28") (pin "2") (pinfunction "2_2") (pintype "passive"))
      (node (ref "SV3") (pin "5") (pinfunction "5_5") (pintype "passive"))
      (node (ref "SV3") (pin "6") (pinfunction "6_6") (pintype "passive"))
      (node (ref "SV30") (pin "1") (pinfunction "1_1") (pintype "passive"))
      (node (ref "SV4") (pin "1") (pinfunction "1_1") (pintype "passive"))
      (node (ref "SV4") (pin "2") (pinfunction "2_2") (pintype "passive"))
      (node (ref "SV45") (pin "2") (pinfunction "2_2") (pintype "passive"))
      (node (ref "SV45") (pin "4") (pinfunction "4_4") (pintype "passive"))
      (node (ref "SV45") (pin "6") (pinfunction "6_6") (pintype "passive"))
      (node (ref "SV5") (pin "10") (pinfunction "10_10") (pintype "passive"))
      (node (ref "SV5") (pin "25") (pinfunction "25_25") (pintype "passive"))
      (node (ref "SV5") (pin "26") (pinfunction "26_26") (pintype "passive"))
      (node (ref "SV5") (pin "39") (pinfunction "39_39") (pintype "passive"))
      (node (ref "SV5") (pin "40") (pinfunction "40_40") (pintype "passive"))
      (node (ref "SV5") (pin "9") (pinfunction "9_9") (pintype "passive"))
      (node (ref "SV6") (pin "5") (pinfunction "5_5") (pintype "passive"))
      (node (ref "SV68") (pin "1") (pinfunction "1_1") (pintype "passive"))
      (node (ref "SV68") (pin "2") (pinfunction "2_2") (pintype "passive"))
      (node (ref "SV68") (pin "3") (pinfunction "3_3") (pintype "passive"))
      (node (ref "SV69") (pin "1") (pinfunction "1_1") (pintype "passive"))
      (node (ref "SV69") (pin "2") (pinfunction "2_2") (pintype "passive"))
      (node (ref "SV69") (pin "3") (pinfunction "3_3") (pintype "passive"))
      (node (ref "SV70") (pin "1") (pinfunction "1_1") (pintype "passive"))
      (node (ref "SV70") (pin "2") (pinfunction "2_2") (pintype "passive"))
      (node (ref "SV70") (pin "3") (pinfunction "3_3") (pintype "passive"))
      (node (ref "SV71") (pin "1") (pinfunction "1_1") (pintype "passive"))
      (node (ref "SV71") (pin "2") (pinfunction "2_2") (pintype "passive"))
      (node (ref "SV71") (pin "3") (pinfunction "3_3") (pintype "passive"))
      (node (ref "SV75") (pin "2") (pinfunction "2_2") (pintype "passive"))
      (node (ref "SV75") (pin "4") (pinfunction "4_4") (pintype "passive"))
      (node (ref "SV75") (pin "6") (pinfunction "6_6") (pintype "passive"))
      (node (ref "SV8") (pin "1") (pinfunction "1_1") (pintype "passive"))
      (node (ref "SV9") (pin "1") (pinfunction "1_1") (pintype "passive"))
      (node (ref "U$1") (pin "2") (pinfunction "P2_GND_2") (pintype "bidirectional"))
      (node (ref "U10") (pin "3") (pinfunction "GND_3") (pintype "bidirectional"))
      (node (ref "U11") (pin "12") (pinfunction "VSS2_12") (pintype "bidirectional"))
      (node (ref "U11") (pin "2") (pinfunction "VSS_2") (pintype "bidirectional"))
      (node (ref "U11") (pin "23") (pinfunction "VSSA/VREFLO_23") (pintype "bidirectional"))
      (node (ref "U11") (pin "3") (pinfunction "/VREGENZ_3") (pintype "bidirectional"))
      (node (ref "U12") (pin "P$3") (pinfunction "GND_P$3") (pintype "bidirectional"))
      (node (ref "U12") (pin "P$6") (pinfunction "GND1_P$6") (pintype "bidirectional"))
      (node (ref "U15") (pin "P$11") (pinfunction "P11_GND_P$11") (pintype "bidirectional"))
      (node (ref "U15") (pin "P$2") (pinfunction "P2_GND_P$2") (pintype "bidirectional"))
      (node (ref "U2") (pin "15") (pinfunction "GND_15") (pintype "bidirectional"))
      (node (ref "U3") (pin "4") (pinfunction "GND_4") (pintype "bidirectional"))
      (node (ref "U4") (pin "15") (pinfunction "GND_15") (pintype "bidirectional"))
      (node (ref "U5") (pin "P$4") (pinfunction "V-_P$4") (pintype "bidirectional"))
      (node (ref "U6") (pin "18") (pinfunction "GND2_18") (pintype "power_in"))
      (node (ref "U6") (pin "21") (pinfunction "GND3_21") (pintype "power_in"))
      (node (ref "U6") (pin "25") (pinfunction "AGND_25") (pintype "power_in"))
      (node (ref "U6") (pin "26") (pinfunction "TEST_26") (pintype "input"))
      (node (ref "U6") (pin "7") (pinfunction "GND1_7") (pintype "power_in"))
      (node (ref "U7") (pin "3") (pinfunction "GND_3") (pintype "bidirectional"))
      (node (ref "U8") (pin "3") (pinfunction "GND_3") (pintype "bidirectional"))
      (node (ref "U9") (pin "3") (pinfunction "GND_3") (pintype "bidirectional"))
      (node (ref "USB_PWR1") (pin "K") (pinfunction "C_K") (pintype "passive"))
      (node (ref "X1") (pin "5") (pinfunction "5_5") (pintype "passive"))
      (node (ref "X1") (pin "G1") (pinfunction "G1_G1") (pintype "passive"))
      (node (ref "X1") (pin "G2") (pinfunction "G2_G2") (pintype "passive"))
      (node (ref "X2") (pin "GND") (pinfunction "GND_GND") (pintype "bidirectional"))
    )
    (net (code "50") (name "GPIO0") (class "Default")
      (node (ref "J122") (pin "P$1") (pinfunction "P$1_P$1") (pintype "bidirectional"))
      (node (ref "J122") (pin "P$2") (pinfunction "P$2_P$2") (pintype "bidirectional"))
      (node (ref "J122") (pin "P$3") (pinfunction "P$3_P$3") (pintype "bidirectional"))
      (node (ref "L1") (pin "P$40") (pinfunction "GPIO0/EPWM1A_P$40") (pintype "bidirectional"))
      (node (ref "SV25") (pin "9") (pinfunction "9_9") (pintype "passive"))
    )
    (net (code "51") (name "GPIO1") (class "Default")
      (node (ref "J121") (pin "P$1") (pinfunction "P$1_P$1") (pintype "bidirectional"))
      (node (ref "J121") (pin "P$2") (pinfunction "P$2_P$2") (pintype "bidirectional"))
      (node (ref "J121") (pin "P$3") (pinfunction "P$3_P$3") (pintype "bidirectional"))
      (node (ref "L1") (pin "P$39") (pinfunction "GPIO1/EPWM1B_P$39") (pintype "bidirectional"))
      (node (ref "SV25") (pin "7") (pinfunction "7_7") (pintype "passive"))
    )
    (net (code "52") (name "GPIO2") (class "Default")
      (node (ref "J120") (pin "P$1") (pinfunction "P$1_P$1") (pintype "bidirectional"))
      (node (ref "J120") (pin "P$2") (pinfunction "P$2_P$2") (pintype "bidirectional"))
      (node (ref "J120") (pin "P$3") (pinfunction "P$3_P$3") (pintype "bidirectional"))
      (node (ref "L1") (pin "P$38") (pinfunction "GPIO2/EPWM2A_P$38") (pintype "bidirectional"))
      (node (ref "SV25") (pin "5") (pinfunction "5_5") (pintype "passive"))
    )
    (net (code "53") (name "GPIO3") (class "Default")
      (node (ref "J119") (pin "P$1") (pinfunction "P$1_P$1") (pintype "bidirectional"))
      (node (ref "J119") (pin "P$2") (pinfunction "P$2_P$2") (pintype "bidirectional"))
      (node (ref "J119") (pin "P$3") (pinfunction "P$3_P$3") (pintype "bidirectional"))
      (node (ref "L1") (pin "P$37") (pinfunction "GPIO3/EPWM2B_P$37") (pintype "bidirectional"))
      (node (ref "SV25") (pin "10") (pinfunction "10_10") (pintype "passive"))
    )
    (net (code "54") (name "GPIO4") (class "Default")
      (node (ref "J118") (pin "P$1") (pinfunction "P$1_P$1") (pintype "bidirectional"))
      (node (ref "J118") (pin "P$2") (pinfunction "P$2_P$2") (pintype "bidirectional"))
      (node (ref "J118") (pin "P$3") (pinfunction "P$3_P$3") (pintype "bidirectional"))
      (node (ref "L1") (pin "P$36") (pinfunction "GPIO4/EPWM3A_P$36") (pintype "bidirectional"))
      (node (ref "SV25") (pin "8") (pinfunction "8_8") (pintype "passive"))
    )
    (net (code "55") (name "GPIO5") (class "Default")
      (node (ref "J117") (pin "P$1") (pinfunction "P$1_P$1") (pintype "bidirectional"))
      (node (ref "J117") (pin "P$2") (pinfunction "P$2_P$2") (pintype "bidirectional"))
      (node (ref "J117") (pin "P$3") (pinfunction "P$3_P$3") (pintype "bidirectional"))
      (node (ref "L1") (pin "P$35") (pinfunction "GPIO5/EPWM3B_P$35") (pintype "bidirectional"))
      (node (ref "SV25") (pin "6") (pinfunction "6_6") (pintype "passive"))
    )
    (net (code "56") (name "GPIO6") (class "Default")
      (node (ref "IC2") (pin "17") (pinfunction "B2_17") (pintype "bidirectional"))
      (node (ref "J133") (pin "P$1") (pinfunction "P$1_P$1") (pintype "bidirectional"))
      (node (ref "J133") (pin "P$2") (pinfunction "P$2_P$2") (pintype "bidirectional"))
      (node (ref "J133") (pin "P$3") (pinfunction "P$3_P$3") (pintype "bidirectional"))
      (node (ref "L1") (pin "P$80") (pinfunction "GPIO6/EPWM4A_P$80") (pintype "bidirectional"))
    )
    (net (code "57") (name "GPIO7") (class "Default")
      (node (ref "IC2") (pin "15") (pinfunction "B1_15") (pintype "bidirectional"))
      (node (ref "J134") (pin "P$1") (pinfunction "P$1_P$1") (pintype "bidirectional"))
      (node (ref "J134") (pin "P$2") (pinfunction "P$2_P$2") (pintype "bidirectional"))
      (node (ref "J134") (pin "P$3") (pinfunction "P$3_P$3") (pintype "bidirectional"))
      (node (ref "L1") (pin "P$79") (pinfunction "GPIO7/EPWM4B_P$79") (pintype "bidirectional"))
    )
    (net (code "58") (name "GPIO8") (class "Default")
      (node (ref "J135") (pin "P$1") (pinfunction "P$1_P$1") (pintype "bidirectional"))
      (node (ref "J135") (pin "P$2") (pinfunction "P$2_P$2") (pintype "bidirectional"))
      (node (ref "J135") (pin "P$3") (pinfunction "P$3_P$3") (pintype "bidirectional"))
      (node (ref "L1") (pin "P$78") (pinfunction "GPIO8/EPWM5A_P$78") (pintype "bidirectional"))
      (node (ref "SV26") (pin "9") (pinfunction "9_9") (pintype "passive"))
    )
    (net (code "59") (name "GPIO9") (class "Default")
      (node (ref "J136") (pin "P$1") (pinfunction "P$1_P$1") (pintype "bidirectional"))
      (node (ref "J136") (pin "P$2") (pinfunction "P$2_P$2") (pintype "bidirectional"))
      (node (ref "J136") (pin "P$3") (pinfunction "P$3_P$3") (pintype "bidirectional"))
      (node (ref "L1") (pin "P$77") (pinfunction "GPIO9/EPWM5B_P$77") (pintype "bidirectional"))
      (node (ref "SV26") (pin "7") (pinfunction "7_7") (pintype "passive"))
    )
    (net (code "60") (name "GPIO10") (class "Default")
      (node (ref "J137") (pin "P$1") (pinfunction "P$1_P$1") (pintype "bidirectional"))
      (node (ref "J137") (pin "P$2") (pinfunction "P$2_P$2") (pintype "bidirectional"))
      (node (ref "J137") (pin "P$3") (pinfunction "P$3_P$3") (pintype "bidirectional"))
      (node (ref "L1") (pin "P$76") (pinfunction "GPIO10/EPWM6A_P$76") (pintype "bidirectional"))
      (node (ref "SV26") (pin "5") (pinfunction "5_5") (pintype "passive"))
    )
    (net (code "61") (name "GPIO11") (class "Default")
      (node (ref "J138") (pin "P$1") (pinfunction "P$1_P$1") (pintype "bidirectional"))
      (node (ref "J138") (pin "P$2") (pinfunction "P$2_P$2") (pintype "bidirectional"))
      (node (ref "J138") (pin "P$3") (pinfunction "P$3_P$3") (pintype "bidirectional"))
      (node (ref "L1") (pin "P$75") (pinfunction "GPIO11/EPWM6B_P$75") (pintype "bidirectional"))
    )
    (net (code "62") (name "GPIO14") (class "Default")
      (node (ref "J139") (pin "P$1") (pinfunction "P$1_P$1") (pintype "bidirectional"))
      (node (ref "J139") (pin "P$2") (pinfunction "P$2_P$2") (pintype "bidirectional"))
      (node (ref "J139") (pin "P$3") (pinfunction "P$3_P$3") (pintype "bidirectional"))
      (node (ref "L1") (pin "P$74") (pinfunction "GPIO14_P$74") (pintype "bidirectional"))
      (node (ref "SV4") (pin "7") (pinfunction "7_7") (pintype "passive"))
      (node (ref "SV4") (pin "9") (pinfunction "9_9") (pintype "passive"))
    )
    (net (code "63") (name "GPIO15") (class "Default")
      (node (ref "J140") (pin "P$1") (pinfunction "P$1_P$1") (pintype "bidirectional"))
      (node (ref "J140") (pin "P$2") (pinfunction "P$2_P$2") (pintype "bidirectional"))
      (node (ref "J140") (pin "P$3") (pinfunction "P$3_P$3") (pintype "bidirectional"))
      (node (ref "L1") (pin "P$73") (pinfunction "GPIO15_P$73") (pintype "bidirectional"))
      (node (ref "SV4") (pin "11") (pinfunction "11_11") (pintype "passive"))
      (node (ref "SV4") (pin "13") (pinfunction "13_13") (pintype "passive"))
    )
    (net (code "64") (name "GPIO16") (class "Default")
      (node (ref "J115") (pin "P$1") (pinfunction "P$1_P$1") (pintype "bidirectional"))
      (node (ref "J115") (pin "P$2") (pinfunction "P$2_P$2") (pintype "bidirectional"))
      (node (ref "J115") (pin "P$3") (pinfunction "P$3_P$3") (pintype "bidirectional"))
      (node (ref "L1") (pin "P$33") (pinfunction "GPIO16_P$33") (pintype "bidirectional"))
      (node (ref "SV41") (pin "1") (pinfunction "1_1") (pintype "passive"))
    )
    (net (code "65") (name "GPIO18") (class "Default")
      (node (ref "J16") (pin "P$1") (pinfunction "P$1_P$1") (pintype "bidirectional"))
      (node (ref "J16") (pin "P$2") (pinfunction "P$2_P$2") (pintype "bidirectional"))
      (node (ref "J16") (pin "P$3") (pinfunction "P$3_P$3") (pintype "bidirectional"))
      (node (ref "L1") (pin "P$4") (pinfunction "GPIO18/SCITXDB_P$4") (pintype "bidirectional"))
      (node (ref "U3") (pin "6") (pinfunction "SCK_6") (pintype "bidirectional"))
    )
    (net (code "66") (name "GPIO19") (class "Default")
      (node (ref "J15") (pin "P$1") (pinfunction "P$1_P$1") (pintype "bidirectional"))
      (node (ref "J15") (pin "P$2") (pinfunction "P$2_P$2") (pintype "bidirectional"))
      (node (ref "J15") (pin "P$3") (pinfunction "P$3_P$3") (pintype "bidirectional"))
      (node (ref "L1") (pin "P$3") (pinfunction "GPIO19/SCIRXDB_P$3") (pintype "bidirectional"))
      (node (ref "U3") (pin "1") (pinfunction "~{CS}_1") (pintype "bidirectional"))
    )
    (net (code "67") (name "GPIO22") (class "Default")
      (node (ref "J20") (pin "P$1") (pinfunction "P$1_P$1") (pintype "bidirectional"))
      (node (ref "J20") (pin "P$2") (pinfunction "P$2_P$2") (pintype "bidirectional"))
      (node (ref "J20") (pin "P$3") (pinfunction "P$3_P$3") (pintype "bidirectional"))
      (node (ref "L1") (pin "P$8") (pinfunction "GPIO22_P$8") (pintype "bidirectional"))
      (node (ref "SV41") (pin "3") (pinfunction "3_3") (pintype "passive"))
    )
    (net (code "68") (name "GPIO24") (class "Default")
      (node (ref "J116") (pin "P$1") (pinfunction "P$1_P$1") (pintype "bidirectional"))
      (node (ref "J116") (pin "P$2") (pinfunction "P$2_P$2") (pintype "bidirectional"))
      (node (ref "J116") (pin "P$3") (pinfunction "P$3_P$3") (pintype "bidirectional"))
      (node (ref "J9") (pin "P$1") (pinfunction "P$1_P$1") (pintype "bidirectional"))
      (node (ref "J9") (pin "P$2") (pinfunction "P$2_P$2") (pintype "bidirectional"))
      (node (ref "L1") (pin "P$34") (pinfunction "GPIO24_P$34") (pintype "bidirectional"))
    )
    (net (code "69") (name "GPIO25") (class "Default")
      (node (ref "IC2") (pin "6") (pinfunction "B3_6") (pintype "bidirectional"))
      (node (ref "J162") (pin "P$1") (pinfunction "P$1_P$1") (pintype "bidirectional"))
      (node (ref "J162") (pin "P$2") (pinfunction "P$2_P$2") (pintype "bidirectional"))
      (node (ref "J162") (pin "P$3") (pinfunction "P$3_P$3") (pintype "bidirectional"))
      (node (ref "L1") (pin "P$51") (pinfunction "GPIO25_P$51") (pintype "bidirectional"))
    )
    (net (code "70") (name "GPIO26") (class "Default")
      (node (ref "IC2") (pin "4") (pinfunction "B2_4") (pintype "bidirectional"))
      (node (ref "J160") (pin "P$1") (pinfunction "P$1_P$1") (pintype "bidirectional"))
      (node (ref "J160") (pin "P$2") (pinfunction "P$2_P$2") (pintype "bidirectional"))
      (node (ref "J160") (pin "P$3") (pinfunction "P$3_P$3") (pintype "bidirectional"))
      (node (ref "L1") (pin "P$53") (pinfunction "GPIO26_P$53") (pintype "bidirectional"))
    )
    (net (code "71") (name "GPIO27") (class "Default")
      (node (ref "J11") (pin "P$1") (pinfunction "P$1_P$1") (pintype "bidirectional"))
      (node (ref "J11") (pin "P$2") (pinfunction "P$2_P$2") (pintype "bidirectional"))
      (node (ref "J161") (pin "P$1") (pinfunction "P$1_P$1") (pintype "bidirectional"))
      (node (ref "J161") (pin "P$2") (pinfunction "P$2_P$2") (pintype "bidirectional"))
      (node (ref "J161") (pin "P$3") (pinfunction "P$3_P$3") (pintype "bidirectional"))
      (node (ref "L1") (pin "P$52") (pinfunction "GPIO27_P$52") (pintype "bidirectional"))
    )
    (net (code "72") (name "GPIO29") (class "Default")
      (node (ref "J29") (pin "P$1") (pinfunction "P$1_P$1") (pintype "bidirectional"))
      (node (ref "J29") (pin "P$2") (pinfunction "P$2_P$2") (pintype "bidirectional"))
      (node (ref "J29") (pin "P$3") (pinfunction "P$3_P$3") (pintype "bidirectional"))
      (node (ref "J37") (pin "P$2") (pinfunction "P$2_P$2") (pintype "bidirectional"))
      (node (ref "L1") (pin "P$11") (pinfunction "GPIO29_P$11") (pintype "bidirectional"))
    )
    (net (code "73") (name "GPIO32") (class "Default")
      (node (ref "J14") (pin "P$1") (pinfunction "P$1_P$1") (pintype "bidirectional"))
      (node (ref "J14") (pin "P$2") (pinfunction "P$2_P$2") (pintype "bidirectional"))
      (node (ref "J14") (pin "P$3") (pinfunction "P$3_P$3") (pintype "bidirectional"))
      (node (ref "L1") (pin "P$2") (pinfunction "GPIO32_P$2") (pintype "bidirectional"))
      (node (ref "SV22") (pin "3") (pinfunction "3_3") (pintype "passive"))
    )
    (net (code "74") (name "GPIO40") (class "Default")
      (node (ref "J163") (pin "P$1") (pinfunction "P$1_P$1") (pintype "bidirectional"))
      (node (ref "J163") (pin "P$2") (pinfunction "P$2_P$2") (pintype "bidirectional"))
      (node (ref "J163") (pin "P$3") (pinfunction "P$3_P$3") (pintype "bidirectional"))
      (node (ref "L1") (pin "P$50") (pinfunction "GPIO40/SDAB_P$50") (pintype "bidirectional"))
      (node (ref "R17") (pin "1") (pinfunction "1_1") (pintype "passive"))
      (node (ref "SV10") (pin "3") (pinfunction "3_3") (pintype "passive"))
      (node (ref "SV30") (pin "3") (pinfunction "3_3") (pintype "passive"))
    )
    (net (code "75") (name "GPIO41") (class "Default")
      (node (ref "J164") (pin "P$1") (pinfunction "P$1_P$1") (pintype "bidirectional"))
      (node (ref "J164") (pin "P$2") (pinfunction "P$2_P$2") (pintype "bidirectional"))
      (node (ref "J164") (pin "P$3") (pinfunction "P$3_P$3") (pintype "bidirectional"))
      (node (ref "L1") (pin "P$49") (pinfunction "GPIO41/SCLB_P$49") (pintype "bidirectional"))
      (node (ref "R18") (pin "1") (pinfunction "1_1") (pintype "passive"))
      (node (ref "SV10") (pin "5") (pinfunction "5_5") (pintype "passive"))
      (node (ref "SV30") (pin "5") (pinfunction "5_5") (pintype "passive"))
    )
    (net (code "76") (name "GPIO52") (class "Default")
      (node (ref "J165") (pin "P$1") (pinfunction "P$1_P$1") (pintype "bidirectional"))
      (node (ref "J165") (pin "P$2") (pinfunction "P$2_P$2") (pintype "bidirectional"))
      (node (ref "J165") (pin "P$3") (pinfunction "P$3_P$3") (pintype "bidirectional"))
      (node (ref "L1") (pin "P$48") (pinfunction "GPIO52_P$48") (pintype "bidirectional"))
      (node (ref "SV22") (pin "5") (pinfunction "5_5") (pintype "passive"))
    )
    (net (code "77") (name "GPIO56") (class "Default")
      (node (ref "J169") (pin "P$1") (pinfunction "P$1_P$1") (pintype "bidirectional"))
      (node (ref "J169") (pin "P$2") (pinfunction "P$2_P$2") (pintype "bidirectional"))
      (node (ref "J169") (pin "P$3") (pinfunction "P$3_P$3") (pintype "bidirectional"))
      (node (ref "L1") (pin "P$44") (pinfunction "GPIO56/SCITXDC_P$44") (pintype "bidirectional"))
      (node (ref "SV27") (pin "8") (pinfunction "8_8") (pintype "passive"))
    )
    (net (code "78") (name "GPIO58") (class "Default")
      (node (ref "J33") (pin "P$1") (pinfunction "P$1_P$1") (pintype "bidirectional"))
      (node (ref "J33") (pin "P$2") (pinfunction "P$2_P$2") (pintype "bidirectional"))
      (node (ref "J33") (pin "P$3") (pinfunction "P$3_P$3") (pintype "bidirectional"))
      (node (ref "L1") (pin "P$15") (pinfunction "GPIO58/SPISIMOA_P$15") (pintype "bidirectional"))
      (node (ref "U3") (pin "5") (pinfunction "SI_5") (pintype "bidirectional"))
    )
    (net (code "79") (name "GPIO59") (class "Default")
      (node (ref "J32") (pin "P$1") (pinfunction "P$1_P$1") (pintype "bidirectional"))
      (node (ref "J32") (pin "P$2") (pinfunction "P$2_P$2") (pintype "bidirectional"))
      (node (ref "J32") (pin "P$3") (pinfunction "P$3_P$3") (pintype "bidirectional"))
      (node (ref "L1") (pin "P$14") (pinfunction "GPIO59/SPISOMIA_P$14") (pintype "bidirectional"))
      (node (ref "U3") (pin "2") (pinfunction "SO_2") (pintype "bidirectional"))
    )
    (net (code "80") (name "GPIO60") (class "Default")
      (node (ref "J19") (pin "P$1") (pinfunction "P$1_P$1") (pintype "bidirectional"))
      (node (ref "J19") (pin "P$2") (pinfunction "P$2_P$2") (pintype "bidirectional"))
      (node (ref "J19") (pin "P$3") (pinfunction "P$3_P$3") (pintype "bidirectional"))
      (node (ref "L1") (pin "P$7") (pinfunction "GPIO60/SPICLKA_P$7") (pintype "bidirectional"))
      (node (ref "SV22") (pin "7") (pinfunction "7_7") (pintype "passive"))
    )
    (net (code "81") (name "GPIO61") (class "Default")
      (node (ref "J101") (pin "P$1") (pinfunction "P$1_P$1") (pintype "bidirectional"))
      (node (ref "J101") (pin "P$2") (pinfunction "P$2_P$2") (pintype "bidirectional"))
      (node (ref "J101") (pin "P$3") (pinfunction "P$3_P$3") (pintype "bidirectional"))
      (node (ref "L1") (pin "P$19") (pinfunction "GPIO61_P$19") (pintype "bidirectional"))
      (node (ref "SV22") (pin "9") (pinfunction "9_9") (pintype "passive"))
    )
    (net (code "82") (name "GPIO63") (class "Default")
      (node (ref "IC2") (pin "19") (pinfunction "B3_19") (pintype "bidirectional"))
      (node (ref "J158") (pin "P$1") (pinfunction "P$1_P$1") (pintype "bidirectional"))
      (node (ref "J158") (pin "P$2") (pinfunction "P$2_P$2") (pintype "bidirectional"))
      (node (ref "J158") (pin "P$3") (pinfunction "P$3_P$3") (pintype "bidirectional"))
      (node (ref "J204") (pin "P$1") (pinfunction "P$1_P$1") (pintype "bidirectional"))
      (node (ref "J204") (pin "P$2") (pinfunction "P$2_P$2") (pintype "bidirectional"))
      (node (ref "J36") (pin "P$2") (pinfunction "P$2_P$2") (pintype "bidirectional"))
      (node (ref "L1") (pin "P$55") (pinfunction "GPIO63/SPISIMOB_P$55") (pintype "bidirectional"))
    )
    (net (code "83") (name "GPIO64") (class "Default")
      (node (ref "IC2") (pin "21") (pinfunction "B4_21") (pintype "bidirectional"))
      (node (ref "J159") (pin "P$1") (pinfunction "P$1_P$1") (pintype "bidirectional"))
      (node (ref "J159") (pin "P$2") (pinfunction "P$2_P$2") (pintype "bidirectional"))
      (node (ref "J159") (pin "P$3") (pinfunction "P$3_P$3") (pintype "bidirectional"))
      (node (ref "J205") (pin "P$1") (pinfunction "P$1_P$1") (pintype "bidirectional"))
      (node (ref "J205") (pin "P$2") (pinfunction "P$2_P$2") (pintype "bidirectional"))
      (node (ref "J35") (pin "P$2") (pinfunction "P$2_P$2") (pintype "bidirectional"))
      (node (ref "L1") (pin "P$54") (pinfunction "GPIO64/SPISOMIB_P$54") (pintype "bidirectional"))
    )
    (net (code "84") (name "GPIO65") (class "Default")
      (node (ref "IC2") (pin "23") (pinfunction "B5_23") (pintype "bidirectional"))
      (node (ref "J166") (pin "P$1") (pinfunction "P$1_P$1") (pintype "bidirectional"))
      (node (ref "J166") (pin "P$2") (pinfunction "P$2_P$2") (pintype "bidirectional"))
      (node (ref "J166") (pin "P$3") (pinfunction "P$3_P$3") (pintype "bidirectional"))
      (node (ref "J206") (pin "P$1") (pinfunction "P$1_P$1") (pintype "bidirectional"))
      (node (ref "J206") (pin "P$2") (pinfunction "P$2_P$2") (pintype "bidirectional"))
      (node (ref "J38") (pin "P$2") (pinfunction "P$2_P$2") (pintype "bidirectional"))
      (node (ref "L1") (pin "P$47") (pinfunction "GPIO65/SPICLKB_P$47") (pintype "bidirectional"))
    )
    (net (code "85") (name "GPIO66") (class "Default")
      (node (ref "J154") (pin "P$1") (pinfunction "P$1_P$1") (pintype "bidirectional"))
      (node (ref "J154") (pin "P$2") (pinfunction "P$2_P$2") (pintype "bidirectional"))
      (node (ref "J154") (pin "P$3") (pinfunction "P$3_P$3") (pintype "bidirectional"))
      (node (ref "J207") (pin "P$1") (pinfunction "P$1_P$1") (pintype "bidirectional"))
      (node (ref "J207") (pin "P$2") (pinfunction "P$2_P$2") (pintype "bidirectional"))
      (node (ref "L1") (pin "P$59") (pinfunction "GPIO66_P$59") (pintype "bidirectional"))
    )
    (net (code "86") (name "GPIO67") (class "Default")
      (node (ref "J17") (pin "P$1") (pinfunction "P$1_P$1") (pintype "bidirectional"))
      (node (ref "J17") (pin "P$2") (pinfunction "P$2_P$2") (pintype "bidirectional"))
      (node (ref "J17") (pin "P$3") (pinfunction "P$3_P$3") (pintype "bidirectional"))
      (node (ref "L1") (pin "P$5") (pinfunction "GPIO67_P$5") (pintype "bidirectional"))
      (node (ref "SV22") (pin "11") (pinfunction "11_11") (pintype "passive"))
    )
    (net (code "87") (name "GPIO94") (class "Default")
      (node (ref "J167") (pin "P$1") (pinfunction "P$1_P$1") (pintype "bidirectional"))
      (node (ref "J167") (pin "P$2") (pinfunction "P$2_P$2") (pintype "bidirectional"))
      (node (ref "J167") (pin "P$3") (pinfunction "P$3_P$3") (pintype "bidirectional"))
      (node (ref "L1") (pin "P$46") (pinfunction "GPIO94_P$46") (pintype "bidirectional"))
      (node (ref "SV41") (pin "5") (pinfunction "5_5") (pintype "passive"))
    )
    (net (code "88") (name "GPIO95") (class "Default")
      (node (ref "J176") (pin "P$1") (pinfunction "P$1_P$1") (pintype "bidirectional"))
      (node (ref "J176") (pin "P$2") (pinfunction "P$2_P$2") (pintype "bidirectional"))
      (node (ref "J176") (pin "P$3") (pinfunction "P$3_P$3") (pintype "bidirectional"))
      (node (ref "L1") (pin "P$42") (pinfunction "GPIO95_P$42") (pintype "bidirectional"))
      (node (ref "SV41") (pin "7") (pinfunction "7_7") (pintype "passive"))
    )
    (net (code "89") (name "GPIO97") (class "Default")
      (node (ref "J168") (pin "P$1") (pinfunction "P$1_P$1") (pintype "bidirectional"))
      (node (ref "J168") (pin "P$2") (pinfunction "P$2_P$2") (pintype "bidirectional"))
      (node (ref "J168") (pin "P$3") (pinfunction "P$3_P$3") (pintype "bidirectional"))
      (node (ref "L1") (pin "P$45") (pinfunction "GPIO97_P$45") (pintype "bidirectional"))
      (node (ref "SV41") (pin "9") (pinfunction "9_9") (pintype "passive"))
    )
    (net (code "90") (name "GPIO104") (class "Default")
      (node (ref "J28") (pin "P$1") (pinfunction "P$1_P$1") (pintype "bidirectional"))
      (node (ref "J28") (pin "P$2") (pinfunction "P$2_P$2") (pintype "bidirectional"))
      (node (ref "J28") (pin "P$3") (pinfunction "P$3_P$3") (pintype "bidirectional"))
      (node (ref "L1") (pin "P$10") (pinfunction "GPIO104/SDAA_P$10") (pintype "bidirectional"))
      (node (ref "SV4") (pin "3") (pinfunction "3_3") (pintype "passive"))
    )
    (net (code "91") (name "GPIO105") (class "Default")
      (node (ref "J21") (pin "P$1") (pinfunction "P$1_P$1") (pintype "bidirectional"))
      (node (ref "J21") (pin "P$2") (pinfunction "P$2_P$2") (pintype "bidirectional"))
      (node (ref "J21") (pin "P$3") (pinfunction "P$3_P$3") (pintype "bidirectional"))
      (node (ref "L1") (pin "P$9") (pinfunction "GPIO105/SCLA_P$9") (pintype "bidirectional"))
      (node (ref "SV4") (pin "5") (pinfunction "5_5") (pintype "passive"))
    )
    (net (code "92") (name "GPIO111") (class "Default")
      (node (ref "J18") (pin "P$1") (pinfunction "P$1_P$1") (pintype "bidirectional"))
      (node (ref "J18") (pin "P$2") (pinfunction "P$2_P$2") (pintype "bidirectional"))
      (node (ref "J18") (pin "P$3") (pinfunction "P$3_P$3") (pintype "bidirectional"))
      (node (ref "L1") (pin "P$6") (pinfunction "GPIO111_P$6") (pintype "bidirectional"))
      (node (ref "SV41") (pin "11") (pinfunction "11_11") (pintype "passive"))
    )
    (net (code "93") (name "GPIO122") (class "Default")
      (node (ref "J66") (pin "P$1") (pinfunction "P$1_P$1") (pintype "bidirectional"))
      (node (ref "J66") (pin "P$2") (pinfunction "P$2_P$2") (pintype "bidirectional"))
      (node (ref "J99") (pin "P$1") (pinfunction "P$1_P$1") (pintype "bidirectional"))
      (node (ref "J99") (pin "P$2") (pinfunction "P$2_P$2") (pintype "bidirectional"))
      (node (ref "J99") (pin "P$3") (pinfunction "P$3_P$3") (pintype "bidirectional"))
      (node (ref "L1") (pin "P$17") (pinfunction "GPIO122_P$17") (pintype "bidirectional"))
    )
    (net (code "94") (name "GPIO123") (class "Default")
      (node (ref "J100") (pin "P$1") (pinfunction "P$1_P$1") (pintype "bidirectional"))
      (node (ref "J100") (pin "P$2") (pinfunction "P$2_P$2") (pintype "bidirectional"))
      (node (ref "J100") (pin "P$3") (pinfunction "P$3_P$3") (pintype "bidirectional"))
      (node (ref "J67") (pin "P$1") (pinfunction "P$1_P$1") (pintype "bidirectional"))
      (node (ref "J67") (pin "P$2") (pinfunction "P$2_P$2") (pintype "bidirectional"))
      (node (ref "L1") (pin "P$18") (pinfunction "GPIO123_P$18") (pintype "bidirectional"))
    )
    (net (code "95") (name "GPIO124") (class "Default")
      (node (ref "J31") (pin "P$1") (pinfunction "P$1_P$1") (pintype "bidirectional"))
      (node (ref "J31") (pin "P$2") (pinfunction "P$2_P$2") (pintype "bidirectional"))
      (node (ref "J31") (pin "P$3") (pinfunction "P$3_P$3") (pintype "bidirectional"))
      (node (ref "J68") (pin "P$1") (pinfunction "P$1_P$1") (pintype "bidirectional"))
      (node (ref "J68") (pin "P$2") (pinfunction "P$2_P$2") (pintype "bidirectional"))
      (node (ref "L1") (pin "P$13") (pinfunction "GPIO124_P$13") (pintype "bidirectional"))
    )
    (net (code "96") (name "GPIO125") (class "Default")
      (node (ref "J30") (pin "P$1") (pinfunction "P$1_P$1") (pintype "bidirectional"))
      (node (ref "J30") (pin "P$2") (pinfunction "P$2_P$2") (pintype "bidirectional"))
      (node (ref "J30") (pin "P$3") (pinfunction "P$3_P$3") (pintype "bidirectional"))
      (node (ref "J69") (pin "P$1") (pinfunction "P$1_P$1") (pintype "bidirectional"))
      (node (ref "J69") (pin "P$2") (pinfunction "P$2_P$2") (pintype "bidirectional"))
      (node (ref "L1") (pin "P$12") (pinfunction "GPIO125_P$12") (pintype "bidirectional"))
    )
    (net (code "97") (name "GPIO130") (class "Default")
      (node (ref "IC2") (pin "10") (pinfunction "B5_10") (pintype "bidirectional"))
      (node (ref "J156") (pin "P$1") (pinfunction "P$1_P$1") (pintype "bidirectional"))
      (node (ref "J156") (pin "P$2") (pinfunction "P$2_P$2") (pintype "bidirectional"))
      (node (ref "J156") (pin "P$3") (pinfunction "P$3_P$3") (pintype "bidirectional"))
      (node (ref "L1") (pin "P$57") (pinfunction "GPIO130_P$57") (pintype "bidirectional"))
    )
    (net (code "98") (name "GPIO131") (class "Default")
      (node (ref "IC2") (pin "8") (pinfunction "B4_8") (pintype "bidirectional"))
      (node (ref "J155") (pin "P$1") (pinfunction "P$1_P$1") (pintype "bidirectional"))
      (node (ref "J155") (pin "P$2") (pinfunction "P$2_P$2") (pintype "bidirectional"))
      (node (ref "J155") (pin "P$3") (pinfunction "P$3_P$3") (pintype "bidirectional"))
      (node (ref "L1") (pin "P$58") (pinfunction "GPIO131_P$58") (pintype "bidirectional"))
    )
    (net (code "99") (name "GPIO139") (class "Default")
      (node (ref "J170") (pin "P$1") (pinfunction "P$1_P$1") (pintype "bidirectional"))
      (node (ref "J170") (pin "P$2") (pinfunction "P$2_P$2") (pintype "bidirectional"))
      (node (ref "J170") (pin "P$3") (pinfunction "P$3_P$3") (pintype "bidirectional"))
      (node (ref "L1") (pin "P$43") (pinfunction "GPIO139/SCIRXDC_P$43") (pintype "bidirectional"))
      (node (ref "SV27") (pin "12") (pinfunction "12_12") (pintype "passive"))
    )
    (net (code "100") (name "GPIO157") (class "Default")
      (node (ref "J141") (pin "P$1") (pinfunction "P$1_P$1") (pintype "bidirectional"))
      (node (ref "J141") (pin "P$2") (pinfunction "P$2_P$2") (pintype "bidirectional"))
      (node (ref "J141") (pin "P$3") (pinfunction "P$3_P$3") (pintype "bidirectional"))
      (node (ref "L1") (pin "P$72") (pinfunction "DAC3_P$72") (pintype "bidirectional"))
      (node (ref "R19") (pin "1") (pinfunction "1_1") (pintype "passive"))
      (node (ref "SV64") (pin "1") (pinfunction "1_1") (pintype "passive"))
      (node (ref "SV64") (pin "2") (pinfunction "2_2") (pintype "passive"))
      (node (ref "SV64") (pin "3") (pinfunction "3_3") (pintype "passive"))
    )
    (net (code "101") (name "GPIO158") (class "Default")
      (node (ref "J142") (pin "P$1") (pinfunction "P$1_P$1") (pintype "bidirectional"))
      (node (ref "J142") (pin "P$2") (pinfunction "P$2_P$2") (pintype "bidirectional"))
      (node (ref "J142") (pin "P$3") (pinfunction "P$3_P$3") (pintype "bidirectional"))
      (node (ref "L1") (pin "P$71") (pinfunction "DAC4_P$71") (pintype "bidirectional"))
      (node (ref "R20") (pin "1") (pinfunction "1_1") (pintype "passive"))
      (node (ref "SV65") (pin "1") (pinfunction "1_1") (pintype "passive"))
      (node (ref "SV65") (pin "2") (pinfunction "2_2") (pintype "passive"))
      (node (ref "SV65") (pin "3") (pinfunction "3_3") (pintype "passive"))
    )
    (net (code "102") (name "GPIO159") (class "Default")
      (node (ref "J114") (pin "P$1") (pinfunction "P$1_P$1") (pintype "bidirectional"))
      (node (ref "J114") (pin "P$2") (pinfunction "P$2_P$2") (pintype "bidirectional"))
      (node (ref "J114") (pin "P$3") (pinfunction "P$3_P$3") (pintype "bidirectional"))
      (node (ref "L1") (pin "P$32") (pinfunction "DAC1_P$32") (pintype "bidirectional"))
      (node (ref "R23") (pin "1") (pinfunction "1_1") (pintype "passive"))
      (node (ref "SV66") (pin "1") (pinfunction "1_1") (pintype "passive"))
      (node (ref "SV66") (pin "2") (pinfunction "2_2") (pintype "passive"))
      (node (ref "SV66") (pin "3") (pinfunction "3_3") (pintype "passive"))
    )
    (net (code "103") (name "GPIO160") (class "Default")
      (node (ref "J113") (pin "P$1") (pinfunction "P$1_P$1") (pintype "bidirectional"))
      (node (ref "J113") (pin "P$2") (pinfunction "P$2_P$2") (pintype "bidirectional"))
      (node (ref "J113") (pin "P$3") (pinfunction "P$3_P$3") (pintype "bidirectional"))
      (node (ref "L1") (pin "P$31") (pinfunction "DAC2_P$31") (pintype "bidirectional"))
      (node (ref "R24") (pin "1") (pinfunction "1_1") (pintype "passive"))
      (node (ref "SV67") (pin "1") (pinfunction "1_1") (pintype "passive"))
      (node (ref "SV67") (pin "2") (pinfunction "2_2") (pintype "passive"))
      (node (ref "SV67") (pin "3") (pinfunction "3_3") (pintype "passive"))
    )
    (net (code "104") (name "I2C5_SCL") (class "Default")
      (node (ref "R22") (pin "1") (pinfunction "1_1") (pintype "passive"))
      (node (ref "SV12") (pin "5") (pinfunction "5_5") (pintype "passive"))
      (node (ref "SV8") (pin "5") (pinfunction "5_5") (pintype "passive"))
      (node (ref "SV9") (pin "5") (pinfunction "5_5") (pintype "passive"))
    )
    (net (code "105") (name "I2C5_SDA") (class "Default")
      (node (ref "R21") (pin "1") (pinfunction "1_1") (pintype "passive"))
      (node (ref "SV12") (pin "3") (pinfunction "3_3") (pintype "passive"))
      (node (ref "SV8") (pin "3") (pinfunction "3_3") (pintype "passive"))
      (node (ref "SV9") (pin "3") (pinfunction "3_3") (pintype "passive"))
    )
    (net (code "106") (name "LINUX_RX") (class "Default")
      (node (ref "SV1") (pin "3") (pinfunction "3_3") (pintype "passive"))
      (node (ref "U2") (pin "12") (pinfunction "ROUT1_12") (pintype "bidirectional"))
    )
    (net (code "107") (name "LINUX_TX") (class "Default")
      (node (ref "SV1") (pin "5") (pinfunction "5_5") (pintype "passive"))
      (node (ref "U2") (pin "11") (pinfunction "DIN1_11") (pintype "bidirectional"))
    )
    (net (code "108") (name "MISO_5V") (class "Default")
      (node (ref "IC2") (pin "20") (pinfunction "A4_20") (pintype "bidirectional"))
      (node (ref "U10") (pin "6") (pinfunction "MISO_6") (pintype "bidirectional"))
      (node (ref "U7") (pin "6") (pinfunction "MISO_6") (pintype "bidirectional"))
      (node (ref "U8") (pin "6") (pinfunction "MISO_6") (pintype "bidirectional"))
      (node (ref "U9") (pin "6") (pinfunction "MISO_6") (pintype "bidirectional"))
    )
    (net (code "109") (name "MOSI_5V") (class "Default")
      (node (ref "IC2") (pin "18") (pinfunction "A3_18") (pintype "bidirectional"))
      (node (ref "U10") (pin "7") (pinfunction "MOSI_7") (pintype "bidirectional"))
      (node (ref "U7") (pin "7") (pinfunction "MOSI_7") (pintype "bidirectional"))
      (node (ref "U8") (pin "7") (pinfunction "MOSI_7") (pintype "bidirectional"))
      (node (ref "U9") (pin "7") (pinfunction "MOSI_7") (pintype "bidirectional"))
    )
    (net (code "110") (name "Net-(B1-PadP$1)") (class "Default")
      (node (ref "B1") (pin "P$1") (pinfunction "P$1_P$1") (pintype "bidirectional"))
      (node (ref "R1") (pin "1") (pinfunction "1_1") (pintype "passive"))
    )
    (net (code "111") (name "Net-(B4-P1)") (class "Default")
      (node (ref "B4") (pin "P$1") (pinfunction "P1_P$1") (pintype "bidirectional"))
      (node (ref "SV14") (pin "1") (pinfunction "1_1") (pintype "passive"))
      (node (ref "U5") (pin "P$1") (pinfunction "IN1_P$1") (pintype "bidirectional"))
    )
    (net (code "112") (name "Net-(B5-P1)") (class "Default")
      (node (ref "B5") (pin "P$1") (pinfunction "P1_P$1") (pintype "bidirectional"))
      (node (ref "SV13") (pin "2") (pinfunction "2_2") (pintype "passive"))
      (node (ref "U5") (pin "P$6") (pinfunction "OUT2_P$6") (pintype "bidirectional"))
    )
    (net (code "113") (name "Net-(C27-Pad1)") (class "Default")
      (node (ref "C27") (pin "1") (pinfunction "1_1") (pintype "passive"))
      (node (ref "L2") (pin "1") (pinfunction "1_1") (pintype "passive"))
      (node (ref "X2") (pin "VBUS") (pinfunction "VBUS_VBUS") (pintype "bidirectional"))
    )
    (net (code "114") (name "Net-(ETH1-INT{slash})") (class "Default")
      (node (ref "ETH1") (pin "P$6") (pinfunction "INT/_P$6") (pintype "bidirectional"))
      (node (ref "SV7") (pin "7") (pinfunction "7_7") (pintype "passive"))
      (node (ref "SV7") (pin "8") (pinfunction "8_8") (pintype "passive"))
    )
    (net (code "115") (name "Net-(ETH1-MISO)") (class "Default")
      (node (ref "ETH1") (pin "P$7") (pinfunction "MISO_P$7") (pintype "bidirectional"))
      (node (ref "SV7") (pin "10") (pinfunction "10_10") (pintype "passive"))
      (node (ref "SV7") (pin "9") (pinfunction "9_9") (pintype "passive"))
    )
    (net (code "116") (name "Net-(ETH1-MOSI)") (class "Default")
      (node (ref "ETH1") (pin "P$3") (pinfunction "MOSI_P$3") (pintype "bidirectional"))
      (node (ref "SV11") (pin "10") (pinfunction "10_10") (pintype "passive"))
      (node (ref "SV11") (pin "9") (pinfunction "9_9") (pintype "passive"))
    )
    (net (code "117") (name "Net-(ETH1-RESET)") (class "Default")
      (node (ref "ETH1") (pin "P$8") (pinfunction "RESET_P$8") (pintype "bidirectional"))
      (node (ref "SV11") (pin "7") (pinfunction "7_7") (pintype "passive"))
      (node (ref "SV11") (pin "8") (pinfunction "8_8") (pintype "passive"))
    )
    (net (code "118") (name "Net-(ETH1-SCLK)") (class "Default")
      (node (ref "ETH1") (pin "P$4") (pinfunction "SCLK_P$4") (pintype "bidirectional"))
      (node (ref "SV11") (pin "11") (pinfunction "11_11") (pintype "passive"))
      (node (ref "SV11") (pin "12") (pinfunction "12_12") (pintype "passive"))
    )
    (net (code "119") (name "Net-(ETH1-SS{slash})") (class "Default")
      (node (ref "ETH1") (pin "P$5") (pinfunction "SS/_P$5") (pintype "bidirectional"))
      (node (ref "SV7") (pin "11") (pinfunction "11_11") (pintype "passive"))
      (node (ref "SV7") (pin "12") (pinfunction "12_12") (pintype "passive"))
    )
    (net (code "120") (name "Net-(IC3-RATEOUT)") (class "Default")
      (node (ref "IC3") (pin "2") (pinfunction "RATEOUT_2") (pintype "bidirectional"))
      (node (ref "R9") (pin "2") (pinfunction "2_2") (pintype "passive"))
    )
    (net (code "121") (name "Net-(IC4A-I)") (class "Default")
      (node (ref "IC4") (pin "1") (pinfunction "I_1") (pintype "input"))
      (node (ref "SV41") (pin "2") (pinfunction "2_2") (pintype "passive"))
    )
    (net (code "122") (name "Net-(IC4A-O)") (class "Default")
      (node (ref "IC4") (pin "2") (pinfunction "O_2") (pintype "output"))
      (node (ref "R1") (pin "2") (pinfunction "2_2") (pintype "passive"))
    )
    (net (code "123") (name "Net-(IC4B-I)") (class "Default")
      (node (ref "IC4") (pin "3") (pinfunction "I_3") (pintype "input"))
      (node (ref "SV41") (pin "4") (pinfunction "4_4") (pintype "passive"))
    )
    (net (code "124") (name "Net-(IC4B-O)") (class "Default")
      (node (ref "IC4") (pin "4") (pinfunction "O_4") (pintype "output"))
      (node (ref "LED1") (pin "C") (pinfunction "C_C") (pintype "passive"))
    )
    (net (code "125") (name "Net-(IC4C-I)") (class "Default")
      (node (ref "IC4") (pin "5") (pinfunction "I_5") (pintype "input"))
      (node (ref "SV41") (pin "6") (pinfunction "6_6") (pintype "passive"))
    )
    (net (code "126") (name "Net-(IC4C-O)") (class "Default")
      (node (ref "IC4") (pin "6") (pinfunction "O_6") (pintype "output"))
      (node (ref "LED2") (pin "C") (pinfunction "C_C") (pintype "passive"))
    )
    (net (code "127") (name "Net-(IC4D-I)") (class "Default")
      (node (ref "IC4") (pin "9") (pinfunction "I_9") (pintype "input"))
      (node (ref "SV41") (pin "8") (pinfunction "8_8") (pintype "passive"))
    )
    (net (code "128") (name "Net-(IC4D-O)") (class "Default")
      (node (ref "IC4") (pin "8") (pinfunction "O_8") (pintype "output"))
      (node (ref "LED3") (pin "C") (pinfunction "C_C") (pintype "passive"))
    )
    (net (code "129") (name "Net-(IC4E-I)") (class "Default")
      (node (ref "IC4") (pin "11") (pinfunction "I_11") (pintype "input"))
      (node (ref "SV41") (pin "10") (pinfunction "10_10") (pintype "passive"))
    )
    (net (code "130") (name "Net-(IC4E-O)") (class "Default")
      (node (ref "IC4") (pin "10") (pinfunction "O_10") (pintype "output"))
      (node (ref "LED4") (pin "C") (pinfunction "C_C") (pintype "passive"))
    )
    (net (code "131") (name "Net-(IC4F-I)") (class "Default")
      (node (ref "IC4") (pin "13") (pinfunction "I_13") (pintype "input"))
      (node (ref "SV41") (pin "12") (pinfunction "12_12") (pintype "passive"))
    )
    (net (code "132") (name "Net-(IC4F-O)") (class "Default")
      (node (ref "IC4") (pin "12") (pinfunction "O_12") (pintype "output"))
      (node (ref "LED5") (pin "C") (pinfunction "C_C") (pintype "passive"))
    )
    (net (code "133") (name "Net-(J12-PadP$1)") (class "Default")
      (node (ref "J12") (pin "P$1") (pinfunction "P$1_P$1") (pintype "bidirectional"))
      (node (ref "J12") (pin "P$2") (pinfunction "P$2_P$2") (pintype "bidirectional"))
    )
    (net (code "134") (name "Net-(J13-PadP$1)") (class "Default")
      (node (ref "J13") (pin "P$1") (pinfunction "P$1_P$1") (pintype "bidirectional"))
      (node (ref "J13") (pin "P$2") (pinfunction "P$2_P$2") (pintype "bidirectional"))
    )
    (net (code "135") (name "Net-(J22-PadP$1)") (class "Default")
      (node (ref "J22") (pin "P$1") (pinfunction "P$1_P$1") (pintype "bidirectional"))
      (node (ref "J22") (pin "P$2") (pinfunction "P$2_P$2") (pintype "bidirectional"))
    )
    (net (code "136") (name "Net-(LED1-PadA)") (class "Default")
      (node (ref "LED1") (pin "A") (pinfunction "A_A") (pintype "passive"))
      (node (ref "R2") (pin "2") (pinfunction "2_2") (pintype "passive"))
    )
    (net (code "137") (name "Net-(LED2-PadA)") (class "Default")
      (node (ref "LED2") (pin "A") (pinfunction "A_A") (pintype "passive"))
      (node (ref "R3") (pin "2") (pinfunction "2_2") (pintype "passive"))
    )
    (net (code "138") (name "Net-(LED3-PadA)") (class "Default")
      (node (ref "LED3") (pin "A") (pinfunction "A_A") (pintype "passive"))
      (node (ref "R4") (pin "2") (pinfunction "2_2") (pintype "passive"))
    )
    (net (code "139") (name "Net-(LED4-PadA)") (class "Default")
      (node (ref "LED4") (pin "A") (pinfunction "A_A") (pintype "passive"))
      (node (ref "R5") (pin "2") (pinfunction "2_2") (pintype "passive"))
    )
    (net (code "140") (name "Net-(LED5-PadA)") (class "Default")
      (node (ref "LED5") (pin "A") (pinfunction "A_A") (pintype "passive"))
      (node (ref "R6") (pin "2") (pinfunction "2_2") (pintype "passive"))
    )
    (net (code "141") (name "Net-(LED6-PadA)") (class "Default")
      (node (ref "LED6") (pin "A") (pinfunction "A_A") (pintype "passive"))
      (node (ref "R33") (pin "1") (pinfunction "1_1") (pintype "passive"))
    )
    (net (code "142") (name "Net-(LED17-PadA)") (class "Default")
      (node (ref "LED17") (pin "A") (pinfunction "A_A") (pintype "passive"))
      (node (ref "R36") (pin "1") (pinfunction "1_1") (pintype "passive"))
    )
    (net (code "143") (name "Net-(LED_RX1-C)") (class "Default")
      (node (ref "LED_RX1") (pin "K") (pinfunction "C_K") (pintype "passive"))
      (node (ref "U6") (pin "23") (pinfunction "CBUS0_23") (pintype "bidirectional"))
    )
    (net (code "144") (name "Net-(LED_RX1-PadA)") (class "Default")
      (node (ref "LED_RX1") (pin "A") (pinfunction "A_A") (pintype "passive"))
      (node (ref "R30") (pin "1") (pinfunction "1_1") (pintype "passive"))
    )
    (net (code "145") (name "Net-(LED_TX1-C)") (class "Default")
      (node (ref "LED_TX1") (pin "K") (pinfunction "C_K") (pintype "passive"))
      (node (ref "U6") (pin "22") (pinfunction "CBUS1_22") (pintype "bidirectional"))
    )
    (net (code "146") (name "Net-(LED_TX1-PadA)") (class "Default")
      (node (ref "LED_TX1") (pin "A") (pinfunction "A_A") (pintype "passive"))
      (node (ref "R31") (pin "1") (pinfunction "1_1") (pintype "passive"))
    )
    (net (code "147") (name "Net-(QG1-OUT)") (class "Default")
      (node (ref "QG1") (pin "8") (pinfunction "OUT_8") (pintype "output"))
      (node (ref "U10") (pin "2") (pinfunction "FCKI_2") (pintype "bidirectional"))
      (node (ref "U7") (pin "2") (pinfunction "FCKI_2") (pintype "bidirectional"))
      (node (ref "U8") (pin "2") (pinfunction "FCKI_2") (pintype "bidirectional"))
      (node (ref "U9") (pin "2") (pinfunction "FCKI_2") (pintype "bidirectional"))
    )
    (net (code "148") (name "Net-(R11-Pad1)") (class "Default")
      (node (ref "R11") (pin "1") (pinfunction "1_1") (pintype "passive"))
      (node (ref "R12") (pin "2") (pinfunction "2_2") (pintype "passive"))
    )
    (net (code "149") (name "Net-(R13-Pad1)") (class "Default")
      (node (ref "R13") (pin "1") (pinfunction "1_1") (pintype "passive"))
      (node (ref "R14") (pin "2") (pinfunction "2_2") (pintype "passive"))
    )
    (net (code "150") (name "Net-(R15-Pad1)") (class "Default")
      (node (ref "R15") (pin "1") (pinfunction "1_1") (pintype "passive"))
      (node (ref "R16") (pin "2") (pinfunction "2_2") (pintype "passive"))
    )
    (net (code "151") (name "Net-(R32-Pad1)") (class "Default")
      (node (ref "R32") (pin "1") (pinfunction "1_1") (pintype "passive"))
      (node (ref "USB_PWR1") (pin "A") (pinfunction "A_A") (pintype "passive"))
    )
    (net (code "152") (name "Net-(SV5-Pad1)") (class "Default")
      (node (ref "SV5") (pin "1") (pinfunction "1_1") (pintype "passive"))
      (node (ref "SV5") (pin "2") (pinfunction "2_2") (pintype "passive"))
    )
    (net (code "153") (name "Net-(SV5-Pad17)") (class "Default")
      (node (ref "SV5") (pin "17") (pinfunction "17_17") (pintype "passive"))
      (node (ref "SV5") (pin "18") (pinfunction "18_18") (pintype "passive"))
    )
    (net (code "154") (name "Net-(SV7-Pad1)") (class "Default")
      (node (ref "SV7") (pin "1") (pinfunction "1_1") (pintype "passive"))
      (node (ref "SV7") (pin "2") (pinfunction "2_2") (pintype "passive"))
    )
    (net (code "155") (name "Net-(SV7-Pad3)") (class "Default")
      (node (ref "SV7") (pin "3") (pinfunction "3_3") (pintype "passive"))
      (node (ref "SV7") (pin "4") (pinfunction "4_4") (pintype "passive"))
    )
    (net (code "156") (name "Net-(SV7-Pad5)") (class "Default")
      (node (ref "SV7") (pin "5") (pinfunction "5_5") (pintype "passive"))
      (node (ref "SV7") (pin "6") (pinfunction "6_6") (pintype "passive"))
    )
    (net (code "157") (name "Net-(SV11-Pad5)") (class "Default")
      (node (ref "SV11") (pin "5") (pinfunction "5_5") (pintype "passive"))
      (node (ref "SV11") (pin "6") (pinfunction "6_6") (pintype "passive"))
    )
    (net (code "158") (name "Net-(SV12-Pad4)") (class "Default")
      (node (ref "SV12") (pin "4") (pinfunction "4_4") (pintype "passive"))
      (node (ref "SV8") (pin "4") (pinfunction "4_4") (pintype "passive"))
      (node (ref "SV9") (pin "4") (pinfunction "4_4") (pintype "passive"))
    )
    (net (code "159") (name "Net-(SV53-Pad1)") (class "Default")
      (node (ref "SV53") (pin "1") (pinfunction "1_1") (pintype "passive"))
      (node (ref "SV54") (pin "1") (pinfunction "1_1") (pintype "passive"))
      (node (ref "SV55") (pin "1") (pinfunction "1_1") (pintype "passive"))
    )
    (net (code "160") (name "Net-(SV53-Pad2)") (class "Default")
      (node (ref "SV53") (pin "2") (pinfunction "2_2") (pintype "passive"))
      (node (ref "SV54") (pin "2") (pinfunction "2_2") (pintype "passive"))
      (node (ref "SV55") (pin "2") (pinfunction "2_2") (pintype "passive"))
    )
    (net (code "161") (name "Net-(SV53-Pad3)") (class "Default")
      (node (ref "SV53") (pin "3") (pinfunction "3_3") (pintype "passive"))
      (node (ref "SV54") (pin "3") (pinfunction "3_3") (pintype "passive"))
      (node (ref "SV55") (pin "3") (pinfunction "3_3") (pintype "passive"))
    )
    (net (code "162") (name "Net-(SV53-Pad4)") (class "Default")
      (node (ref "SV53") (pin "4") (pinfunction "4_4") (pintype "passive"))
      (node (ref "SV54") (pin "4") (pinfunction "4_4") (pintype "passive"))
      (node (ref "SV55") (pin "4") (pinfunction "4_4") (pintype "passive"))
    )
    (net (code "163") (name "Net-(SV53-Pad5)") (class "Default")
      (node (ref "SV53") (pin "5") (pinfunction "5_5") (pintype "passive"))
      (node (ref "SV54") (pin "5") (pinfunction "5_5") (pintype "passive"))
      (node (ref "SV55") (pin "5") (pinfunction "5_5") (pintype "passive"))
    )
    (net (code "164") (name "Net-(SV53-Pad6)") (class "Default")
      (node (ref "SV53") (pin "6") (pinfunction "6_6") (pintype "passive"))
      (node (ref "SV54") (pin "6") (pinfunction "6_6") (pintype "passive"))
      (node (ref "SV55") (pin "6") (pinfunction "6_6") (pintype "passive"))
    )
    (net (code "165") (name "Net-(SV53-Pad7)") (class "Default")
      (node (ref "SV53") (pin "7") (pinfunction "7_7") (pintype "passive"))
      (node (ref "SV54") (pin "7") (pinfunction "7_7") (pintype "passive"))
      (node (ref "SV55") (pin "7") (pinfunction "7_7") (pintype "passive"))
    )
    (net (code "166") (name "Net-(SV53-Pad8)") (class "Default")
      (node (ref "SV53") (pin "8") (pinfunction "8_8") (pintype "passive"))
      (node (ref "SV54") (pin "8") (pinfunction "8_8") (pintype "passive"))
      (node (ref "SV55") (pin "8") (pinfunction "8_8") (pintype "passive"))
    )
    (net (code "167") (name "Net-(SV53-Pad9)") (class "Default")
      (node (ref "SV53") (pin "9") (pinfunction "9_9") (pintype "passive"))
      (node (ref "SV54") (pin "9") (pinfunction "9_9") (pintype "passive"))
      (node (ref "SV55") (pin "9") (pinfunction "9_9") (pintype "passive"))
    )
    (net (code "168") (name "Net-(SV53-Pad10)") (class "Default")
      (node (ref "SV53") (pin "10") (pinfunction "10_10") (pintype "passive"))
      (node (ref "SV54") (pin "10") (pinfunction "10_10") (pintype "passive"))
      (node (ref "SV55") (pin "10") (pinfunction "10_10") (pintype "passive"))
    )
    (net (code "169") (name "Net-(SV56-Pad1)") (class "Default")
      (node (ref "SV56") (pin "1") (pinfunction "1_1") (pintype "passive"))
      (node (ref "SV57") (pin "1") (pinfunction "1_1") (pintype "passive"))
      (node (ref "SV58") (pin "1") (pinfunction "1_1") (pintype "passive"))
    )
    (net (code "170") (name "Net-(SV56-Pad2)") (class "Default")
      (node (ref "SV56") (pin "2") (pinfunction "2_2") (pintype "passive"))
      (node (ref "SV57") (pin "2") (pinfunction "2_2") (pintype "passive"))
      (node (ref "SV58") (pin "2") (pinfunction "2_2") (pintype "passive"))
    )
    (net (code "171") (name "Net-(SV56-Pad3)") (class "Default")
      (node (ref "SV56") (pin "3") (pinfunction "3_3") (pintype "passive"))
      (node (ref "SV57") (pin "3") (pinfunction "3_3") (pintype "passive"))
      (node (ref "SV58") (pin "3") (pinfunction "3_3") (pintype "passive"))
    )
    (net (code "172") (name "Net-(SV56-Pad4)") (class "Default")
      (node (ref "SV56") (pin "4") (pinfunction "4_4") (pintype "passive"))
      (node (ref "SV57") (pin "4") (pinfunction "4_4") (pintype "passive"))
      (node (ref "SV58") (pin "4") (pinfunction "4_4") (pintype "passive"))
    )
    (net (code "173") (name "Net-(SV56-Pad5)") (class "Default")
      (node (ref "SV56") (pin "5") (pinfunction "5_5") (pintype "passive"))
      (node (ref "SV57") (pin "5") (pinfunction "5_5") (pintype "passive"))
      (node (ref "SV58") (pin "5") (pinfunction "5_5") (pintype "passive"))
    )
    (net (code "174") (name "Net-(SV56-Pad6)") (class "Default")
      (node (ref "SV56") (pin "6") (pinfunction "6_6") (pintype "passive"))
      (node (ref "SV57") (pin "6") (pinfunction "6_6") (pintype "passive"))
      (node (ref "SV58") (pin "6") (pinfunction "6_6") (pintype "passive"))
    )
    (net (code "175") (name "Net-(SV56-Pad7)") (class "Default")
      (node (ref "SV56") (pin "7") (pinfunction "7_7") (pintype "passive"))
      (node (ref "SV57") (pin "7") (pinfunction "7_7") (pintype "passive"))
      (node (ref "SV58") (pin "7") (pinfunction "7_7") (pintype "passive"))
    )
    (net (code "176") (name "Net-(SV56-Pad8)") (class "Default")
      (node (ref "SV56") (pin "8") (pinfunction "8_8") (pintype "passive"))
      (node (ref "SV57") (pin "8") (pinfunction "8_8") (pintype "passive"))
      (node (ref "SV58") (pin "8") (pinfunction "8_8") (pintype "passive"))
    )
    (net (code "177") (name "Net-(SV56-Pad9)") (class "Default")
      (node (ref "SV56") (pin "9") (pinfunction "9_9") (pintype "passive"))
      (node (ref "SV57") (pin "9") (pinfunction "9_9") (pintype "passive"))
      (node (ref "SV58") (pin "9") (pinfunction "9_9") (pintype "passive"))
    )
    (net (code "178") (name "Net-(SV56-Pad10)") (class "Default")
      (node (ref "SV56") (pin "10") (pinfunction "10_10") (pintype "passive"))
      (node (ref "SV57") (pin "10") (pinfunction "10_10") (pintype "passive"))
      (node (ref "SV58") (pin "10") (pinfunction "10_10") (pintype "passive"))
    )
    (net (code "179") (name "Net-(U$1-P3_SCLK)") (class "Default")
      (node (ref "J125") (pin "P$1") (pinfunction "P$1_P$1") (pintype "bidirectional"))
      (node (ref "J125") (pin "P$2") (pinfunction "P$2_P$2") (pintype "bidirectional"))
      (node (ref "J125") (pin "P$3") (pinfunction "P$3_P$3") (pintype "bidirectional"))
      (node (ref "U$1") (pin "3") (pinfunction "P3_SCLK_3") (pintype "bidirectional"))
    )
    (net (code "180") (name "Net-(U$1-P4_SDA{slash}SPIMOSI)") (class "Default")
      (node (ref "J126") (pin "P$1") (pinfunction "P$1_P$1") (pintype "bidirectional"))
      (node (ref "J126") (pin "P$2") (pinfunction "P$2_P$2") (pintype "bidirectional"))
      (node (ref "J126") (pin "P$3") (pinfunction "P$3_P$3") (pintype "bidirectional"))
      (node (ref "U$1") (pin "4") (pinfunction "P4_SDA/SPIMOSI_4") (pintype "bidirectional"))
    )
    (net (code "181") (name "Net-(U$1-P5_EDA{slash}AUX-DA)") (class "Default")
      (node (ref "J127") (pin "P$1") (pinfunction "P$1_P$1") (pintype "bidirectional"))
      (node (ref "J127") (pin "P$2") (pinfunction "P$2_P$2") (pintype "bidirectional"))
      (node (ref "J127") (pin "P$3") (pinfunction "P$3_P$3") (pintype "bidirectional"))
      (node (ref "U$1") (pin "5") (pinfunction "P5_EDA/AUX-DA_5") (pintype "bidirectional"))
    )
    (net (code "182") (name "Net-(U$1-P6_ECL{slash}AUX-CL)") (class "Default")
      (node (ref "J128") (pin "P$1") (pinfunction "P$1_P$1") (pintype "bidirectional"))
      (node (ref "J128") (pin "P$2") (pinfunction "P$2_P$2") (pintype "bidirectional"))
      (node (ref "J128") (pin "P$3") (pinfunction "P$3_P$3") (pintype "bidirectional"))
      (node (ref "U$1") (pin "6") (pinfunction "P6_ECL/AUX-CL_6") (pintype "bidirectional"))
    )
    (net (code "183") (name "Net-(U$1-P7_ADO{slash}SPIMISO)") (class "Default")
      (node (ref "J129") (pin "P$1") (pinfunction "P$1_P$1") (pintype "bidirectional"))
      (node (ref "J129") (pin "P$2") (pinfunction "P$2_P$2") (pintype "bidirectional"))
      (node (ref "J129") (pin "P$3") (pinfunction "P$3_P$3") (pintype "bidirectional"))
      (node (ref "U$1") (pin "7") (pinfunction "P7_ADO/SPIMISO_7") (pintype "bidirectional"))
    )
    (net (code "184") (name "Net-(U$1-P8_INT)") (class "Default")
      (node (ref "J130") (pin "P$1") (pinfunction "P$1_P$1") (pintype "bidirectional"))
      (node (ref "J130") (pin "P$2") (pinfunction "P$2_P$2") (pintype "bidirectional"))
      (node (ref "J130") (pin "P$3") (pinfunction "P$3_P$3") (pintype "bidirectional"))
      (node (ref "U$1") (pin "8") (pinfunction "P8_INT_8") (pintype "bidirectional"))
    )
    (net (code "185") (name "Net-(U$1-P9_NCS)") (class "Default")
      (node (ref "J131") (pin "P$1") (pinfunction "P$1_P$1") (pintype "bidirectional"))
      (node (ref "J131") (pin "P$2") (pinfunction "P$2_P$2") (pintype "bidirectional"))
      (node (ref "J131") (pin "P$3") (pinfunction "P$3_P$3") (pintype "bidirectional"))
      (node (ref "U$1") (pin "9") (pinfunction "P9_NCS_9") (pintype "bidirectional"))
    )
    (net (code "186") (name "Net-(U$1-P10_FSYNC)") (class "Default")
      (node (ref "J132") (pin "P$1") (pinfunction "P$1_P$1") (pintype "bidirectional"))
      (node (ref "J132") (pin "P$2") (pinfunction "P$2_P$2") (pintype "bidirectional"))
      (node (ref "J132") (pin "P$3") (pinfunction "P$3_P$3") (pintype "bidirectional"))
      (node (ref "U$1") (pin "10") (pinfunction "P10_FSYNC_10") (pintype "bidirectional"))
    )
    (net (code "187") (name "Net-(U2-C1+)") (class "Default")
      (node (ref "C8") (pin "1") (pinfunction "1_1") (pintype "passive"))
      (node (ref "U2") (pin "1") (pinfunction "C1+_1") (pintype "bidirectional"))
    )
    (net (code "188") (name "Net-(U2-C1-)") (class "Default")
      (node (ref "C8") (pin "2") (pinfunction "2_2") (pintype "passive"))
      (node (ref "U2") (pin "3") (pinfunction "C1-_3") (pintype "bidirectional"))
    )
    (net (code "189") (name "Net-(U2-C2+)") (class "Default")
      (node (ref "C9") (pin "1") (pinfunction "1_1") (pintype "passive"))
      (node (ref "U2") (pin "4") (pinfunction "C2+_4") (pintype "bidirectional"))
    )
    (net (code "190") (name "Net-(U2-C2-)") (class "Default")
      (node (ref "C9") (pin "2") (pinfunction "2_2") (pintype "passive"))
      (node (ref "U2") (pin "5") (pinfunction "C2-_5") (pintype "bidirectional"))
    )
    (net (code "191") (name "Net-(U2-DIN2)") (class "Default")
      (node (ref "SV1") (pin "7") (pinfunction "7_7") (pintype "passive"))
      (node (ref "SV1") (pin "8") (pinfunction "8_8") (pintype "passive"))
      (node (ref "U2") (pin "10") (pinfunction "DIN2_10") (pintype "bidirectional"))
    )
    (net (code "192") (name "Net-(U2-ROUT2)") (class "Default")
      (node (ref "SV1") (pin "10") (pinfunction "10_10") (pintype "passive"))
      (node (ref "SV1") (pin "9") (pinfunction "9_9") (pintype "passive"))
      (node (ref "U2") (pin "9") (pinfunction "ROUT2_9") (pintype "bidirectional"))
    )
    (net (code "193") (name "Net-(U2-V+)") (class "Default")
      (node (ref "C7") (pin "2") (pinfunction "2_2") (pintype "passive"))
      (node (ref "U2") (pin "2") (pinfunction "V+_2") (pintype "bidirectional"))
    )
    (net (code "194") (name "Net-(U2-V-)") (class "Default")
      (node (ref "C10") (pin "1") (pinfunction "1_1") (pintype "passive"))
      (node (ref "U2") (pin "6") (pinfunction "V-_6") (pintype "bidirectional"))
    )
    (net (code "195") (name "Net-(U3-~{HOLD})") (class "Default")
      (node (ref "R25") (pin "1") (pinfunction "1_1") (pintype "passive"))
      (node (ref "U3") (pin "7") (pinfunction "~{HOLD}_7") (pintype "bidirectional"))
    )
    (net (code "196") (name "Net-(U4-C1+)") (class "Default")
      (node (ref "C16") (pin "1") (pinfunction "1_1") (pintype "passive"))
      (node (ref "U4") (pin "1") (pinfunction "C1+_1") (pintype "bidirectional"))
    )
    (net (code "197") (name "Net-(U4-C1-)") (class "Default")
      (node (ref "C16") (pin "2") (pinfunction "2_2") (pintype "passive"))
      (node (ref "U4") (pin "3") (pinfunction "C1-_3") (pintype "bidirectional"))
    )
    (net (code "198") (name "Net-(U4-C2+)") (class "Default")
      (node (ref "C17") (pin "1") (pinfunction "1_1") (pintype "passive"))
      (node (ref "U4") (pin "4") (pinfunction "C2+_4") (pintype "bidirectional"))
    )
    (net (code "199") (name "Net-(U4-C2-)") (class "Default")
      (node (ref "C17") (pin "2") (pinfunction "2_2") (pintype "passive"))
      (node (ref "U4") (pin "5") (pinfunction "C2-_5") (pintype "bidirectional"))
    )
    (net (code "200") (name "Net-(U4-DIN1)") (class "Default")
      (node (ref "SV27") (pin "5") (pinfunction "5_5") (pintype "passive"))
      (node (ref "SV27") (pin "6") (pinfunction "6_6") (pintype "passive"))
      (node (ref "U4") (pin "11") (pinfunction "DIN1_11") (pintype "bidirectional"))
    )
    (net (code "201") (name "Net-(U4-DIN2)") (class "Default")
      (node (ref "SV27") (pin "7") (pinfunction "7_7") (pintype "passive"))
      (node (ref "SV27") (pin "9") (pinfunction "9_9") (pintype "passive"))
      (node (ref "U4") (pin "10") (pinfunction "DIN2_10") (pintype "bidirectional"))
    )
    (net (code "202") (name "Net-(U4-ROUT1)") (class "Default")
      (node (ref "SV27") (pin "3") (pinfunction "3_3") (pintype "passive"))
      (node (ref "SV27") (pin "4") (pinfunction "4_4") (pintype "passive"))
      (node (ref "U4") (pin "12") (pinfunction "ROUT1_12") (pintype "bidirectional"))
    )
    (net (code "203") (name "Net-(U4-ROUT2)") (class "Default")
      (node (ref "SV27") (pin "11") (pinfunction "11_11") (pintype "passive"))
      (node (ref "SV27") (pin "13") (pinfunction "13_13") (pintype "passive"))
      (node (ref "U4") (pin "9") (pinfunction "ROUT2_9") (pintype "bidirectional"))
    )
    (net (code "204") (name "Net-(U4-V+)") (class "Default")
      (node (ref "C15") (pin "2") (pinfunction "2_2") (pintype "passive"))
      (node (ref "U4") (pin "2") (pinfunction "V+_2") (pintype "bidirectional"))
    )
    (net (code "205") (name "Net-(U4-V-)") (class "Default")
      (node (ref "C18") (pin "1") (pinfunction "1_1") (pintype "passive"))
      (node (ref "U4") (pin "6") (pinfunction "V-_6") (pintype "bidirectional"))
    )
    (net (code "206") (name "Net-(U5-IN2)") (class "Default")
      (node (ref "SV14") (pin "2") (pinfunction "2_2") (pintype "passive"))
      (node (ref "U5") (pin "P$2") (pinfunction "IN2_P$2") (pintype "bidirectional"))
    )
    (net (code "207") (name "Net-(U5-IN3)") (class "Default")
      (node (ref "SV14") (pin "3") (pinfunction "3_3") (pintype "passive"))
      (node (ref "U5") (pin "P$3") (pinfunction "IN3_P$3") (pintype "bidirectional"))
    )
    (net (code "208") (name "Net-(U5-OUT1)") (class "Default")
      (node (ref "SV13") (pin "1") (pinfunction "1_1") (pintype "passive"))
      (node (ref "U5") (pin "P$7") (pinfunction "OUT1_P$7") (pintype "bidirectional"))
    )
    (net (code "209") (name "Net-(U5-OUT3)") (class "Default")
      (node (ref "SV13") (pin "3") (pinfunction "3_3") (pintype "passive"))
      (node (ref "U5") (pin "P$5") (pinfunction "OUT3_P$5") (pintype "bidirectional"))
    )
    (net (code "210") (name "Net-(U6-3V3OUT)") (class "Default")
      (node (ref "C26") (pin "1") (pinfunction "1_1") (pintype "passive"))
      (node (ref "U6") (pin "17") (pinfunction "3V3OUT_17") (pintype "output"))
      (node (ref "U6") (pin "4") (pinfunction "VCCIO_4") (pintype "power_in"))
    )
    (net (code "211") (name "Net-(U6-CBUS2)") (class "Default")
      (node (ref "SV20") (pin "3") (pinfunction "3_3") (pintype "passive"))
      (node (ref "U6") (pin "13") (pinfunction "CBUS2_13") (pintype "bidirectional"))
    )
    (net (code "212") (name "Net-(U6-CBUS3)") (class "Default")
      (node (ref "SV20") (pin "7") (pinfunction "7_7") (pintype "passive"))
      (node (ref "U6") (pin "14") (pinfunction "CBUS3_14") (pintype "bidirectional"))
    )
    (net (code "213") (name "Net-(U6-CBUS4)") (class "Default")
      (node (ref "SV20") (pin "9") (pinfunction "9_9") (pintype "passive"))
      (node (ref "U6") (pin "12") (pinfunction "CBUS4_12") (pintype "bidirectional"))
    )
    (net (code "214") (name "Net-(U6-CTS#)") (class "Default")
      (node (ref "SV20") (pin "4") (pinfunction "4_4") (pintype "passive"))
      (node (ref "U6") (pin "11") (pinfunction "CTS#_11") (pintype "input"))
    )
    (net (code "215") (name "Net-(U6-DSR#)") (class "Default")
      (node (ref "SV20") (pin "1") (pinfunction "1_1") (pintype "passive"))
      (node (ref "U6") (pin "9") (pinfunction "DSR#_9") (pintype "input"))
    )
    (net (code "216") (name "Net-(U6-DTR#)") (class "Default")
      (node (ref "SV20") (pin "2") (pinfunction "2_2") (pintype "passive"))
      (node (ref "U6") (pin "2") (pinfunction "DTR#_2") (pintype "output"))
    )
    (net (code "217") (name "Net-(U6-USBDM)") (class "Default")
      (node (ref "C24") (pin "1") (pinfunction "1_1") (pintype "passive"))
      (node (ref "U6") (pin "16") (pinfunction "USBDM_16") (pintype "bidirectional"))
      (node (ref "X2") (pin "D-") (pinfunction "D-_D-") (pintype "bidirectional"))
    )
    (net (code "218") (name "Net-(U6-USBDP)") (class "Default")
      (node (ref "C25") (pin "1") (pinfunction "1_1") (pintype "passive"))
      (node (ref "U6") (pin "15") (pinfunction "USBDP_15") (pintype "bidirectional"))
      (node (ref "X2") (pin "D+") (pinfunction "D+_D+") (pintype "bidirectional"))
    )
    (net (code "219") (name "Net-(U11-VDD)") (class "Default")
      (node (ref "C20") (pin "1") (pinfunction "1_1") (pintype "passive"))
      (node (ref "U11") (pin "1") (pinfunction "VDD_1") (pintype "bidirectional"))
    )
    (net (code "220") (name "Net-(U11-VDD2)") (class "Default")
      (node (ref "C19") (pin "1") (pinfunction "1_1") (pintype "passive"))
      (node (ref "U11") (pin "11") (pinfunction "VDD2_11") (pintype "bidirectional"))
    )
    (net (code "221") (name "Net-(U11-{slash}XRS)") (class "Default")
      (node (ref "P1") (pin "1") (pinfunction "1_1") (pintype "bidirectional"))
      (node (ref "R38") (pin "1") (pinfunction "1_1") (pintype "passive"))
      (node (ref "U11") (pin "17") (pinfunction "/XRS_17") (pintype "bidirectional"))
    )
    (net (code "222") (name "PI5.25") (class "Default")
      (node (ref "J7") (pin "P$2") (pinfunction "P$2_P$2") (pintype "bidirectional"))
      (node (ref "P2") (pin "P$2") (pinfunction "POWER_P$2") (pintype "bidirectional"))
      (node (ref "SV2") (pin "1") (pinfunction "1_1") (pintype "passive"))
      (node (ref "SV2") (pin "2") (pinfunction "2_2") (pintype "passive"))
      (node (ref "SV2") (pin "3") (pinfunction "3_3") (pintype "passive"))
      (node (ref "SV2") (pin "4") (pinfunction "4_4") (pintype "passive"))
    )
    (net (code "223") (name "PI_GPIO2") (class "Default")
      (node (ref "SV22") (pin "4") (pinfunction "4_4") (pintype "passive"))
      (node (ref "SV5") (pin "3") (pinfunction "3_3") (pintype "passive"))
      (node (ref "SV5") (pin "4") (pinfunction "4_4") (pintype "passive"))
    )
    (net (code "224") (name "PI_GPIO3") (class "Default")
      (node (ref "SV22") (pin "6") (pinfunction "6_6") (pintype "passive"))
      (node (ref "SV5") (pin "5") (pinfunction "5_5") (pintype "passive"))
      (node (ref "SV5") (pin "6") (pinfunction "6_6") (pintype "passive"))
    )
    (net (code "225") (name "PI_GPIO6") (class "Default")
      (node (ref "SV22") (pin "8") (pinfunction "8_8") (pintype "passive"))
      (node (ref "SV5") (pin "31") (pinfunction "31_31") (pintype "passive"))
      (node (ref "SV5") (pin "32") (pinfunction "32_32") (pintype "passive"))
    )
    (net (code "226") (name "PI_GPIO7") (class "Default")
      (node (ref "SV2") (pin "25") (pinfunction "25_25") (pintype "passive"))
      (node (ref "SV2") (pin "26") (pinfunction "26_26") (pintype "passive"))
      (node (ref "SV22") (pin "10") (pinfunction "10_10") (pintype "passive"))
    )
    (net (code "227") (name "PI_GPIO10") (class "Default")
      (node (ref "SV22") (pin "12") (pinfunction "12_12") (pintype "passive"))
      (node (ref "SV5") (pin "19") (pinfunction "19_19") (pintype "passive"))
      (node (ref "SV5") (pin "20") (pinfunction "20_20") (pintype "passive"))
    )
    (net (code "228") (name "PI_GPIO11") (class "Default")
      (node (ref "SV22") (pin "14") (pinfunction "14_14") (pintype "passive"))
      (node (ref "SV5") (pin "23") (pinfunction "23_23") (pintype "passive"))
      (node (ref "SV5") (pin "24") (pinfunction "24_24") (pintype "passive"))
    )
    (net (code "229") (name "PI_GPIO16") (class "Default")
      (node (ref "SV2") (pin "35") (pinfunction "35_35") (pintype "passive"))
      (node (ref "SV2") (pin "36") (pinfunction "36_36") (pintype "passive"))
    )
    (net (code "230") (name "PI_GPIO17") (class "Default")
      (node (ref "SV5") (pin "11") (pinfunction "11_11") (pintype "passive"))
      (node (ref "SV5") (pin "12") (pinfunction "12_12") (pintype "passive"))
    )
    (net (code "231") (name "PI_GPIO18") (class "Default")
      (node (ref "SV2") (pin "11") (pinfunction "11_11") (pintype "passive"))
      (node (ref "SV2") (pin "12") (pinfunction "12_12") (pintype "passive"))
    )
    (net (code "232") (name "PI_GPIO19") (class "Default")
      (node (ref "SV5") (pin "35") (pinfunction "35_35") (pintype "passive"))
      (node (ref "SV5") (pin "36") (pinfunction "36_36") (pintype "passive"))
    )
    (net (code "233") (name "PI_GPIO20") (class "Default")
      (node (ref "SV2") (pin "37") (pinfunction "37_37") (pintype "passive"))
      (node (ref "SV2") (pin "38") (pinfunction "38_38") (pintype "passive"))
    )
    (net (code "234") (name "PI_GPIO21") (class "Default")
      (node (ref "SV2") (pin "39") (pinfunction "39_39") (pintype "passive"))
      (node (ref "SV2") (pin "40") (pinfunction "40_40") (pintype "passive"))
    )
    (net (code "235") (name "PI_GPIO22") (class "Default")
      (node (ref "SV5") (pin "15") (pinfunction "15_15") (pintype "passive"))
      (node (ref "SV5") (pin "16") (pinfunction "16_16") (pintype "passive"))
    )
    (net (code "236") (name "PI_GPIO23") (class "Default")
      (node (ref "SV2") (pin "15") (pinfunction "15_15") (pintype "passive"))
      (node (ref "SV2") (pin "16") (pinfunction "16_16") (pintype "passive"))
    )
    (net (code "237") (name "PI_GPIO24") (class "Default")
      (node (ref "SV2") (pin "17") (pinfunction "17_17") (pintype "passive"))
      (node (ref "SV2") (pin "18") (pinfunction "18_18") (pintype "passive"))
    )
    (net (code "238") (name "PI_GPIO25") (class "Default")
      (node (ref "SV2") (pin "21") (pinfunction "21_21") (pintype "passive"))
      (node (ref "SV2") (pin "22") (pinfunction "22_22") (pintype "passive"))
    )
    (net (code "239") (name "PI_GPIO26") (class "Default")
      (node (ref "SV5") (pin "37") (pinfunction "37_37") (pintype "passive"))
      (node (ref "SV5") (pin "38") (pinfunction "38_38") (pintype "passive"))
    )
    (net (code "240") (name "PI_GPIO27") (class "Default")
      (node (ref "SV5") (pin "13") (pinfunction "13_13") (pintype "passive"))
      (node (ref "SV5") (pin "14") (pinfunction "14_14") (pintype "passive"))
    )
    (net (code "241") (name "PI_RXD1") (class "Default")
      (node (ref "SV1") (pin "6") (pinfunction "6_6") (pintype "passive"))
      (node (ref "SV2") (pin "10") (pinfunction "10_10") (pintype "passive"))
      (node (ref "SV2") (pin "9") (pinfunction "9_9") (pintype "passive"))
    )
    (net (code "242") (name "PI_RXD2") (class "Default")
      (node (ref "SV2") (pin "27") (pinfunction "27_27") (pintype "passive"))
      (node (ref "SV2") (pin "28") (pinfunction "28_28") (pintype "passive"))
      (node (ref "SV4") (pin "4") (pinfunction "4_4") (pintype "passive"))
    )
    (net (code "243") (name "PI_RXD3") (class "Default")
      (node (ref "SV27") (pin "14") (pinfunction "14_14") (pintype "passive"))
      (node (ref "SV5") (pin "29") (pinfunction "29_29") (pintype "passive"))
      (node (ref "SV5") (pin "30") (pinfunction "30_30") (pintype "passive"))
    )
    (net (code "244") (name "PI_RXD4") (class "Default")
      (node (ref "SV4") (pin "8") (pinfunction "8_8") (pintype "passive"))
      (node (ref "SV5") (pin "21") (pinfunction "21_21") (pintype "passive"))
      (node (ref "SV5") (pin "22") (pinfunction "22_22") (pintype "passive"))
    )
    (net (code "245") (name "PI_RXD5") (class "Default")
      (node (ref "SV4") (pin "10") (pinfunction "10_10") (pintype "passive"))
      (node (ref "SV5") (pin "33") (pinfunction "33_33") (pintype "passive"))
      (node (ref "SV5") (pin "34") (pinfunction "34_34") (pintype "passive"))
    )
    (net (code "246") (name "PI_TXD1") (class "Default")
      (node (ref "SV1") (pin "4") (pinfunction "4_4") (pintype "passive"))
      (node (ref "SV2") (pin "7") (pinfunction "7_7") (pintype "passive"))
      (node (ref "SV2") (pin "8") (pinfunction "8_8") (pintype "passive"))
    )
    (net (code "247") (name "PI_TXD2") (class "Default")
      (node (ref "SV4") (pin "6") (pinfunction "6_6") (pintype "passive"))
      (node (ref "SV5") (pin "27") (pinfunction "27_27") (pintype "passive"))
      (node (ref "SV5") (pin "28") (pinfunction "28_28") (pintype "passive"))
    )
    (net (code "248") (name "PI_TXD3") (class "Default")
      (node (ref "SV27") (pin "10") (pinfunction "10_10") (pintype "passive"))
      (node (ref "SV5") (pin "7") (pinfunction "7_7") (pintype "passive"))
      (node (ref "SV5") (pin "8") (pinfunction "8_8") (pintype "passive"))
    )
    (net (code "249") (name "PI_TXD4") (class "Default")
      (node (ref "SV2") (pin "23") (pinfunction "23_23") (pintype "passive"))
      (node (ref "SV2") (pin "24") (pinfunction "24_24") (pintype "passive"))
      (node (ref "SV4") (pin "12") (pinfunction "12_12") (pintype "passive"))
    )
    (net (code "250") (name "PI_TXD5") (class "Default")
      (node (ref "SV2") (pin "31") (pinfunction "31_31") (pintype "passive"))
      (node (ref "SV2") (pin "32") (pinfunction "32_32") (pintype "passive"))
      (node (ref "SV4") (pin "14") (pinfunction "14_14") (pintype "passive"))
    )
    (net (code "251") (name "RESET") (class "Default")
      (node (ref "J98") (pin "P$1") (pinfunction "P$1_P$1") (pintype "bidirectional"))
      (node (ref "J98") (pin "P$2") (pinfunction "P$2_P$2") (pintype "bidirectional"))
      (node (ref "J98") (pin "P$3") (pinfunction "P$3_P$3") (pintype "bidirectional"))
      (node (ref "L1") (pin "P$16") (pinfunction "RST_P$16") (pintype "bidirectional"))
    )
    (net (code "252") (name "RESET_2") (class "Default")
      (node (ref "J157") (pin "P$1") (pinfunction "P$1_P$1") (pintype "bidirectional"))
      (node (ref "J157") (pin "P$2") (pinfunction "P$2_P$2") (pintype "bidirectional"))
      (node (ref "J157") (pin "P$3") (pinfunction "P$3_P$3") (pintype "bidirectional"))
      (node (ref "L1") (pin "P$56") (pinfunction "RST_2_P$56") (pintype "bidirectional"))
    )
    (net (code "253") (name "RTS_FT232RL") (class "Default")
      (node (ref "SV20") (pin "6") (pinfunction "6_6") (pintype "passive"))
      (node (ref "U6") (pin "3") (pinfunction "RTS#_3") (pintype "output"))
    )
    (net (code "254") (name "RXD_FT232RL") (class "Default")
      (node (ref "SV20") (pin "8") (pinfunction "8_8") (pintype "passive"))
      (node (ref "U6") (pin "5") (pinfunction "RXD_5") (pintype "input"))
    )
    (net (code "255") (name "SCK_5V") (class "Default")
      (node (ref "IC2") (pin "22") (pinfunction "A5_22") (pintype "bidirectional"))
      (node (ref "U10") (pin "5") (pinfunction "SCK_5") (pintype "bidirectional"))
      (node (ref "U7") (pin "5") (pinfunction "SCK_5") (pintype "bidirectional"))
      (node (ref "U8") (pin "5") (pinfunction "SCK_5") (pintype "bidirectional"))
      (node (ref "U9") (pin "5") (pinfunction "SCK_5") (pintype "bidirectional"))
    )
    (net (code "256") (name "SPI1_ENCA") (class "Default")
      (node (ref "SV23") (pin "5") (pinfunction "5_5") (pintype "passive"))
      (node (ref "U7") (pin "12") (pinfunction "A_12") (pintype "bidirectional"))
    )
    (net (code "257") (name "SPI1_ENCB") (class "Default")
      (node (ref "SV23") (pin "9") (pinfunction "9_9") (pintype "passive"))
      (node (ref "U7") (pin "11") (pinfunction "B_11") (pintype "bidirectional"))
    )
    (net (code "258") (name "SPI2_ENCA") (class "Default")
      (node (ref "SV23") (pin "6") (pinfunction "6_6") (pintype "passive"))
      (node (ref "U8") (pin "12") (pinfunction "A_12") (pintype "bidirectional"))
    )
    (net (code "259") (name "SPI2_ENCB") (class "Default")
      (node (ref "SV23") (pin "10") (pinfunction "10_10") (pintype "passive"))
      (node (ref "U8") (pin "11") (pinfunction "B_11") (pintype "bidirectional"))
    )
    (net (code "260") (name "SPI3_ENCA") (class "Default")
      (node (ref "SV24") (pin "5") (pinfunction "5_5") (pintype "passive"))
      (node (ref "U9") (pin "12") (pinfunction "A_12") (pintype "bidirectional"))
    )
    (net (code "261") (name "SPI3_ENCB") (class "Default")
      (node (ref "SV24") (pin "9") (pinfunction "9_9") (pintype "passive"))
      (node (ref "U9") (pin "11") (pinfunction "B_11") (pintype "bidirectional"))
    )
    (net (code "262") (name "SPI4_ENCA") (class "Default")
      (node (ref "SV24") (pin "6") (pinfunction "6_6") (pintype "passive"))
      (node (ref "U10") (pin "12") (pinfunction "A_12") (pintype "bidirectional"))
    )
    (net (code "263") (name "SPI4_ENCB") (class "Default")
      (node (ref "SV24") (pin "10") (pinfunction "10_10") (pintype "passive"))
      (node (ref "U10") (pin "11") (pinfunction "B_11") (pintype "bidirectional"))
    )
    (net (code "264") (name "SS1_5V") (class "Default")
      (node (ref "IC2") (pin "11") (pinfunction "A5_11") (pintype "bidirectional"))
      (node (ref "U7") (pin "4") (pinfunction "SS/_4") (pintype "bidirectional"))
    )
    (net (code "265") (name "SS2_5V") (class "Default")
      (node (ref "IC2") (pin "9") (pinfunction "A4_9") (pintype "bidirectional"))
      (node (ref "U8") (pin "4") (pinfunction "SS/_4") (pintype "bidirectional"))
    )
    (net (code "266") (name "SS3_5V") (class "Default")
      (node (ref "IC2") (pin "7") (pinfunction "A3_7") (pintype "bidirectional"))
      (node (ref "U9") (pin "4") (pinfunction "SS/_4") (pintype "bidirectional"))
    )
    (net (code "267") (name "SS4_5V") (class "Default")
      (node (ref "IC2") (pin "5") (pinfunction "A2_5") (pintype "bidirectional"))
      (node (ref "U10") (pin "4") (pinfunction "SS/_4") (pintype "bidirectional"))
    )
    (net (code "268") (name "TCK") (class "Default")
      (node (ref "SV15") (pin "11") (pinfunction "11_11") (pintype "passive"))
      (node (ref "SV15") (pin "9") (pinfunction "9_9") (pintype "passive"))
      (node (ref "U11") (pin "31") (pinfunction "GPIO38/XCLKIN(TCK)_31") (pintype "bidirectional"))
    )
    (net (code "269") (name "TDI") (class "Default")
      (node (ref "SV15") (pin "3") (pinfunction "3_3") (pintype "passive"))
      (node (ref "U11") (pin "28") (pinfunction "GPIO35(TDI)_28") (pintype "bidirectional"))
    )
    (net (code "270") (name "TDO") (class "Default")
      (node (ref "R8") (pin "2") (pinfunction "2_2") (pintype "passive"))
      (node (ref "SV15") (pin "7") (pinfunction "7_7") (pintype "passive"))
      (node (ref "U11") (pin "30") (pinfunction "GPIO37(TDO)_30") (pintype "bidirectional"))
    )
    (net (code "271") (name "TMS") (class "Default")
      (node (ref "SV15") (pin "1") (pinfunction "1_1") (pintype "passive"))
      (node (ref "U11") (pin "29") (pinfunction "GPIO36(TMS)_29") (pintype "bidirectional"))
    )
    (net (code "272") (name "TRSTN") (class "Default")
      (node (ref "R7") (pin "1") (pinfunction "1_1") (pintype "passive"))
      (node (ref "SV15") (pin "2") (pinfunction "2_2") (pintype "passive"))
      (node (ref "U11") (pin "16") (pinfunction "/TRST_16") (pintype "bidirectional"))
    )
    (net (code "273") (name "TXD_FT232RL") (class "Default")
      (node (ref "SV20") (pin "10") (pinfunction "10_10") (pintype "passive"))
      (node (ref "U6") (pin "1") (pinfunction "TXD_1") (pintype "output"))
    )
    (net (code "274") (name "UART00_RX") (class "Default")
      (node (ref "U2") (pin "13") (pinfunction "RIN1_13") (pintype "bidirectional"))
      (node (ref "X1") (pin "2") (pinfunction "2_2") (pintype "passive"))
    )
    (net (code "275") (name "UART00_TX") (class "Default")
      (node (ref "U2") (pin "14") (pinfunction "DOUT1_14") (pintype "bidirectional"))
      (node (ref "X1") (pin "3") (pinfunction "3_3") (pintype "passive"))
    )
    (net (code "276") (name "UART01_RX") (class "Default")
      (node (ref "SV6") (pin "1") (pinfunction "1_1") (pintype "passive"))
      (node (ref "U2") (pin "8") (pinfunction "RIN2_8") (pintype "bidirectional"))
    )
    (net (code "277") (name "UART01_TX") (class "Default")
      (node (ref "SV6") (pin "3") (pinfunction "3_3") (pintype "passive"))
      (node (ref "U2") (pin "7") (pinfunction "DOUT2_7") (pintype "bidirectional"))
    )
    (net (code "278") (name "UART02_RX") (class "Default")
      (node (ref "SV3") (pin "1") (pinfunction "1_1") (pintype "passive"))
      (node (ref "U4") (pin "13") (pinfunction "RIN1_13") (pintype "bidirectional"))
    )
    (net (code "279") (name "UART02_TX") (class "Default")
      (node (ref "SV3") (pin "3") (pinfunction "3_3") (pintype "passive"))
      (node (ref "U4") (pin "14") (pinfunction "DOUT1_14") (pintype "bidirectional"))
    )
    (net (code "280") (name "UART03_RX") (class "Default")
      (node (ref "SV3") (pin "10") (pinfunction "10_10") (pintype "passive"))
      (node (ref "U4") (pin "8") (pinfunction "RIN2_8") (pintype "bidirectional"))
    )
    (net (code "281") (name "UART03_TX") (class "Default")
      (node (ref "SV3") (pin "8") (pinfunction "8_8") (pintype "passive"))
      (node (ref "U4") (pin "7") (pinfunction "DOUT2_7") (pintype "bidirectional"))
    )
    (net (code "282") (name "USB_VCC") (class "Default")
      (node (ref "C28") (pin "1") (pinfunction "1_1") (pintype "passive"))
      (node (ref "C29") (pin "1") (pinfunction "1_1") (pintype "passive"))
      (node (ref "L2") (pin "2") (pinfunction "2_2") (pintype "passive"))
      (node (ref "R30") (pin "2") (pinfunction "2_2") (pintype "passive"))
      (node (ref "R31") (pin "2") (pinfunction "2_2") (pintype "passive"))
      (node (ref "R32") (pin "2") (pinfunction "2_2") (pintype "passive"))
      (node (ref "U6") (pin "20") (pinfunction "VCC_20") (pintype "power_in"))
    )
    (net (code "283") (name "unconnected-(ETH1-NC-PadP$9)") (class "Default")
      (node (ref "ETH1") (pin "P$9") (pinfunction "NC_P$9") (pintype "bidirectional"))
    )
    (net (code "284") (name "unconnected-(IC2A-A1-Pad3)") (class "Default")
      (node (ref "IC2") (pin "3") (pinfunction "A1_3") (pintype "bidirectional"))
    )
    (net (code "285") (name "unconnected-(IC2A-B1-Pad2)") (class "Default")
      (node (ref "IC2") (pin "2") (pinfunction "B1_2") (pintype "bidirectional"))
    )
    (net (code "286") (name "unconnected-(IC3-2.5V-Pad7)") (class "Default")
      (node (ref "IC3") (pin "7") (pinfunction "2.5V_7") (pintype "bidirectional"))
    )
    (net (code "287") (name "unconnected-(IC3-CMID-Pad4)") (class "Default")
      (node (ref "IC3") (pin "4") (pinfunction "CMID_4") (pintype "bidirectional"))
    )
    (net (code "288") (name "unconnected-(IC3-CP1-Pad19)") (class "Default")
      (node (ref "IC3") (pin "19") (pinfunction "CP1_19") (pintype "bidirectional"))
    )
    (net (code "289") (name "unconnected-(IC3-CP2-Pad20)") (class "Default")
      (node (ref "IC3") (pin "20") (pinfunction "CP2_20") (pintype "bidirectional"))
    )
    (net (code "290") (name "unconnected-(IC3-CP3-Pad17)") (class "Default")
      (node (ref "IC3") (pin "17") (pinfunction "CP3_17") (pintype "bidirectional"))
    )
    (net (code "291") (name "unconnected-(IC3-CP4-Pad18)") (class "Default")
      (node (ref "IC3") (pin "18") (pinfunction "CP4_18") (pintype "bidirectional"))
    )
    (net (code "292") (name "unconnected-(IC3-CP5-Pad14)") (class "Default")
      (node (ref "IC3") (pin "14") (pinfunction "CP5_14") (pintype "bidirectional"))
    )
    (net (code "293") (name "unconnected-(IC3-NC-Pad5)") (class "Default")
      (node (ref "IC3") (pin "5") (pinfunction "NC_5") (pintype "bidirectional"))
    )
    (net (code "294") (name "unconnected-(IC3-NC-Pad6)") (class "Default")
      (node (ref "IC3") (pin "6") (pinfunction "NC_6") (pintype "bidirectional"))
    )
    (net (code "295") (name "unconnected-(IC3-NC-Pad15)") (class "Default")
      (node (ref "IC3") (pin "15") (pinfunction "NC_15") (pintype "bidirectional"))
    )
    (net (code "296") (name "unconnected-(IC3-NC-Pad16)") (class "Default")
      (node (ref "IC3") (pin "16") (pinfunction "NC_16") (pintype "bidirectional"))
    )
    (net (code "297") (name "unconnected-(IC3-ST1-Pad11)") (class "Default")
      (node (ref "IC3") (pin "11") (pinfunction "ST1_11") (pintype "bidirectional"))
    )
    (net (code "298") (name "unconnected-(IC3-ST2-Pad10)") (class "Default")
      (node (ref "IC3") (pin "10") (pinfunction "ST2_10") (pintype "bidirectional"))
    )
    (net (code "299") (name "unconnected-(IC3-SUMJ-Pad3)") (class "Default")
      (node (ref "IC3") (pin "3") (pinfunction "SUMJ_3") (pintype "bidirectional"))
    )
    (net (code "300") (name "unconnected-(IC3-TEMP-Pad9)") (class "Default")
      (node (ref "IC3") (pin "9") (pinfunction "TEMP_9") (pintype "bidirectional"))
    )
    (net (code "301") (name "unconnected-(QG1-TS-Pad1)") (class "Default")
      (node (ref "QG1") (pin "1") (pinfunction "TS_1") (pintype "passive"))
    )
    (net (code "302") (name "unconnected-(R11-Pad2)") (class "Default")
      (node (ref "R11") (pin "2") (pinfunction "2_2") (pintype "passive"))
    )
    (net (code "303") (name "unconnected-(R13-Pad2)") (class "Default")
      (node (ref "R13") (pin "2") (pinfunction "2_2") (pintype "passive"))
    )
    (net (code "304") (name "unconnected-(R15-Pad2)") (class "Default")
      (node (ref "R15") (pin "2") (pinfunction "2_2") (pintype "passive"))
    )
    (net (code "305") (name "unconnected-(SV3-Pad2)") (class "Default")
      (node (ref "SV3") (pin "2") (pinfunction "2_2") (pintype "passive"))
    )
    (net (code "306") (name "unconnected-(SV3-Pad4)") (class "Default")
      (node (ref "SV3") (pin "4") (pinfunction "4_4") (pintype "passive"))
    )
    (net (code "307") (name "unconnected-(SV3-Pad7)") (class "Default")
      (node (ref "SV3") (pin "7") (pinfunction "7_7") (pintype "passive"))
    )
    (net (code "308") (name "unconnected-(SV3-Pad9)") (class "Default")
      (node (ref "SV3") (pin "9") (pinfunction "9_9") (pintype "passive"))
    )
    (net (code "309") (name "unconnected-(SV6-Pad2)") (class "Default")
      (node (ref "SV6") (pin "2") (pinfunction "2_2") (pintype "passive"))
    )
    (net (code "310") (name "unconnected-(SV6-Pad4)") (class "Default")
      (node (ref "SV6") (pin "4") (pinfunction "4_4") (pintype "passive"))
    )
    (net (code "311") (name "unconnected-(SV6-Pad6)") (class "Default")
      (node (ref "SV6") (pin "6") (pinfunction "6_6") (pintype "passive"))
    )
    (net (code "312") (name "unconnected-(SV6-Pad7)") (class "Default")
      (node (ref "SV6") (pin "7") (pinfunction "7_7") (pintype "passive"))
    )
    (net (code "313") (name "unconnected-(SV6-Pad8)") (class "Default")
      (node (ref "SV6") (pin "8") (pinfunction "8_8") (pintype "passive"))
    )
    (net (code "314") (name "unconnected-(SV6-Pad9)") (class "Default")
      (node (ref "SV6") (pin "9") (pinfunction "9_9") (pintype "passive"))
    )
    (net (code "315") (name "unconnected-(SV6-Pad10)") (class "Default")
      (node (ref "SV6") (pin "10") (pinfunction "10_10") (pintype "passive"))
    )
    (net (code "316") (name "unconnected-(SV10-Pad4)") (class "Default")
      (node (ref "SV10") (pin "4") (pinfunction "4_4") (pintype "passive"))
    )
    (net (code "317") (name "unconnected-(SV15-Pad6)") (class "Default")
      (node (ref "SV15") (pin "6") (pinfunction "6_6") (pintype "passive"))
    )
    (net (code "318") (name "unconnected-(SV15-Pad13)") (class "Default")
      (node (ref "SV15") (pin "13") (pinfunction "13_13") (pintype "passive"))
    )
    (net (code "319") (name "unconnected-(SV15-Pad14)") (class "Default")
      (node (ref "SV15") (pin "14") (pinfunction "14_14") (pintype "passive"))
    )
    (net (code "320") (name "unconnected-(SV18-Pad5)") (class "Default")
      (node (ref "SV18") (pin "5") (pinfunction "5_5") (pintype "passive"))
    )
    (net (code "321") (name "unconnected-(SV18-Pad6)") (class "Default")
      (node (ref "SV18") (pin "6") (pinfunction "6_6") (pintype "passive"))
    )
    (net (code "322") (name "unconnected-(SV18-Pad8)") (class "Default")
      (node (ref "SV18") (pin "8") (pinfunction "8_8") (pintype "passive"))
    )
    (net (code "323") (name "unconnected-(SV18-Pad10)") (class "Default")
      (node (ref "SV18") (pin "10") (pinfunction "10_10") (pintype "passive"))
    )
    (net (code "324") (name "unconnected-(SV19-Pad3)") (class "Default")
      (node (ref "SV19") (pin "3") (pinfunction "3_3") (pintype "passive"))
    )
    (net (code "325") (name "unconnected-(SV19-Pad5)") (class "Default")
      (node (ref "SV19") (pin "5") (pinfunction "5_5") (pintype "passive"))
    )
    (net (code "326") (name "unconnected-(SV20-Pad5)") (class "Default")
      (node (ref "SV20") (pin "5") (pinfunction "5_5") (pintype "passive"))
    )
    (net (code "327") (name "unconnected-(SV21-Pad3)") (class "Default")
      (node (ref "SV21") (pin "3") (pinfunction "3_3") (pintype "passive"))
    )
    (net (code "328") (name "unconnected-(SV21-Pad4)") (class "Default")
      (node (ref "SV21") (pin "4") (pinfunction "4_4") (pintype "passive"))
    )
    (net (code "329") (name "unconnected-(SV22-Pad13)") (class "Default")
      (node (ref "SV22") (pin "13") (pinfunction "13_13") (pintype "passive"))
    )
    (net (code "330") (name "unconnected-(SV23-Pad3)") (class "Default")
      (node (ref "SV23") (pin "3") (pinfunction "3_3") (pintype "passive"))
    )
    (net (code "331") (name "unconnected-(SV23-Pad4)") (class "Default")
      (node (ref "SV23") (pin "4") (pinfunction "4_4") (pintype "passive"))
    )
    (net (code "332") (name "unconnected-(SV24-Pad3)") (class "Default")
      (node (ref "SV24") (pin "3") (pinfunction "3_3") (pintype "passive"))
    )
    (net (code "333") (name "unconnected-(SV24-Pad4)") (class "Default")
      (node (ref "SV24") (pin "4") (pinfunction "4_4") (pintype "passive"))
    )
    (net (code "334") (name "unconnected-(SV26-Pad6)") (class "Default")
      (node (ref "SV26") (pin "6") (pinfunction "6_6") (pintype "passive"))
    )
    (net (code "335") (name "unconnected-(SV26-Pad8)") (class "Default")
      (node (ref "SV26") (pin "8") (pinfunction "8_8") (pintype "passive"))
    )
    (net (code "336") (name "unconnected-(SV26-Pad10)") (class "Default")
      (node (ref "SV26") (pin "10") (pinfunction "10_10") (pintype "passive"))
    )
    (net (code "337") (name "unconnected-(SV28-Pad1)") (class "Default")
      (node (ref "SV28") (pin "1") (pinfunction "1_1") (pintype "passive"))
    )
    (net (code "338") (name "unconnected-(SV28-Pad3)") (class "Default")
      (node (ref "SV28") (pin "3") (pinfunction "3_3") (pintype "passive"))
    )
    (net (code "339") (name "unconnected-(SV28-Pad4)") (class "Default")
      (node (ref "SV28") (pin "4") (pinfunction "4_4") (pintype "passive"))
    )
    (net (code "340") (name "unconnected-(SV28-Pad5)") (class "Default")
      (node (ref "SV28") (pin "5") (pinfunction "5_5") (pintype "passive"))
    )
    (net (code "341") (name "unconnected-(SV28-Pad7)") (class "Default")
      (node (ref "SV28") (pin "7") (pinfunction "7_7") (pintype "passive"))
    )
    (net (code "342") (name "unconnected-(SV28-Pad9)") (class "Default")
      (node (ref "SV28") (pin "9") (pinfunction "9_9") (pintype "passive"))
    )
    (net (code "343") (name "unconnected-(SV30-Pad4)") (class "Default")
      (node (ref "SV30") (pin "4") (pinfunction "4_4") (pintype "passive"))
    )
    (net (code "344") (name "unconnected-(U3-DNU-Pad3)") (class "Default")
      (node (ref "U3") (pin "3") (pinfunction "DNU_3") (pintype "bidirectional"))
    )
    (net (code "345") (name "unconnected-(U6-DCD#-Pad10)") (class "Default")
      (node (ref "U6") (pin "10") (pinfunction "DCD#_10") (pintype "input"))
    )
    (net (code "346") (name "unconnected-(U6-OSCI-Pad27)") (class "Default")
      (node (ref "U6") (pin "27") (pinfunction "OSCI_27") (pintype "input"))
    )
    (net (code "347") (name "unconnected-(U6-OSCO-Pad28)") (class "Default")
      (node (ref "U6") (pin "28") (pinfunction "OSCO_28") (pintype "output"))
    )
    (net (code "348") (name "unconnected-(U6-RESET#-Pad19)") (class "Default")
      (node (ref "U6") (pin "19") (pinfunction "RESET#_19") (pintype "input"))
    )
    (net (code "349") (name "unconnected-(U6-RI#-Pad6)") (class "Default")
      (node (ref "U6") (pin "6") (pinfunction "RI#_6") (pintype "input"))
    )
    (net (code "350") (name "unconnected-(U7-CNT_EN-Pad13)") (class "Default")
      (node (ref "U7") (pin "13") (pinfunction "CNT_EN_13") (pintype "bidirectional"))
    )
    (net (code "351") (name "unconnected-(U7-DFLAG{slash}-Pad9)") (class "Default")
      (node (ref "U7") (pin "9") (pinfunction "DFLAG/_9") (pintype "bidirectional"))
    )
    (net (code "352") (name "unconnected-(U7-FCKO-Pad1)") (class "Default")
      (node (ref "U7") (pin "1") (pinfunction "FCKO_1") (pintype "bidirectional"))
    )
    (net (code "353") (name "unconnected-(U7-INDEX{slash}-Pad10)") (class "Default")
      (node (ref "U7") (pin "10") (pinfunction "INDEX/_10") (pintype "bidirectional"))
    )
    (net (code "354") (name "unconnected-(U7-LFLAG{slash}-Pad8)") (class "Default")
      (node (ref "U7") (pin "8") (pinfunction "LFLAG/_8") (pintype "bidirectional"))
    )
    (net (code "355") (name "unconnected-(U8-CNT_EN-Pad13)") (class "Default")
      (node (ref "U8") (pin "13") (pinfunction "CNT_EN_13") (pintype "bidirectional"))
    )
    (net (code "356") (name "unconnected-(U8-DFLAG{slash}-Pad9)") (class "Default")
      (node (ref "U8") (pin "9") (pinfunction "DFLAG/_9") (pintype "bidirectional"))
    )
    (net (code "357") (name "unconnected-(U8-FCKO-Pad1)") (class "Default")
      (node (ref "U8") (pin "1") (pinfunction "FCKO_1") (pintype "bidirectional"))
    )
    (net (code "358") (name "unconnected-(U8-INDEX{slash}-Pad10)") (class "Default")
      (node (ref "U8") (pin "10") (pinfunction "INDEX/_10") (pintype "bidirectional"))
    )
    (net (code "359") (name "unconnected-(U8-LFLAG{slash}-Pad8)") (class "Default")
      (node (ref "U8") (pin "8") (pinfunction "LFLAG/_8") (pintype "bidirectional"))
    )
    (net (code "360") (name "unconnected-(U9-CNT_EN-Pad13)") (class "Default")
      (node (ref "U9") (pin "13") (pinfunction "CNT_EN_13") (pintype "bidirectional"))
    )
    (net (code "361") (name "unconnected-(U9-DFLAG{slash}-Pad9)") (class "Default")
      (node (ref "U9") (pin "9") (pinfunction "DFLAG/_9") (pintype "bidirectional"))
    )
    (net (code "362") (name "unconnected-(U9-FCKO-Pad1)") (class "Default")
      (node (ref "U9") (pin "1") (pinfunction "FCKO_1") (pintype "bidirectional"))
    )
    (net (code "363") (name "unconnected-(U9-INDEX{slash}-Pad10)") (class "Default")
      (node (ref "U9") (pin "10") (pinfunction "INDEX/_10") (pintype "bidirectional"))
    )
    (net (code "364") (name "unconnected-(U9-LFLAG{slash}-Pad8)") (class "Default")
      (node (ref "U9") (pin "8") (pinfunction "LFLAG/_8") (pintype "bidirectional"))
    )
    (net (code "365") (name "unconnected-(U10-CNT_EN-Pad13)") (class "Default")
      (node (ref "U10") (pin "13") (pinfunction "CNT_EN_13") (pintype "bidirectional"))
    )
    (net (code "366") (name "unconnected-(U10-DFLAG{slash}-Pad9)") (class "Default")
      (node (ref "U10") (pin "9") (pinfunction "DFLAG/_9") (pintype "bidirectional"))
    )
    (net (code "367") (name "unconnected-(U10-FCKO-Pad1)") (class "Default")
      (node (ref "U10") (pin "1") (pinfunction "FCKO_1") (pintype "bidirectional"))
    )
    (net (code "368") (name "unconnected-(U10-INDEX{slash}-Pad10)") (class "Default")
      (node (ref "U10") (pin "10") (pinfunction "INDEX/_10") (pintype "bidirectional"))
    )
    (net (code "369") (name "unconnected-(U10-LFLAG{slash}-Pad8)") (class "Default")
      (node (ref "U10") (pin "8") (pinfunction "LFLAG/_8") (pintype "bidirectional"))
    )
    (net (code "370") (name "unconnected-(U11-TEST-Pad38)") (class "Default")
      (node (ref "U11") (pin "38") (pinfunction "TEST_38") (pintype "bidirectional"))
    )
    (net (code "371") (name "unconnected-(U15-P1_VIN-PadP$1)") (class "Default")
      (node (ref "U15") (pin "P$1") (pinfunction "P1_VIN_P$1") (pintype "bidirectional"))
    )
    (net (code "372") (name "unconnected-(U15-P6_VREF-PadP$6)") (class "Default")
      (node (ref "U15") (pin "P$6") (pinfunction "P6_VREF_P$6") (pintype "bidirectional"))
    )
    (net (code "373") (name "unconnected-(U15-P9_PWR_DOWN-PadP$9)") (class "Default")
      (node (ref "U15") (pin "P$9") (pinfunction "P9_PWR_DOWN_P$9") (pintype "bidirectional"))
    )
    (net (code "374") (name "unconnected-(U15-P10_SELFTEST-PadP$10)") (class "Default")
      (node (ref "U15") (pin "P$10") (pinfunction "P10_SELFTEST_P$10") (pintype "bidirectional"))
    )
    (net (code "375") (name "unconnected-(U15-P12_HIGHPASS_RST-PadP$12)") (class "Default")
      (node (ref "U15") (pin "P$12") (pinfunction "P12_HIGHPASS_RST_P$12") (pintype "bidirectional"))
    )
    (net (code "376") (name "unconnected-(X1-Pad1)") (class "Default")
      (node (ref "X1") (pin "1") (pinfunction "1_1") (pintype "passive"))
    )
    (net (code "377") (name "unconnected-(X1-Pad4)") (class "Default")
      (node (ref "X1") (pin "4") (pinfunction "4_4") (pintype "passive"))
    )
    (net (code "378") (name "unconnected-(X1-Pad6)") (class "Default")
      (node (ref "X1") (pin "6") (pinfunction "6_6") (pintype "passive"))
    )
    (net (code "379") (name "unconnected-(X1-Pad7)") (class "Default")
      (node (ref "X1") (pin "7") (pinfunction "7_7") (pintype "passive"))
    )
    (net (code "380") (name "unconnected-(X1-Pad8)") (class "Default")
      (node (ref "X1") (pin "8") (pinfunction "8_8") (pintype "passive"))
    )
    (net (code "381") (name "unconnected-(X1-Pad9)") (class "Default")
      (node (ref "X1") (pin "9") (pinfunction "9_9") (pintype "passive"))
    )
  )
)
